# seven_seg.net
KiCad netlist of a schematic drawn in EAGLE
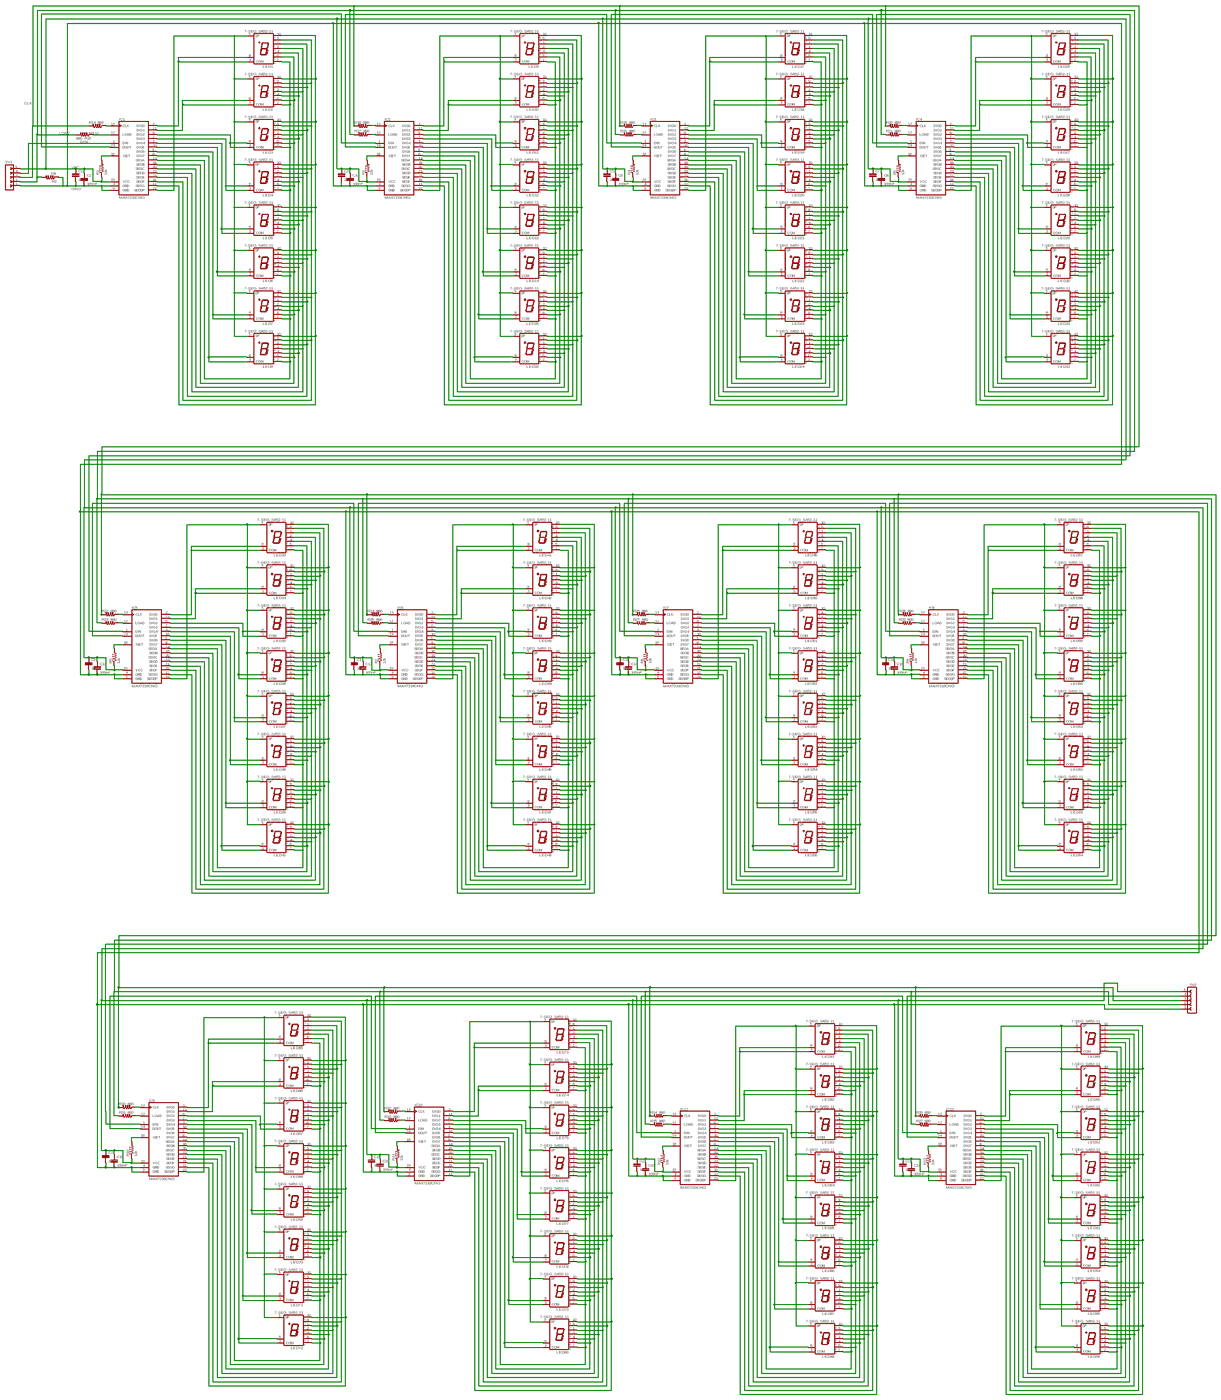
[diagram p0: schematic, sheet 1, overview]
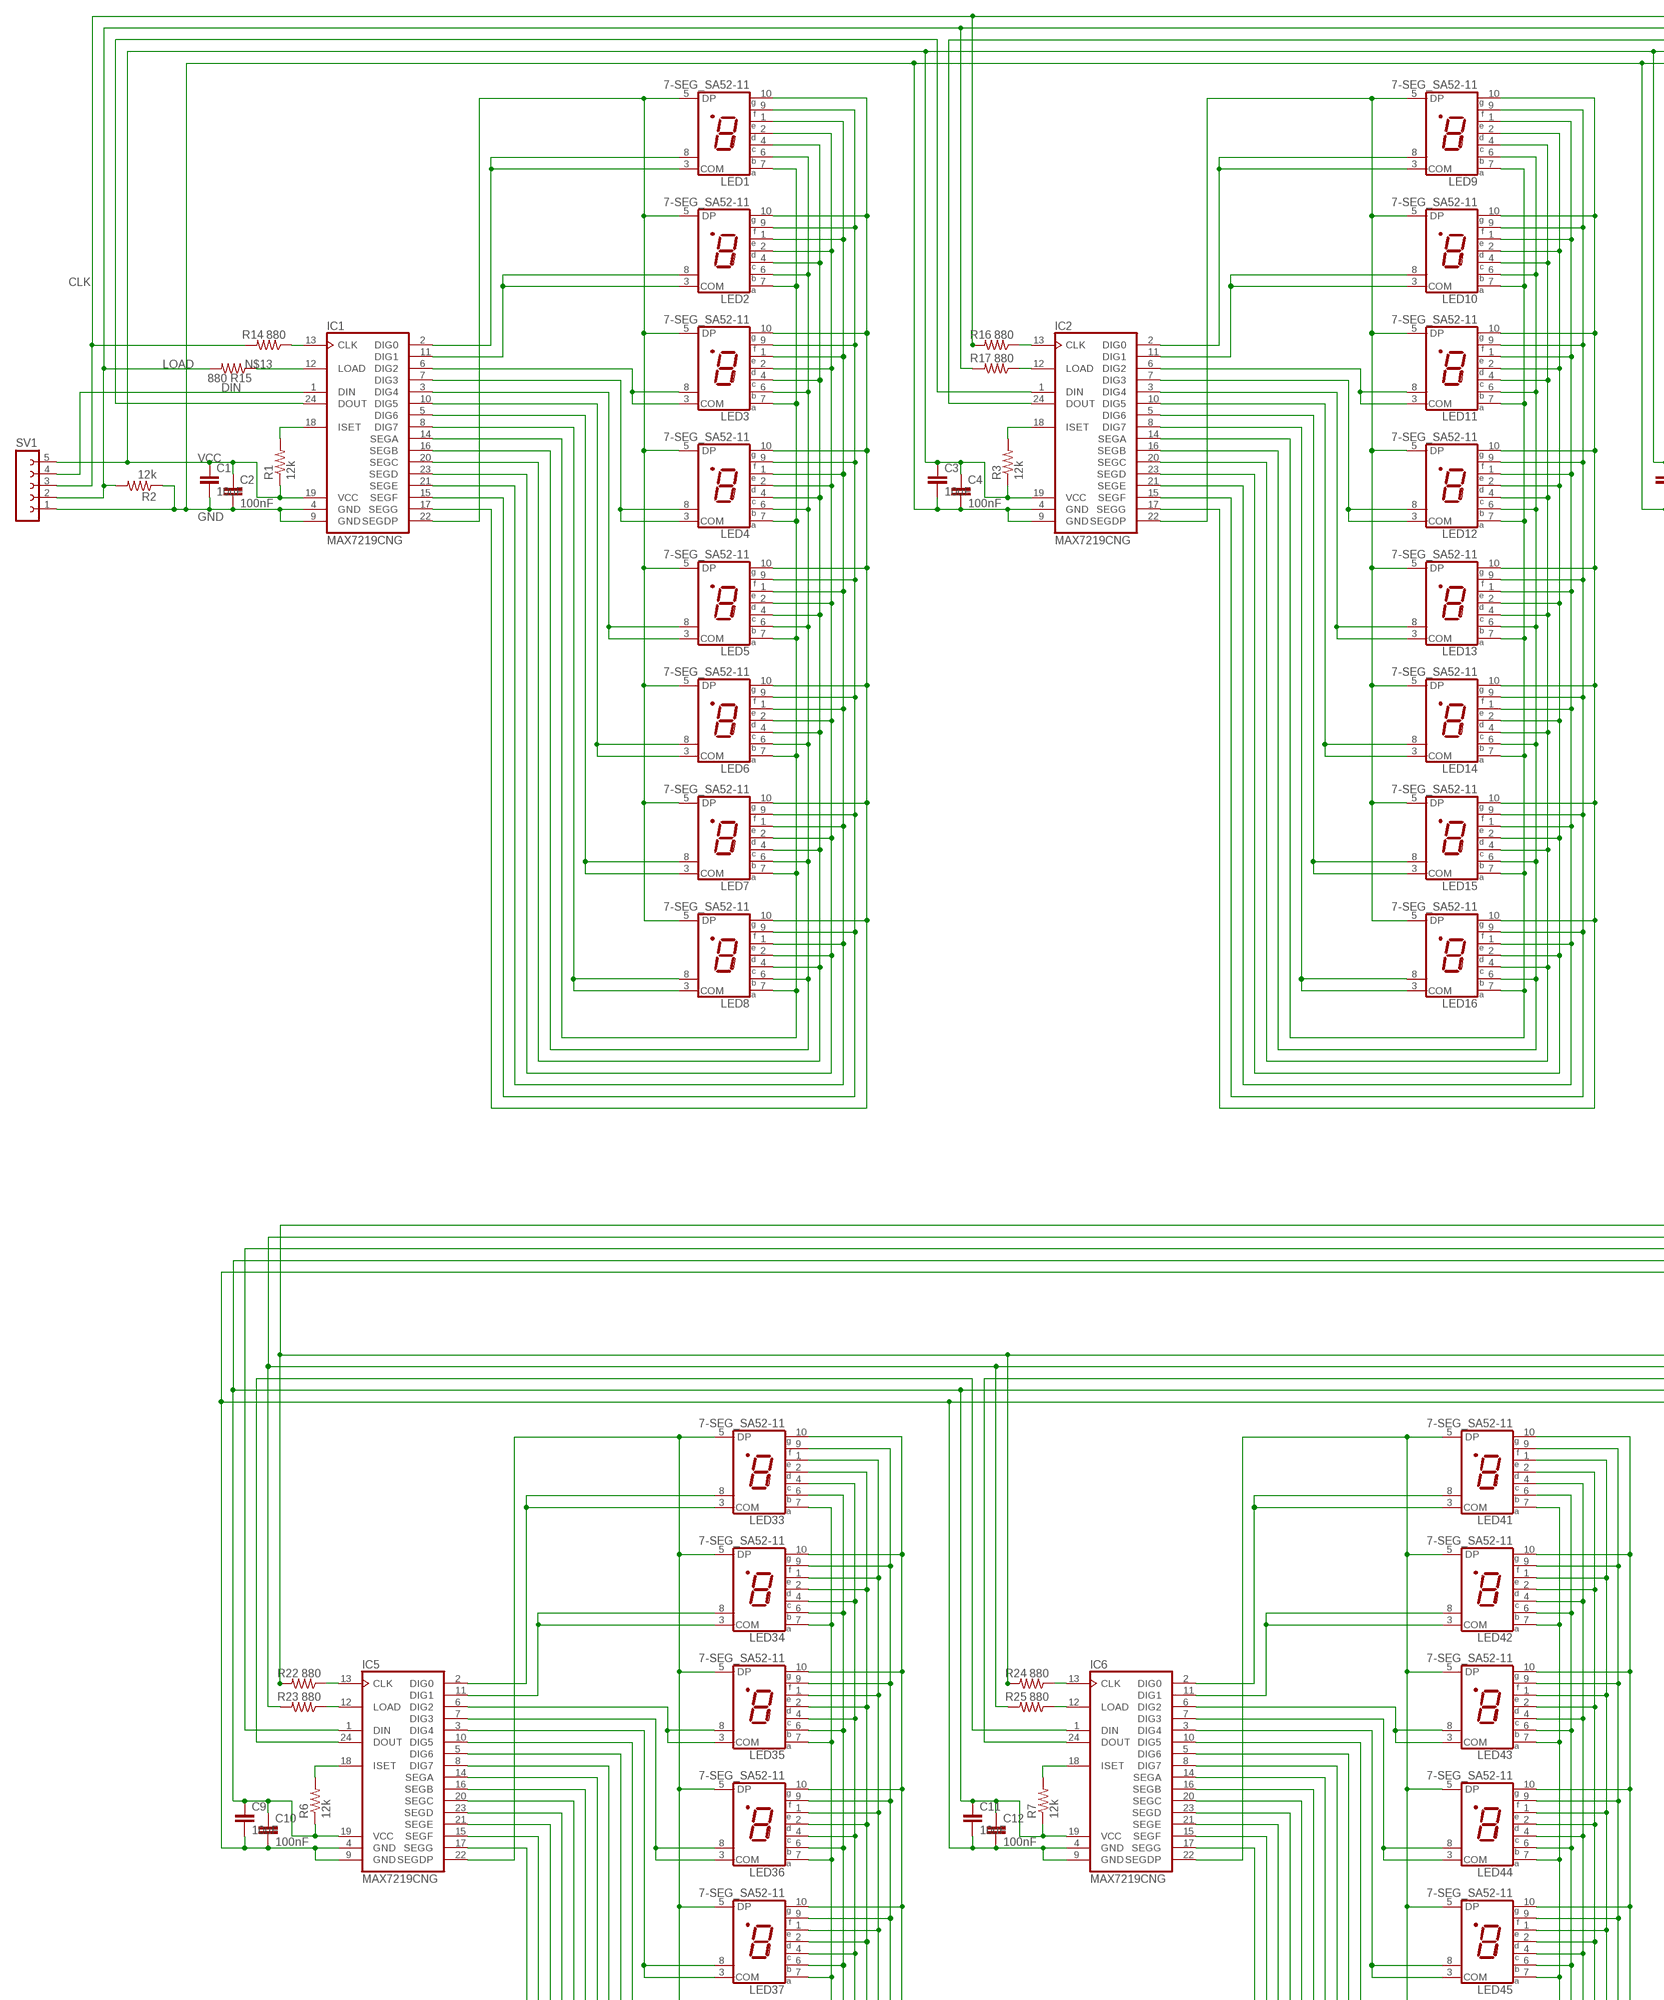
[diagram p1: schematic, sheet 1, part 1 of 4]
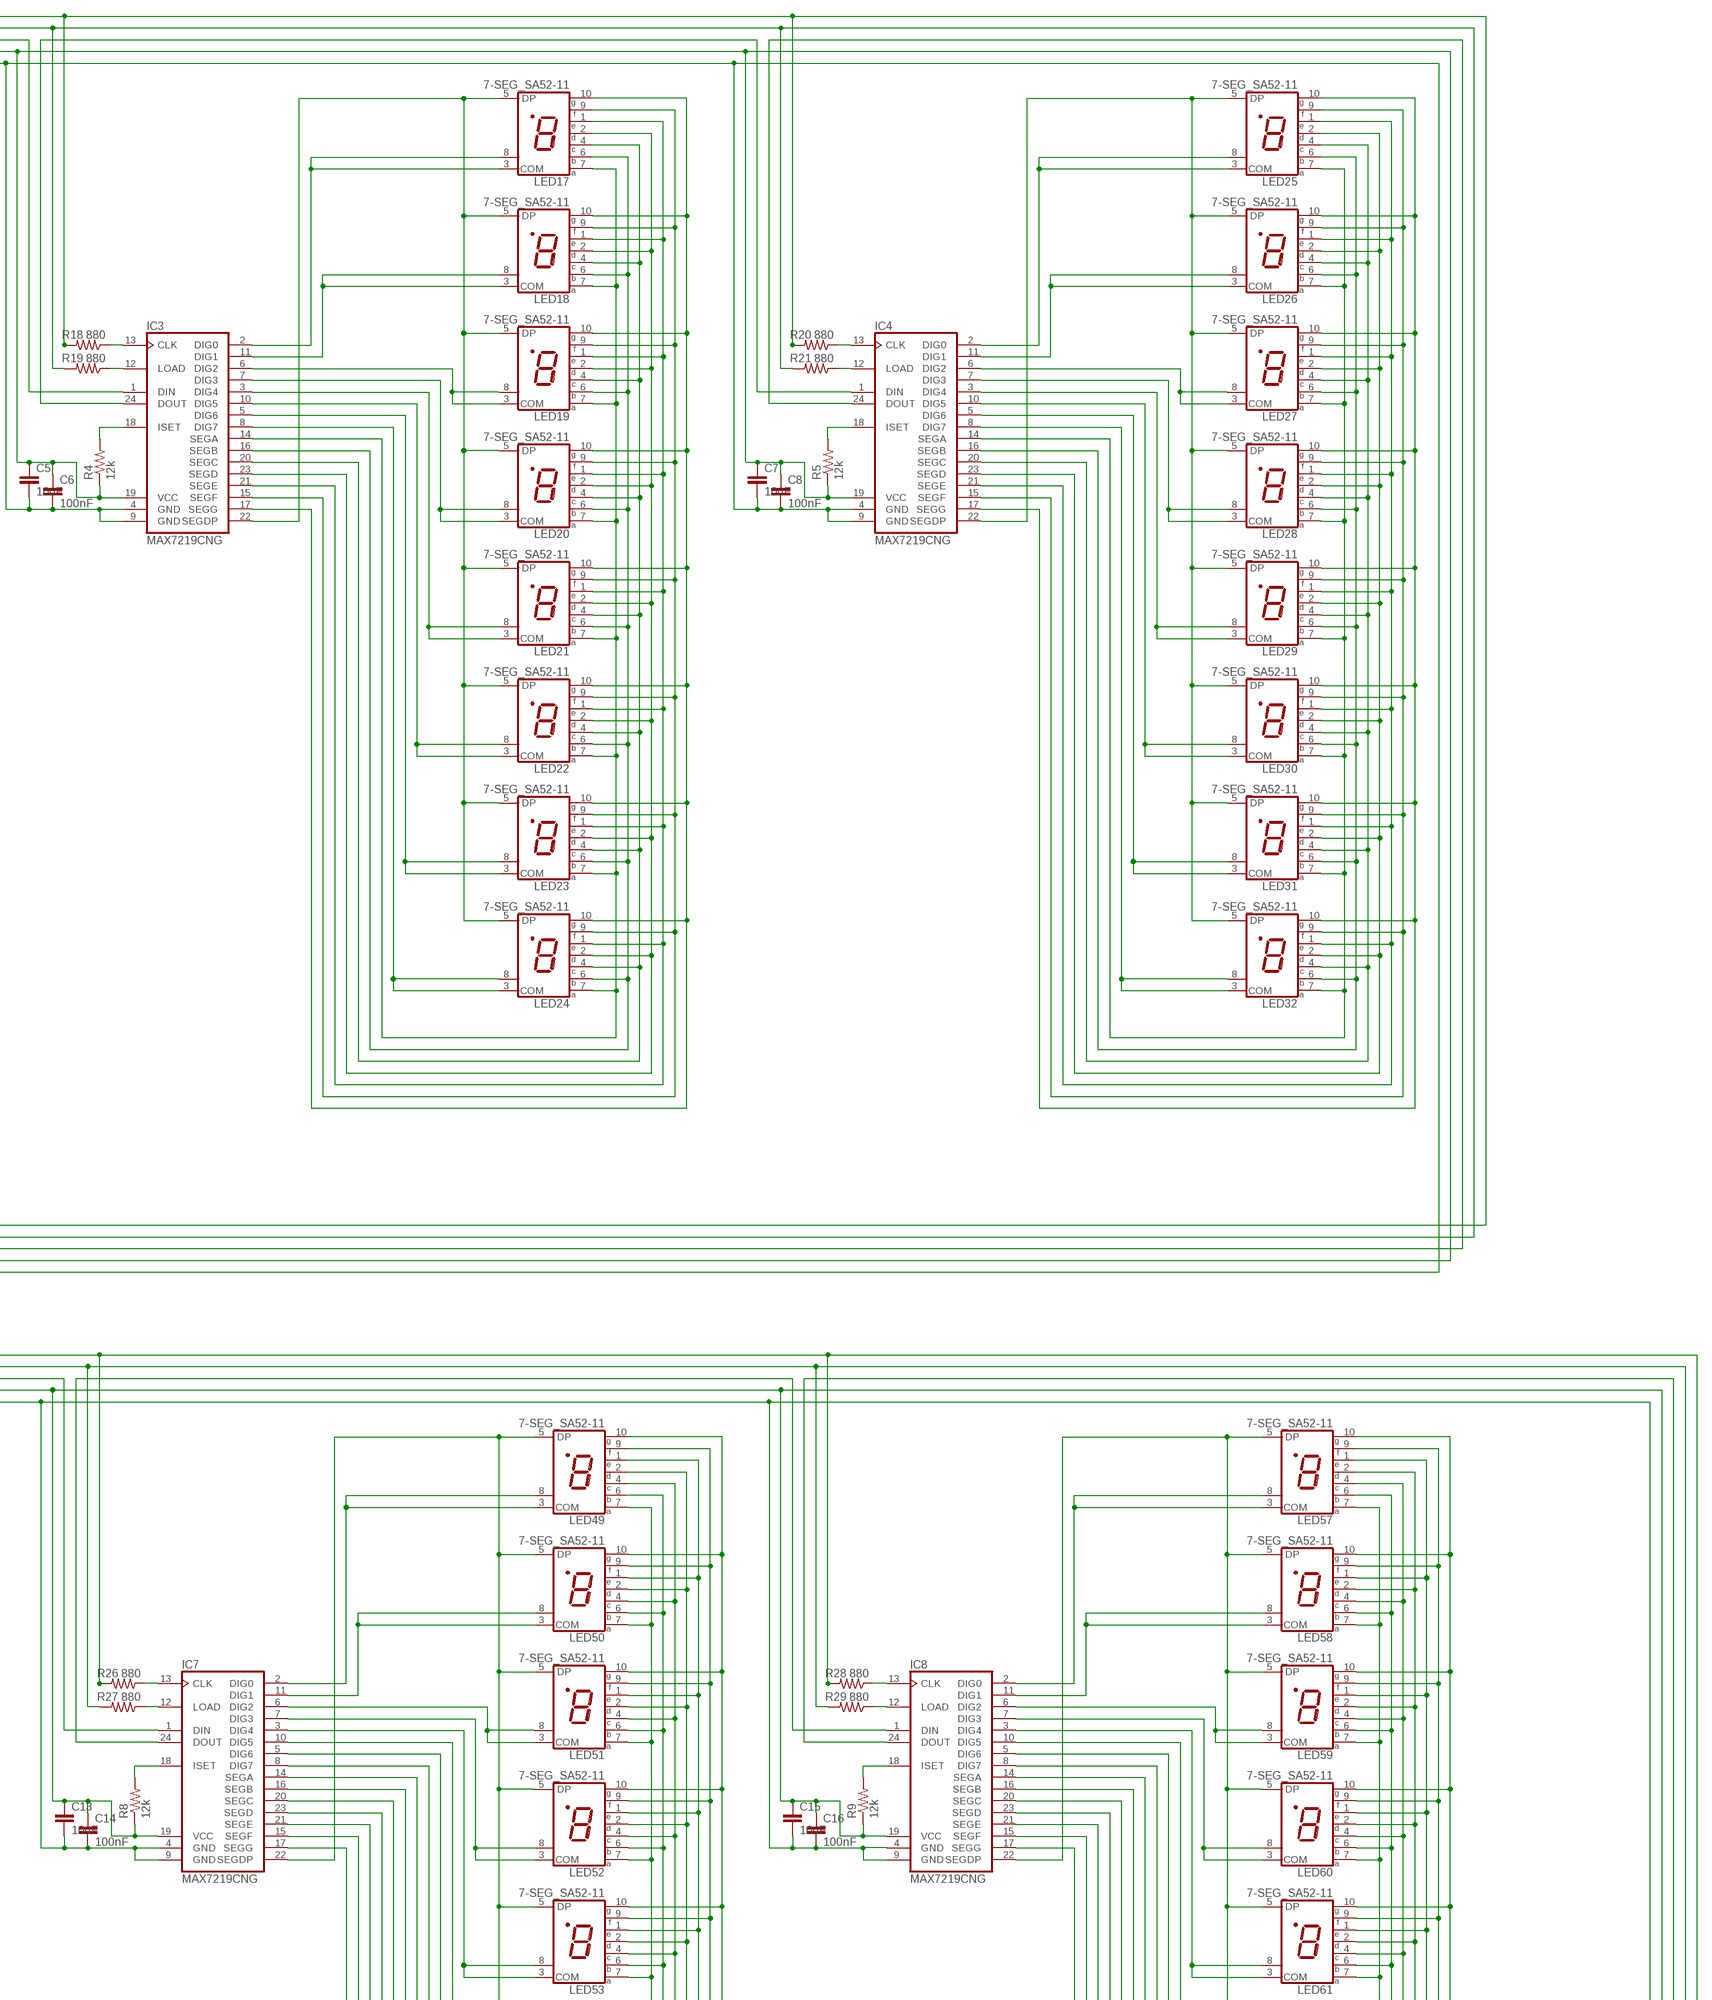
[diagram p2: schematic, sheet 1, part 2 of 4]
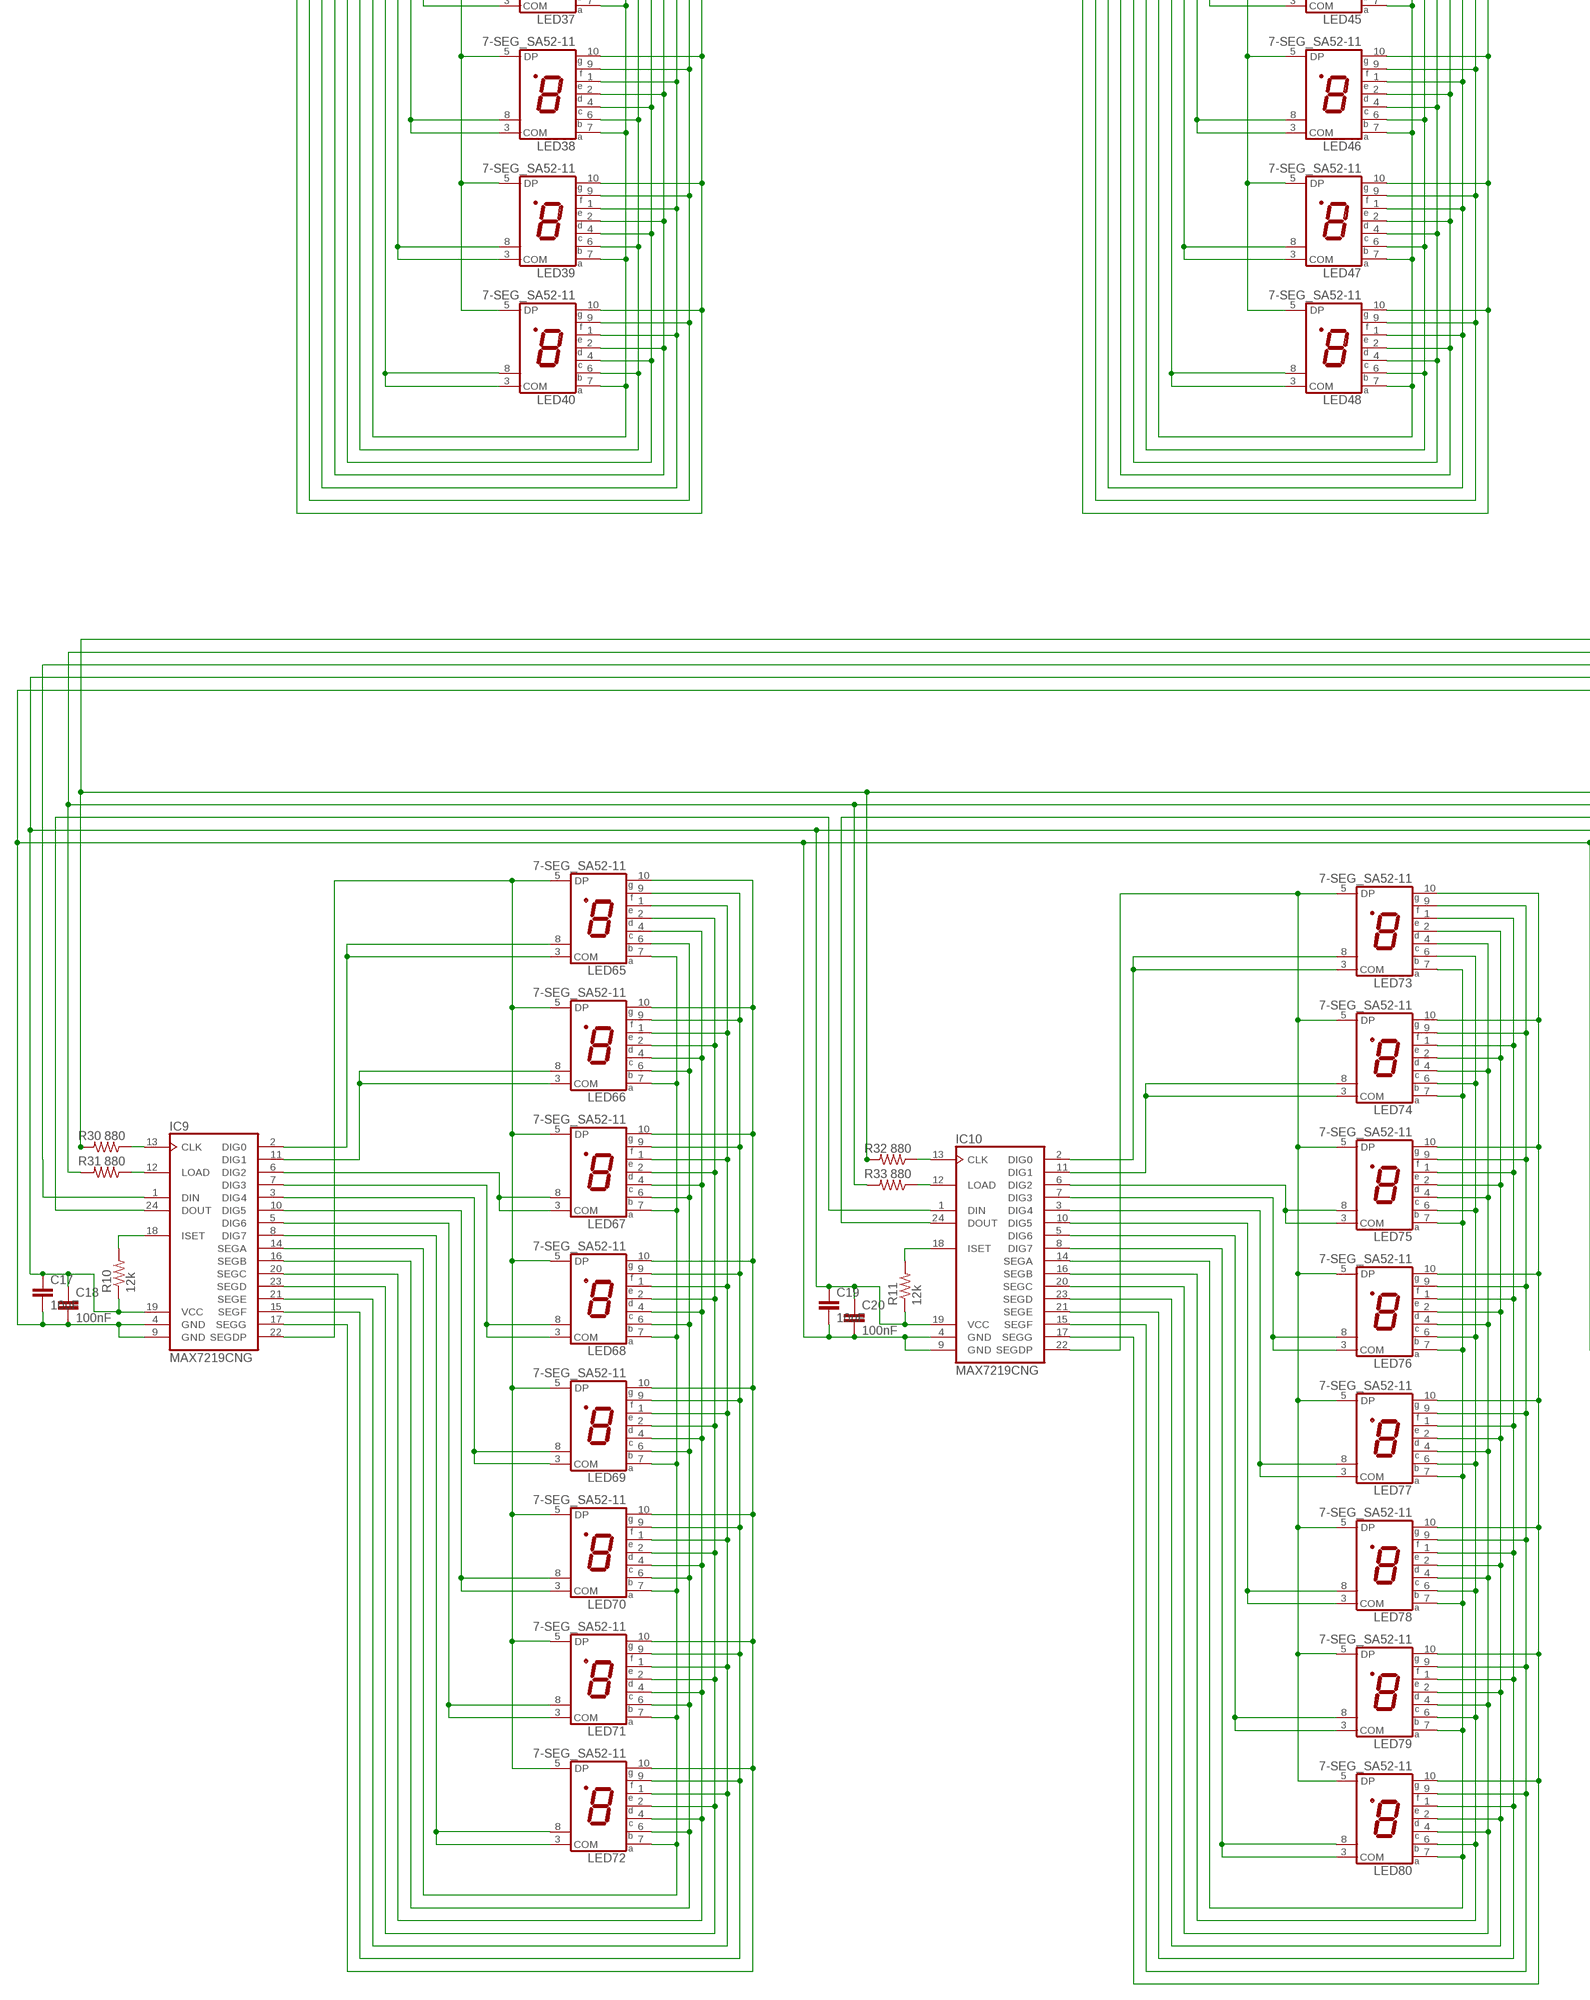
[diagram p3: schematic, sheet 1, part 3 of 4]
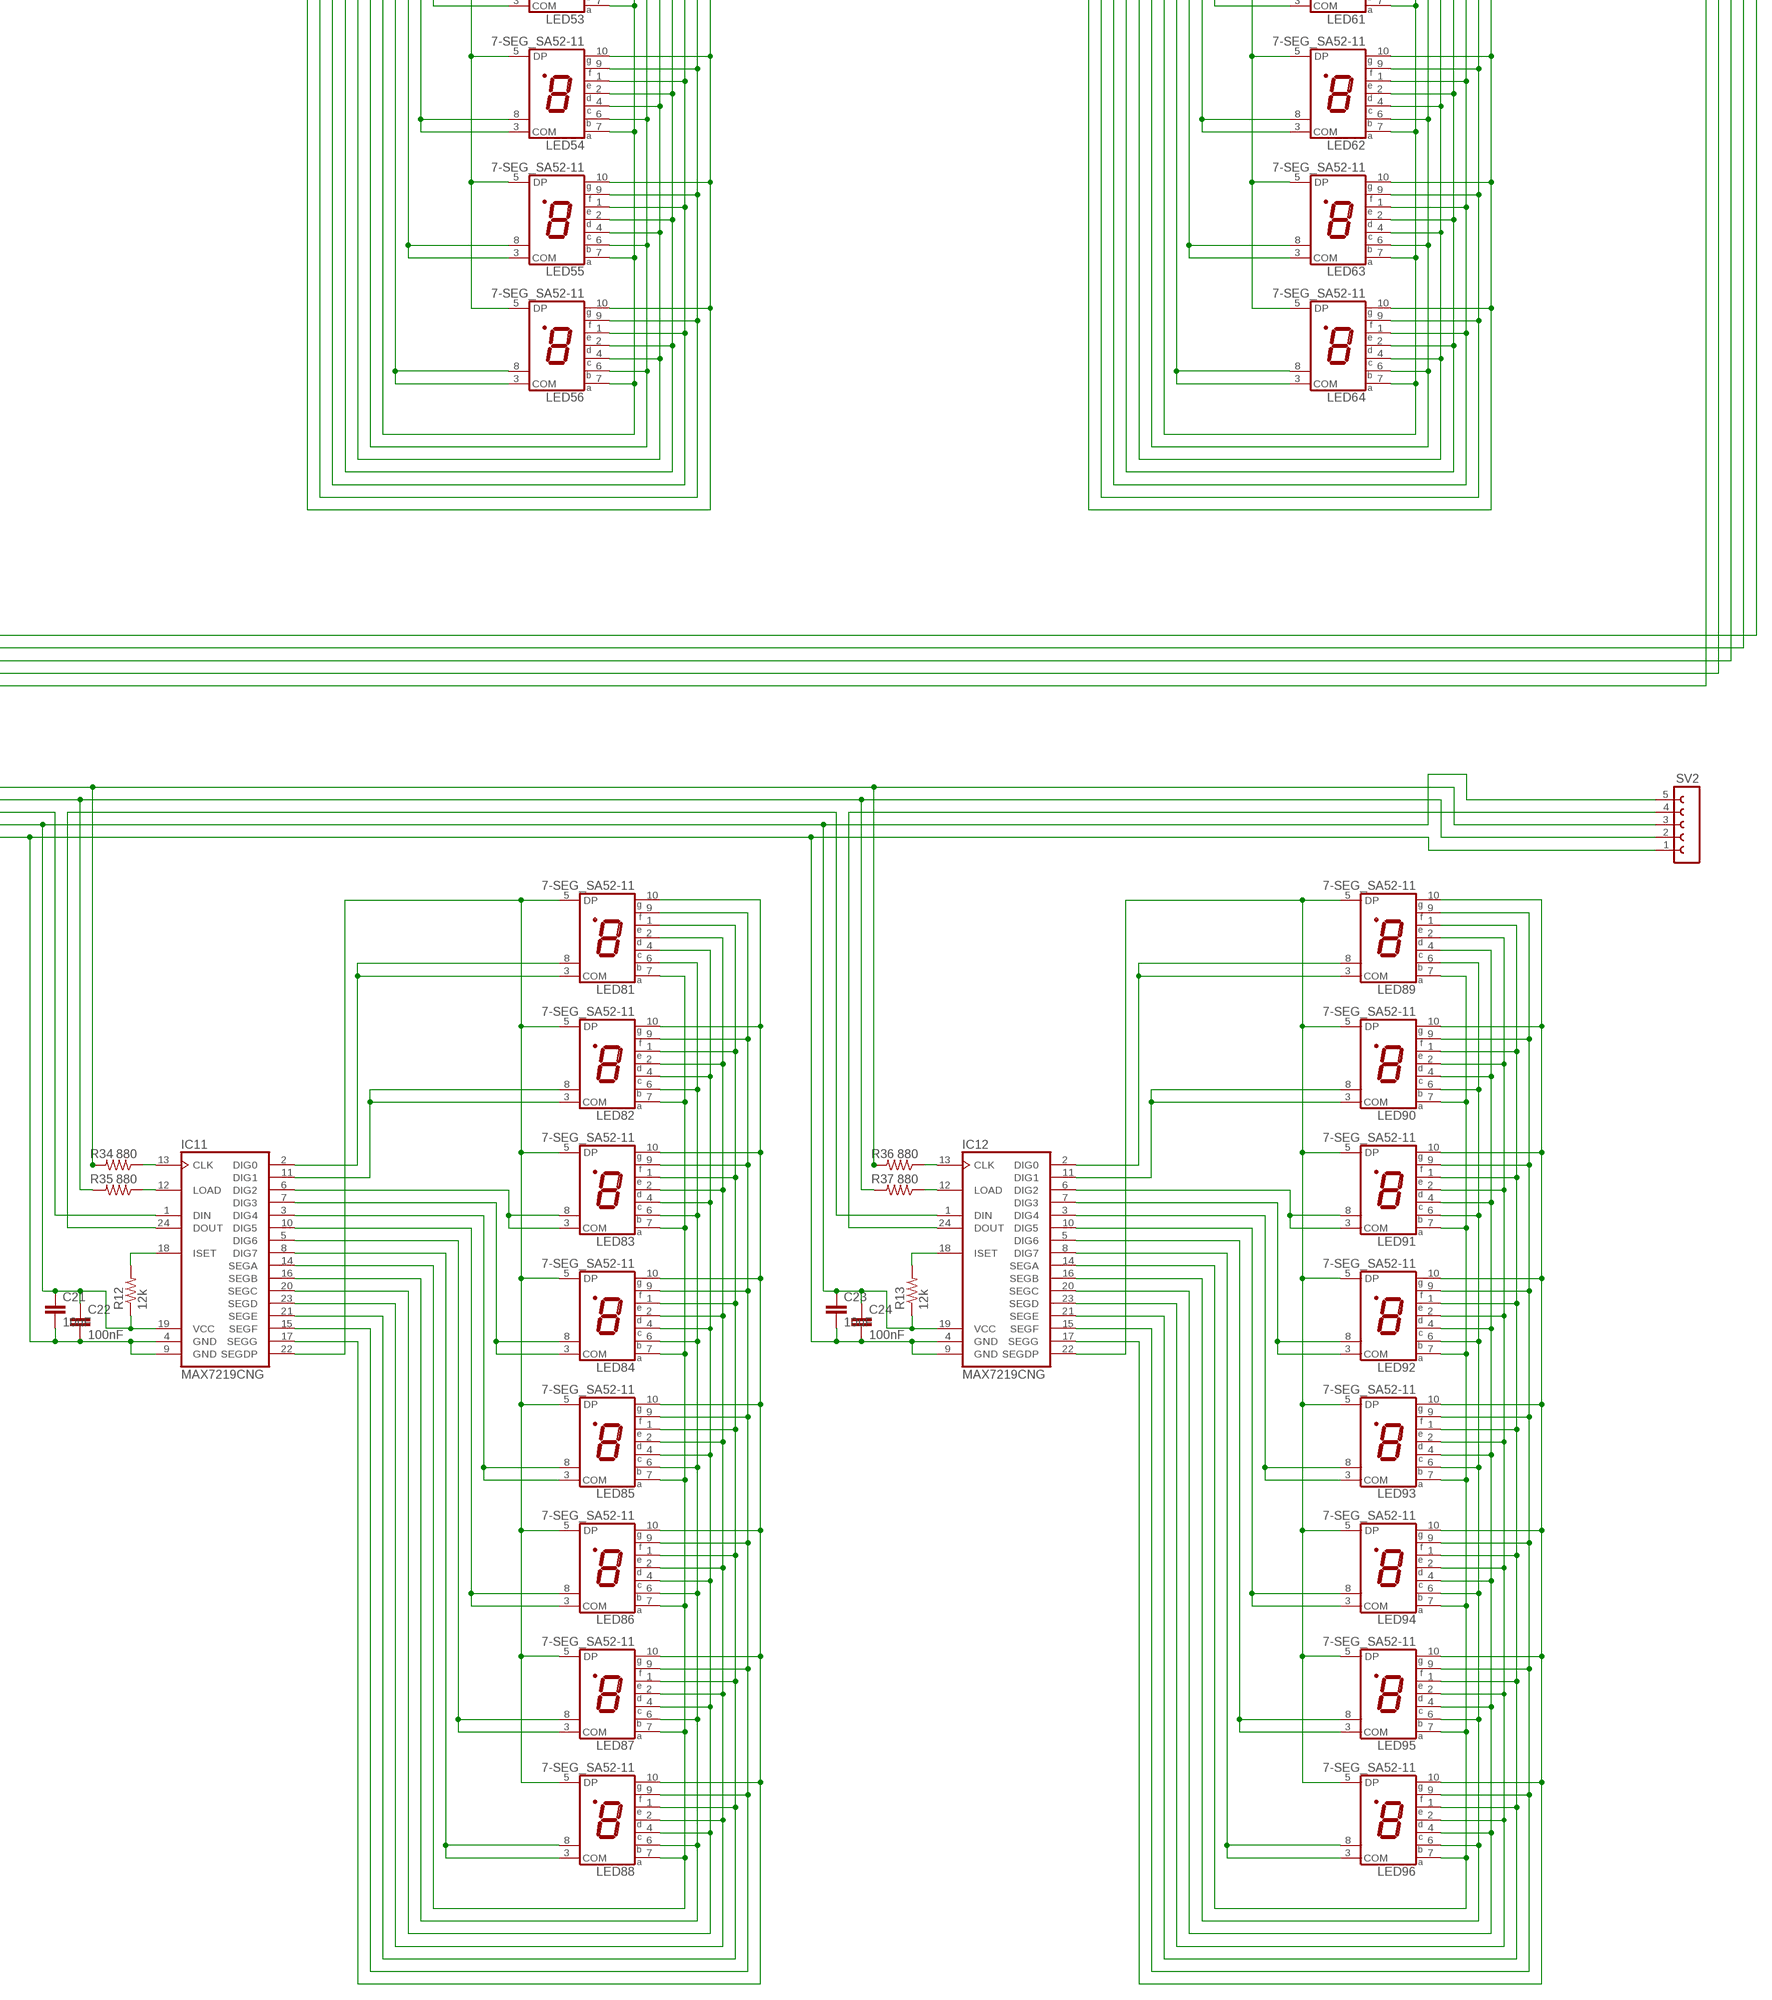
[diagram p4: schematic, sheet 1, part 4 of 4]

(export (version "E")
  (design (tool "Eeschema 10.0.6"))
  (components
    (comp (ref "C1")
      (value "10uF")
      (footprint "eagle-import:C2.5-2")
      (libsource (lib "eagle-import") (part "C2.5/2"))
    )
    (comp (ref "C2")
      (value "100nF")
      (footprint "eagle-import:C2.5-2")
      (libsource (lib "eagle-import") (part "C2.5/2"))
    )
    (comp (ref "C3")
      (value "10uF")
      (footprint "eagle-import:C2.5-2")
      (libsource (lib "eagle-import") (part "C2.5/2"))
    )
    (comp (ref "C4")
      (value "100nF")
      (footprint "eagle-import:C2.5-2")
      (libsource (lib "eagle-import") (part "C2.5/2"))
    )
    (comp (ref "C5")
      (value "10uF")
      (footprint "eagle-import:C2.5-2")
      (libsource (lib "eagle-import") (part "C2.5/2"))
    )
    (comp (ref "C6")
      (value "100nF")
      (footprint "eagle-import:C2.5-2")
      (libsource (lib "eagle-import") (part "C2.5/2"))
    )
    (comp (ref "C7")
      (value "10uF")
      (footprint "eagle-import:C2.5-2")
      (libsource (lib "eagle-import") (part "C2.5/2"))
    )
    (comp (ref "C8")
      (value "100nF")
      (footprint "eagle-import:C2.5-2")
      (libsource (lib "eagle-import") (part "C2.5/2"))
    )
    (comp (ref "C9")
      (value "10uF")
      (footprint "eagle-import:C2.5-2")
      (libsource (lib "eagle-import") (part "C2.5/2"))
    )
    (comp (ref "C10")
      (value "100nF")
      (footprint "eagle-import:C2.5-2")
      (libsource (lib "eagle-import") (part "C2.5/2"))
    )
    (comp (ref "C11")
      (value "10uF")
      (footprint "eagle-import:C2.5-2")
      (libsource (lib "eagle-import") (part "C2.5/2"))
    )
    (comp (ref "C12")
      (value "100nF")
      (footprint "eagle-import:C2.5-2")
      (libsource (lib "eagle-import") (part "C2.5/2"))
    )
    (comp (ref "C13")
      (value "10uF")
      (footprint "eagle-import:C2.5-2")
      (libsource (lib "eagle-import") (part "C2.5/2"))
    )
    (comp (ref "C14")
      (value "100nF")
      (footprint "eagle-import:C2.5-2")
      (libsource (lib "eagle-import") (part "C2.5/2"))
    )
    (comp (ref "C15")
      (value "10uF")
      (footprint "eagle-import:C2.5-2")
      (libsource (lib "eagle-import") (part "C2.5/2"))
    )
    (comp (ref "C16")
      (value "100nF")
      (footprint "eagle-import:C2.5-2")
      (libsource (lib "eagle-import") (part "C2.5/2"))
    )
    (comp (ref "C17")
      (value "10uF")
      (footprint "eagle-import:C2.5-2")
      (libsource (lib "eagle-import") (part "C2.5/2"))
    )
    (comp (ref "C18")
      (value "100nF")
      (footprint "eagle-import:C2.5-2")
      (libsource (lib "eagle-import") (part "C2.5/2"))
    )
    (comp (ref "C19")
      (value "10uF")
      (footprint "eagle-import:C2.5-2")
      (libsource (lib "eagle-import") (part "C2.5/2"))
    )
    (comp (ref "C20")
      (value "100nF")
      (footprint "eagle-import:C2.5-2")
      (libsource (lib "eagle-import") (part "C2.5/2"))
    )
    (comp (ref "C21")
      (value "10uF")
      (footprint "eagle-import:C2.5-2")
      (libsource (lib "eagle-import") (part "C2.5/2"))
    )
    (comp (ref "C22")
      (value "100nF")
      (footprint "eagle-import:C2.5-2")
      (libsource (lib "eagle-import") (part "C2.5/2"))
    )
    (comp (ref "C23")
      (value "10uF")
      (footprint "eagle-import:C2.5-2")
      (libsource (lib "eagle-import") (part "C2.5/2"))
    )
    (comp (ref "C24")
      (value "100nF")
      (footprint "eagle-import:C2.5-2")
      (libsource (lib "eagle-import") (part "C2.5/2"))
    )
    (comp (ref "IC1")
      (value "MAX7219CNG")
      (footprint "eagle-import:DIL24-3")
      (fields (field (name "MF") "MAXIM"))
      (libsource (lib "eagle-import") (part "MAX7219CNG"))
    )
    (comp (ref "IC2")
      (value "MAX7219CNG")
      (footprint "eagle-import:DIL24-3")
      (fields (field (name "MF") "MAXIM"))
      (libsource (lib "eagle-import") (part "MAX7219CNG"))
    )
    (comp (ref "IC3")
      (value "MAX7219CNG")
      (footprint "eagle-import:DIL24-3")
      (fields (field (name "MF") "MAXIM"))
      (libsource (lib "eagle-import") (part "MAX7219CNG"))
    )
    (comp (ref "IC4")
      (value "MAX7219CNG")
      (footprint "eagle-import:DIL24-3")
      (fields (field (name "MF") "MAXIM"))
      (libsource (lib "eagle-import") (part "MAX7219CNG"))
    )
    (comp (ref "IC5")
      (value "MAX7219CNG")
      (footprint "eagle-import:DIL24-3")
      (fields (field (name "MF") "MAXIM"))
      (libsource (lib "eagle-import") (part "MAX7219CNG"))
    )
    (comp (ref "IC6")
      (value "MAX7219CNG")
      (footprint "eagle-import:DIL24-3")
      (fields (field (name "MF") "MAXIM"))
      (libsource (lib "eagle-import") (part "MAX7219CNG"))
    )
    (comp (ref "IC7")
      (value "MAX7219CNG")
      (footprint "eagle-import:DIL24-3")
      (fields (field (name "MF") "MAXIM"))
      (libsource (lib "eagle-import") (part "MAX7219CNG"))
    )
    (comp (ref "IC8")
      (value "MAX7219CNG")
      (footprint "eagle-import:DIL24-3")
      (fields (field (name "MF") "MAXIM"))
      (libsource (lib "eagle-import") (part "MAX7219CNG"))
    )
    (comp (ref "IC9")
      (value "MAX7219CNG")
      (footprint "eagle-import:DIL24-3")
      (fields (field (name "MF") "MAXIM"))
      (libsource (lib "eagle-import") (part "MAX7219CNG"))
    )
    (comp (ref "IC10")
      (value "MAX7219CNG")
      (footprint "eagle-import:DIL24-3")
      (fields (field (name "MF") "MAXIM"))
      (libsource (lib "eagle-import") (part "MAX7219CNG"))
    )
    (comp (ref "IC11")
      (value "MAX7219CNG")
      (footprint "eagle-import:DIL24-3")
      (fields (field (name "MF") "MAXIM"))
      (libsource (lib "eagle-import") (part "MAX7219CNG"))
    )
    (comp (ref "IC12")
      (value "MAX7219CNG")
      (footprint "eagle-import:DIL24-3")
      (fields (field (name "MF") "MAXIM"))
      (libsource (lib "eagle-import") (part "MAX7219CNG"))
    )
    (comp (ref "LED1")
      (value "7-SEG_SA52-11")
      (footprint "eagle-import:SA52-11")
      (libsource (lib "eagle-import") (part "7-SEG_SA52-11"))
    )
    (comp (ref "LED2")
      (value "7-SEG_SA52-11")
      (footprint "eagle-import:SA52-11")
      (libsource (lib "eagle-import") (part "7-SEG_SA52-11"))
    )
    (comp (ref "LED3")
      (value "7-SEG_SA52-11")
      (footprint "eagle-import:SA52-11")
      (libsource (lib "eagle-import") (part "7-SEG_SA52-11"))
    )
    (comp (ref "LED4")
      (value "7-SEG_SA52-11")
      (footprint "eagle-import:SA52-11")
      (libsource (lib "eagle-import") (part "7-SEG_SA52-11"))
    )
    (comp (ref "LED5")
      (value "7-SEG_SA52-11")
      (footprint "eagle-import:SA52-11")
      (libsource (lib "eagle-import") (part "7-SEG_SA52-11"))
    )
    (comp (ref "LED6")
      (value "7-SEG_SA52-11")
      (footprint "eagle-import:SA52-11")
      (libsource (lib "eagle-import") (part "7-SEG_SA52-11"))
    )
    (comp (ref "LED7")
      (value "7-SEG_SA52-11")
      (footprint "eagle-import:SA52-11")
      (libsource (lib "eagle-import") (part "7-SEG_SA52-11"))
    )
    (comp (ref "LED8")
      (value "7-SEG_SA52-11")
      (footprint "eagle-import:SA52-11")
      (libsource (lib "eagle-import") (part "7-SEG_SA52-11"))
    )
    (comp (ref "LED9")
      (value "7-SEG_SA52-11")
      (footprint "eagle-import:SA52-11")
      (libsource (lib "eagle-import") (part "7-SEG_SA52-11"))
    )
    (comp (ref "LED10")
      (value "7-SEG_SA52-11")
      (footprint "eagle-import:SA52-11")
      (libsource (lib "eagle-import") (part "7-SEG_SA52-11"))
    )
    (comp (ref "LED11")
      (value "7-SEG_SA52-11")
      (footprint "eagle-import:SA52-11")
      (libsource (lib "eagle-import") (part "7-SEG_SA52-11"))
    )
    (comp (ref "LED12")
      (value "7-SEG_SA52-11")
      (footprint "eagle-import:SA52-11")
      (libsource (lib "eagle-import") (part "7-SEG_SA52-11"))
    )
    (comp (ref "LED13")
      (value "7-SEG_SA52-11")
      (footprint "eagle-import:SA52-11")
      (libsource (lib "eagle-import") (part "7-SEG_SA52-11"))
    )
    (comp (ref "LED14")
      (value "7-SEG_SA52-11")
      (footprint "eagle-import:SA52-11")
      (libsource (lib "eagle-import") (part "7-SEG_SA52-11"))
    )
    (comp (ref "LED15")
      (value "7-SEG_SA52-11")
      (footprint "eagle-import:SA52-11")
      (libsource (lib "eagle-import") (part "7-SEG_SA52-11"))
    )
    (comp (ref "LED16")
      (value "7-SEG_SA52-11")
      (footprint "eagle-import:SA52-11")
      (libsource (lib "eagle-import") (part "7-SEG_SA52-11"))
    )
    (comp (ref "LED17")
      (value "7-SEG_SA52-11")
      (footprint "eagle-import:SA52-11")
      (libsource (lib "eagle-import") (part "7-SEG_SA52-11"))
    )
    (comp (ref "LED18")
      (value "7-SEG_SA52-11")
      (footprint "eagle-import:SA52-11")
      (libsource (lib "eagle-import") (part "7-SEG_SA52-11"))
    )
    (comp (ref "LED19")
      (value "7-SEG_SA52-11")
      (footprint "eagle-import:SA52-11")
      (libsource (lib "eagle-import") (part "7-SEG_SA52-11"))
    )
    (comp (ref "LED20")
      (value "7-SEG_SA52-11")
      (footprint "eagle-import:SA52-11")
      (libsource (lib "eagle-import") (part "7-SEG_SA52-11"))
    )
    (comp (ref "LED21")
      (value "7-SEG_SA52-11")
      (footprint "eagle-import:SA52-11")
      (libsource (lib "eagle-import") (part "7-SEG_SA52-11"))
    )
    (comp (ref "LED22")
      (value "7-SEG_SA52-11")
      (footprint "eagle-import:SA52-11")
      (libsource (lib "eagle-import") (part "7-SEG_SA52-11"))
    )
    (comp (ref "LED23")
      (value "7-SEG_SA52-11")
      (footprint "eagle-import:SA52-11")
      (libsource (lib "eagle-import") (part "7-SEG_SA52-11"))
    )
    (comp (ref "LED24")
      (value "7-SEG_SA52-11")
      (footprint "eagle-import:SA52-11")
      (libsource (lib "eagle-import") (part "7-SEG_SA52-11"))
    )
    (comp (ref "LED25")
      (value "7-SEG_SA52-11")
      (footprint "eagle-import:SA52-11")
      (libsource (lib "eagle-import") (part "7-SEG_SA52-11"))
    )
    (comp (ref "LED26")
      (value "7-SEG_SA52-11")
      (footprint "eagle-import:SA52-11")
      (libsource (lib "eagle-import") (part "7-SEG_SA52-11"))
    )
    (comp (ref "LED27")
      (value "7-SEG_SA52-11")
      (footprint "eagle-import:SA52-11")
      (libsource (lib "eagle-import") (part "7-SEG_SA52-11"))
    )
    (comp (ref "LED28")
      (value "7-SEG_SA52-11")
      (footprint "eagle-import:SA52-11")
      (libsource (lib "eagle-import") (part "7-SEG_SA52-11"))
    )
    (comp (ref "LED29")
      (value "7-SEG_SA52-11")
      (footprint "eagle-import:SA52-11")
      (libsource (lib "eagle-import") (part "7-SEG_SA52-11"))
    )
    (comp (ref "LED30")
      (value "7-SEG_SA52-11")
      (footprint "eagle-import:SA52-11")
      (libsource (lib "eagle-import") (part "7-SEG_SA52-11"))
    )
    (comp (ref "LED31")
      (value "7-SEG_SA52-11")
      (footprint "eagle-import:SA52-11")
      (libsource (lib "eagle-import") (part "7-SEG_SA52-11"))
    )
    (comp (ref "LED32")
      (value "7-SEG_SA52-11")
      (footprint "eagle-import:SA52-11")
      (libsource (lib "eagle-import") (part "7-SEG_SA52-11"))
    )
    (comp (ref "LED33")
      (value "7-SEG_SA52-11")
      (footprint "eagle-import:SA52-11")
      (libsource (lib "eagle-import") (part "7-SEG_SA52-11"))
    )
    (comp (ref "LED34")
      (value "7-SEG_SA52-11")
      (footprint "eagle-import:SA52-11")
      (libsource (lib "eagle-import") (part "7-SEG_SA52-11"))
    )
    (comp (ref "LED35")
      (value "7-SEG_SA52-11")
      (footprint "eagle-import:SA52-11")
      (libsource (lib "eagle-import") (part "7-SEG_SA52-11"))
    )
    (comp (ref "LED36")
      (value "7-SEG_SA52-11")
      (footprint "eagle-import:SA52-11")
      (libsource (lib "eagle-import") (part "7-SEG_SA52-11"))
    )
    (comp (ref "LED37")
      (value "7-SEG_SA52-11")
      (footprint "eagle-import:SA52-11")
      (libsource (lib "eagle-import") (part "7-SEG_SA52-11"))
    )
    (comp (ref "LED38")
      (value "7-SEG_SA52-11")
      (footprint "eagle-import:SA52-11")
      (libsource (lib "eagle-import") (part "7-SEG_SA52-11"))
    )
    (comp (ref "LED39")
      (value "7-SEG_SA52-11")
      (footprint "eagle-import:SA52-11")
      (libsource (lib "eagle-import") (part "7-SEG_SA52-11"))
    )
    (comp (ref "LED40")
      (value "7-SEG_SA52-11")
      (footprint "eagle-import:SA52-11")
      (libsource (lib "eagle-import") (part "7-SEG_SA52-11"))
    )
    (comp (ref "LED41")
      (value "7-SEG_SA52-11")
      (footprint "eagle-import:SA52-11")
      (libsource (lib "eagle-import") (part "7-SEG_SA52-11"))
    )
    (comp (ref "LED42")
      (value "7-SEG_SA52-11")
      (footprint "eagle-import:SA52-11")
      (libsource (lib "eagle-import") (part "7-SEG_SA52-11"))
    )
    (comp (ref "LED43")
      (value "7-SEG_SA52-11")
      (footprint "eagle-import:SA52-11")
      (libsource (lib "eagle-import") (part "7-SEG_SA52-11"))
    )
    (comp (ref "LED44")
      (value "7-SEG_SA52-11")
      (footprint "eagle-import:SA52-11")
      (libsource (lib "eagle-import") (part "7-SEG_SA52-11"))
    )
    (comp (ref "LED45")
      (value "7-SEG_SA52-11")
      (footprint "eagle-import:SA52-11")
      (libsource (lib "eagle-import") (part "7-SEG_SA52-11"))
    )
    (comp (ref "LED46")
      (value "7-SEG_SA52-11")
      (footprint "eagle-import:SA52-11")
      (libsource (lib "eagle-import") (part "7-SEG_SA52-11"))
    )
    (comp (ref "LED47")
      (value "7-SEG_SA52-11")
      (footprint "eagle-import:SA52-11")
      (libsource (lib "eagle-import") (part "7-SEG_SA52-11"))
    )
    (comp (ref "LED48")
      (value "7-SEG_SA52-11")
      (footprint "eagle-import:SA52-11")
      (libsource (lib "eagle-import") (part "7-SEG_SA52-11"))
    )
    (comp (ref "LED49")
      (value "7-SEG_SA52-11")
      (footprint "eagle-import:SA52-11")
      (libsource (lib "eagle-import") (part "7-SEG_SA52-11"))
    )
    (comp (ref "LED50")
      (value "7-SEG_SA52-11")
      (footprint "eagle-import:SA52-11")
      (libsource (lib "eagle-import") (part "7-SEG_SA52-11"))
    )
    (comp (ref "LED51")
      (value "7-SEG_SA52-11")
      (footprint "eagle-import:SA52-11")
      (libsource (lib "eagle-import") (part "7-SEG_SA52-11"))
    )
    (comp (ref "LED52")
      (value "7-SEG_SA52-11")
      (footprint "eagle-import:SA52-11")
      (libsource (lib "eagle-import") (part "7-SEG_SA52-11"))
    )
    (comp (ref "LED53")
      (value "7-SEG_SA52-11")
      (footprint "eagle-import:SA52-11")
      (libsource (lib "eagle-import") (part "7-SEG_SA52-11"))
    )
    (comp (ref "LED54")
      (value "7-SEG_SA52-11")
      (footprint "eagle-import:SA52-11")
      (libsource (lib "eagle-import") (part "7-SEG_SA52-11"))
    )
    (comp (ref "LED55")
      (value "7-SEG_SA52-11")
      (footprint "eagle-import:SA52-11")
      (libsource (lib "eagle-import") (part "7-SEG_SA52-11"))
    )
    (comp (ref "LED56")
      (value "7-SEG_SA52-11")
      (footprint "eagle-import:SA52-11")
      (libsource (lib "eagle-import") (part "7-SEG_SA52-11"))
    )
    (comp (ref "LED57")
      (value "7-SEG_SA52-11")
      (footprint "eagle-import:SA52-11")
      (libsource (lib "eagle-import") (part "7-SEG_SA52-11"))
    )
    (comp (ref "LED58")
      (value "7-SEG_SA52-11")
      (footprint "eagle-import:SA52-11")
      (libsource (lib "eagle-import") (part "7-SEG_SA52-11"))
    )
    (comp (ref "LED59")
      (value "7-SEG_SA52-11")
      (footprint "eagle-import:SA52-11")
      (libsource (lib "eagle-import") (part "7-SEG_SA52-11"))
    )
    (comp (ref "LED60")
      (value "7-SEG_SA52-11")
      (footprint "eagle-import:SA52-11")
      (libsource (lib "eagle-import") (part "7-SEG_SA52-11"))
    )
    (comp (ref "LED61")
      (value "7-SEG_SA52-11")
      (footprint "eagle-import:SA52-11")
      (libsource (lib "eagle-import") (part "7-SEG_SA52-11"))
    )
    (comp (ref "LED62")
      (value "7-SEG_SA52-11")
      (footprint "eagle-import:SA52-11")
      (libsource (lib "eagle-import") (part "7-SEG_SA52-11"))
    )
    (comp (ref "LED63")
      (value "7-SEG_SA52-11")
      (footprint "eagle-import:SA52-11")
      (libsource (lib "eagle-import") (part "7-SEG_SA52-11"))
    )
    (comp (ref "LED64")
      (value "7-SEG_SA52-11")
      (footprint "eagle-import:SA52-11")
      (libsource (lib "eagle-import") (part "7-SEG_SA52-11"))
    )
    (comp (ref "LED65")
      (value "7-SEG_SA52-11")
      (footprint "eagle-import:SA52-11")
      (libsource (lib "eagle-import") (part "7-SEG_SA52-11"))
    )
    (comp (ref "LED66")
      (value "7-SEG_SA52-11")
      (footprint "eagle-import:SA52-11")
      (libsource (lib "eagle-import") (part "7-SEG_SA52-11"))
    )
    (comp (ref "LED67")
      (value "7-SEG_SA52-11")
      (footprint "eagle-import:SA52-11")
      (libsource (lib "eagle-import") (part "7-SEG_SA52-11"))
    )
    (comp (ref "LED68")
      (value "7-SEG_SA52-11")
      (footprint "eagle-import:SA52-11")
      (libsource (lib "eagle-import") (part "7-SEG_SA52-11"))
    )
    (comp (ref "LED69")
      (value "7-SEG_SA52-11")
      (footprint "eagle-import:SA52-11")
      (libsource (lib "eagle-import") (part "7-SEG_SA52-11"))
    )
    (comp (ref "LED70")
      (value "7-SEG_SA52-11")
      (footprint "eagle-import:SA52-11")
      (libsource (lib "eagle-import") (part "7-SEG_SA52-11"))
    )
    (comp (ref "LED71")
      (value "7-SEG_SA52-11")
      (footprint "eagle-import:SA52-11")
      (libsource (lib "eagle-import") (part "7-SEG_SA52-11"))
    )
    (comp (ref "LED72")
      (value "7-SEG_SA52-11")
      (footprint "eagle-import:SA52-11")
      (libsource (lib "eagle-import") (part "7-SEG_SA52-11"))
    )
    (comp (ref "LED73")
      (value "7-SEG_SA52-11")
      (footprint "eagle-import:SA52-11")
      (libsource (lib "eagle-import") (part "7-SEG_SA52-11"))
    )
    (comp (ref "LED74")
      (value "7-SEG_SA52-11")
      (footprint "eagle-import:SA52-11")
      (libsource (lib "eagle-import") (part "7-SEG_SA52-11"))
    )
    (comp (ref "LED75")
      (value "7-SEG_SA52-11")
      (footprint "eagle-import:SA52-11")
      (libsource (lib "eagle-import") (part "7-SEG_SA52-11"))
    )
    (comp (ref "LED76")
      (value "7-SEG_SA52-11")
      (footprint "eagle-import:SA52-11")
      (libsource (lib "eagle-import") (part "7-SEG_SA52-11"))
    )
    (comp (ref "LED77")
      (value "7-SEG_SA52-11")
      (footprint "eagle-import:SA52-11")
      (libsource (lib "eagle-import") (part "7-SEG_SA52-11"))
    )
    (comp (ref "LED78")
      (value "7-SEG_SA52-11")
      (footprint "eagle-import:SA52-11")
      (libsource (lib "eagle-import") (part "7-SEG_SA52-11"))
    )
    (comp (ref "LED79")
      (value "7-SEG_SA52-11")
      (footprint "eagle-import:SA52-11")
      (libsource (lib "eagle-import") (part "7-SEG_SA52-11"))
    )
    (comp (ref "LED80")
      (value "7-SEG_SA52-11")
      (footprint "eagle-import:SA52-11")
      (libsource (lib "eagle-import") (part "7-SEG_SA52-11"))
    )
    (comp (ref "LED81")
      (value "7-SEG_SA52-11")
      (footprint "eagle-import:SA52-11")
      (libsource (lib "eagle-import") (part "7-SEG_SA52-11"))
    )
    (comp (ref "LED82")
      (value "7-SEG_SA52-11")
      (footprint "eagle-import:SA52-11")
      (libsource (lib "eagle-import") (part "7-SEG_SA52-11"))
    )
    (comp (ref "LED83")
      (value "7-SEG_SA52-11")
      (footprint "eagle-import:SA52-11")
      (libsource (lib "eagle-import") (part "7-SEG_SA52-11"))
    )
    (comp (ref "LED84")
      (value "7-SEG_SA52-11")
      (footprint "eagle-import:SA52-11")
      (libsource (lib "eagle-import") (part "7-SEG_SA52-11"))
    )
    (comp (ref "LED85")
      (value "7-SEG_SA52-11")
      (footprint "eagle-import:SA52-11")
      (libsource (lib "eagle-import") (part "7-SEG_SA52-11"))
    )
    (comp (ref "LED86")
      (value "7-SEG_SA52-11")
      (footprint "eagle-import:SA52-11")
      (libsource (lib "eagle-import") (part "7-SEG_SA52-11"))
    )
    (comp (ref "LED87")
      (value "7-SEG_SA52-11")
      (footprint "eagle-import:SA52-11")
      (libsource (lib "eagle-import") (part "7-SEG_SA52-11"))
    )
    (comp (ref "LED88")
      (value "7-SEG_SA52-11")
      (footprint "eagle-import:SA52-11")
      (libsource (lib "eagle-import") (part "7-SEG_SA52-11"))
    )
    (comp (ref "LED89")
      (value "7-SEG_SA52-11")
      (footprint "eagle-import:SA52-11")
      (libsource (lib "eagle-import") (part "7-SEG_SA52-11"))
    )
    (comp (ref "LED90")
      (value "7-SEG_SA52-11")
      (footprint "eagle-import:SA52-11")
      (libsource (lib "eagle-import") (part "7-SEG_SA52-11"))
    )
    (comp (ref "LED91")
      (value "7-SEG_SA52-11")
      (footprint "eagle-import:SA52-11")
      (libsource (lib "eagle-import") (part "7-SEG_SA52-11"))
    )
    (comp (ref "LED92")
      (value "7-SEG_SA52-11")
      (footprint "eagle-import:SA52-11")
      (libsource (lib "eagle-import") (part "7-SEG_SA52-11"))
    )
    (comp (ref "LED93")
      (value "7-SEG_SA52-11")
      (footprint "eagle-import:SA52-11")
      (libsource (lib "eagle-import") (part "7-SEG_SA52-11"))
    )
    (comp (ref "LED94")
      (value "7-SEG_SA52-11")
      (footprint "eagle-import:SA52-11")
      (libsource (lib "eagle-import") (part "7-SEG_SA52-11"))
    )
    (comp (ref "LED95")
      (value "7-SEG_SA52-11")
      (footprint "eagle-import:SA52-11")
      (libsource (lib "eagle-import") (part "7-SEG_SA52-11"))
    )
    (comp (ref "LED96")
      (value "7-SEG_SA52-11")
      (footprint "eagle-import:SA52-11")
      (libsource (lib "eagle-import") (part "7-SEG_SA52-11"))
    )
    (comp (ref "R1")
      (value "12k")
      (footprint "eagle-import:0204_7")
      (libsource (lib "eagle-import") (part "R-US_0204/7"))
    )
    (comp (ref "R2")
      (value "12k")
      (footprint "eagle-import:0204_7")
      (libsource (lib "eagle-import") (part "R-US_0204/7"))
    )
    (comp (ref "R3")
      (value "12k")
      (footprint "eagle-import:0204_7")
      (libsource (lib "eagle-import") (part "R-US_0204/7"))
    )
    (comp (ref "R4")
      (value "12k")
      (footprint "eagle-import:0204_7")
      (libsource (lib "eagle-import") (part "R-US_0204/7"))
    )
    (comp (ref "R5")
      (value "12k")
      (footprint "eagle-import:0204_7")
      (libsource (lib "eagle-import") (part "R-US_0204/7"))
    )
    (comp (ref "R6")
      (value "12k")
      (footprint "eagle-import:0204_7")
      (libsource (lib "eagle-import") (part "R-US_0204/7"))
    )
    (comp (ref "R7")
      (value "12k")
      (footprint "eagle-import:0204_7")
      (libsource (lib "eagle-import") (part "R-US_0204/7"))
    )
    (comp (ref "R8")
      (value "12k")
      (footprint "eagle-import:0204_7")
      (libsource (lib "eagle-import") (part "R-US_0204/7"))
    )
    (comp (ref "R9")
      (value "12k")
      (footprint "eagle-import:0204_7")
      (libsource (lib "eagle-import") (part "R-US_0204/7"))
    )
    (comp (ref "R10")
      (value "12k")
      (footprint "eagle-import:0204_7")
      (libsource (lib "eagle-import") (part "R-US_0204/7"))
    )
    (comp (ref "R11")
      (value "12k")
      (footprint "eagle-import:0204_7")
      (libsource (lib "eagle-import") (part "R-US_0204/7"))
    )
    (comp (ref "R12")
      (value "12k")
      (footprint "eagle-import:0204_7")
      (libsource (lib "eagle-import") (part "R-US_0204/7"))
    )
    (comp (ref "R13")
      (value "12k")
      (footprint "eagle-import:0204_7")
      (libsource (lib "eagle-import") (part "R-US_0204/7"))
    )
    (comp (ref "R14")
      (value "880")
      (footprint "eagle-import:0204_7")
      (libsource (lib "eagle-import") (part "R-US_0204/7"))
    )
    (comp (ref "R15")
      (value "880")
      (footprint "eagle-import:0204_7")
      (libsource (lib "eagle-import") (part "R-US_0204/7"))
    )
    (comp (ref "R16")
      (value "880")
      (footprint "eagle-import:0204_7")
      (libsource (lib "eagle-import") (part "R-US_0204/7"))
    )
    (comp (ref "R17")
      (value "880")
      (footprint "eagle-import:0204_7")
      (libsource (lib "eagle-import") (part "R-US_0204/7"))
    )
    (comp (ref "R18")
      (value "880")
      (footprint "eagle-import:0204_7")
      (libsource (lib "eagle-import") (part "R-US_0204/7"))
    )
    (comp (ref "R19")
      (value "880")
      (footprint "eagle-import:0204_7")
      (libsource (lib "eagle-import") (part "R-US_0204/7"))
    )
    (comp (ref "R20")
      (value "880")
      (footprint "eagle-import:0204_7")
      (libsource (lib "eagle-import") (part "R-US_0204/7"))
    )
    (comp (ref "R21")
      (value "880")
      (footprint "eagle-import:0204_7")
      (libsource (lib "eagle-import") (part "R-US_0204/7"))
    )
    (comp (ref "R22")
      (value "880")
      (footprint "eagle-import:0204_7")
      (libsource (lib "eagle-import") (part "R-US_0204/7"))
    )
    (comp (ref "R23")
      (value "880")
      (footprint "eagle-import:0204_7")
      (libsource (lib "eagle-import") (part "R-US_0204/7"))
    )
    (comp (ref "R24")
      (value "880")
      (footprint "eagle-import:0204_7")
      (libsource (lib "eagle-import") (part "R-US_0204/7"))
    )
    (comp (ref "R25")
      (value "880")
      (footprint "eagle-import:0204_7")
      (libsource (lib "eagle-import") (part "R-US_0204/7"))
    )
    (comp (ref "R26")
      (value "880")
      (footprint "eagle-import:0204_7")
      (libsource (lib "eagle-import") (part "R-US_0204/7"))
    )
    (comp (ref "R27")
      (value "880")
      (footprint "eagle-import:0204_7")
      (libsource (lib "eagle-import") (part "R-US_0204/7"))
    )
    (comp (ref "R28")
      (value "880")
      (footprint "eagle-import:0204_7")
      (libsource (lib "eagle-import") (part "R-US_0204/7"))
    )
    (comp (ref "R29")
      (value "880")
      (footprint "eagle-import:0204_7")
      (libsource (lib "eagle-import") (part "R-US_0204/7"))
    )
    (comp (ref "R30")
      (value "880")
      (footprint "eagle-import:0204_7")
      (libsource (lib "eagle-import") (part "R-US_0204/7"))
    )
    (comp (ref "R31")
      (value "880")
      (footprint "eagle-import:0204_7")
      (libsource (lib "eagle-import") (part "R-US_0204/7"))
    )
    (comp (ref "R32")
      (value "880")
      (footprint "eagle-import:0204_7")
      (libsource (lib "eagle-import") (part "R-US_0204/7"))
    )
    (comp (ref "R33")
      (value "880")
      (footprint "eagle-import:0204_7")
      (libsource (lib "eagle-import") (part "R-US_0204/7"))
    )
    (comp (ref "R34")
      (value "880")
      (footprint "eagle-import:0204_7")
      (libsource (lib "eagle-import") (part "R-US_0204/7"))
    )
    (comp (ref "R35")
      (value "880")
      (footprint "eagle-import:0204_7")
      (libsource (lib "eagle-import") (part "R-US_0204/7"))
    )
    (comp (ref "R36")
      (value "880")
      (footprint "eagle-import:0204_7")
      (libsource (lib "eagle-import") (part "R-US_0204/7"))
    )
    (comp (ref "R37")
      (value "880")
      (footprint "eagle-import:0204_7")
      (libsource (lib "eagle-import") (part "R-US_0204/7"))
    )
    (comp (ref "SV1")
      (value "FE05-1")
      (footprint "eagle-import:FE05-1")
      (libsource (lib "eagle-import") (part "FE05-1"))
    )
    (comp (ref "SV2")
      (value "FE05-1")
      (footprint "eagle-import:FE05-1")
      (libsource (lib "eagle-import") (part "FE05-1"))
    )
  )
  (nets
    (net (code "1") (name "/CLK") (class "Default")
      (node (ref "R14") (pin "2") (pinfunction "2_2") (pintype "passive"))
      (node (ref "R16") (pin "2") (pinfunction "2_2") (pintype "passive"))
      (node (ref "R18") (pin "2") (pinfunction "2_2") (pintype "passive"))
      (node (ref "R20") (pin "2") (pinfunction "2_2") (pintype "passive"))
      (node (ref "R22") (pin "2") (pinfunction "2_2") (pintype "passive"))
      (node (ref "R24") (pin "2") (pinfunction "2_2") (pintype "passive"))
      (node (ref "R26") (pin "2") (pinfunction "2_2") (pintype "passive"))
      (node (ref "R28") (pin "2") (pinfunction "2_2") (pintype "passive"))
      (node (ref "R30") (pin "2") (pinfunction "2_2") (pintype "passive"))
      (node (ref "R32") (pin "2") (pinfunction "2_2") (pintype "passive"))
      (node (ref "R34") (pin "2") (pinfunction "2_2") (pintype "passive"))
      (node (ref "R36") (pin "2") (pinfunction "2_2") (pintype "passive"))
      (node (ref "SV1") (pin "3") (pinfunction "3_3") (pintype "passive"))
      (node (ref "SV2") (pin "3") (pinfunction "3_3") (pintype "passive"))
    )
    (net (code "2") (name "/DIN") (class "Default")
      (node (ref "IC1") (pin "1") (pinfunction "DIN_1") (pintype "input"))
      (node (ref "SV1") (pin "4") (pinfunction "4_4") (pintype "passive"))
    )
    (net (code "3") (name "/GND") (class "Default")
      (node (ref "C1") (pin "2") (pinfunction "2_2") (pintype "passive"))
      (node (ref "C10") (pin "2") (pinfunction "2_2") (pintype "passive"))
      (node (ref "C11") (pin "2") (pinfunction "2_2") (pintype "passive"))
      (node (ref "C12") (pin "2") (pinfunction "2_2") (pintype "passive"))
      (node (ref "C13") (pin "2") (pinfunction "2_2") (pintype "passive"))
      (node (ref "C14") (pin "2") (pinfunction "2_2") (pintype "passive"))
      (node (ref "C15") (pin "2") (pinfunction "2_2") (pintype "passive"))
      (node (ref "C16") (pin "2") (pinfunction "2_2") (pintype "passive"))
      (node (ref "C17") (pin "2") (pinfunction "2_2") (pintype "passive"))
      (node (ref "C18") (pin "2") (pinfunction "2_2") (pintype "passive"))
      (node (ref "C19") (pin "2") (pinfunction "2_2") (pintype "passive"))
      (node (ref "C2") (pin "2") (pinfunction "2_2") (pintype "passive"))
      (node (ref "C20") (pin "2") (pinfunction "2_2") (pintype "passive"))
      (node (ref "C21") (pin "2") (pinfunction "2_2") (pintype "passive"))
      (node (ref "C22") (pin "2") (pinfunction "2_2") (pintype "passive"))
      (node (ref "C23") (pin "2") (pinfunction "2_2") (pintype "passive"))
      (node (ref "C24") (pin "2") (pinfunction "2_2") (pintype "passive"))
      (node (ref "C3") (pin "2") (pinfunction "2_2") (pintype "passive"))
      (node (ref "C4") (pin "2") (pinfunction "2_2") (pintype "passive"))
      (node (ref "C5") (pin "2") (pinfunction "2_2") (pintype "passive"))
      (node (ref "C6") (pin "2") (pinfunction "2_2") (pintype "passive"))
      (node (ref "C7") (pin "2") (pinfunction "2_2") (pintype "passive"))
      (node (ref "C8") (pin "2") (pinfunction "2_2") (pintype "passive"))
      (node (ref "C9") (pin "2") (pinfunction "2_2") (pintype "passive"))
      (node (ref "IC1") (pin "4") (pinfunction "GND_4") (pintype "power_in"))
      (node (ref "IC1") (pin "9") (pinfunction "GND_9") (pintype "power_in"))
      (node (ref "IC10") (pin "4") (pinfunction "GND_4") (pintype "power_in"))
      (node (ref "IC10") (pin "9") (pinfunction "GND_9") (pintype "power_in"))
      (node (ref "IC11") (pin "4") (pinfunction "GND_4") (pintype "power_in"))
      (node (ref "IC11") (pin "9") (pinfunction "GND_9") (pintype "power_in"))
      (node (ref "IC12") (pin "4") (pinfunction "GND_4") (pintype "power_in"))
      (node (ref "IC12") (pin "9") (pinfunction "GND_9") (pintype "power_in"))
      (node (ref "IC2") (pin "4") (pinfunction "GND_4") (pintype "power_in"))
      (node (ref "IC2") (pin "9") (pinfunction "GND_9") (pintype "power_in"))
      (node (ref "IC3") (pin "4") (pinfunction "GND_4") (pintype "power_in"))
      (node (ref "IC3") (pin "9") (pinfunction "GND_9") (pintype "power_in"))
      (node (ref "IC4") (pin "4") (pinfunction "GND_4") (pintype "power_in"))
      (node (ref "IC4") (pin "9") (pinfunction "GND_9") (pintype "power_in"))
      (node (ref "IC5") (pin "4") (pinfunction "GND_4") (pintype "power_in"))
      (node (ref "IC5") (pin "9") (pinfunction "GND_9") (pintype "power_in"))
      (node (ref "IC6") (pin "4") (pinfunction "GND_4") (pintype "power_in"))
      (node (ref "IC6") (pin "9") (pinfunction "GND_9") (pintype "power_in"))
      (node (ref "IC7") (pin "4") (pinfunction "GND_4") (pintype "power_in"))
      (node (ref "IC7") (pin "9") (pinfunction "GND_9") (pintype "power_in"))
      (node (ref "IC8") (pin "4") (pinfunction "GND_4") (pintype "power_in"))
      (node (ref "IC8") (pin "9") (pinfunction "GND_9") (pintype "power_in"))
      (node (ref "IC9") (pin "4") (pinfunction "GND_4") (pintype "power_in"))
      (node (ref "IC9") (pin "9") (pinfunction "GND_9") (pintype "power_in"))
      (node (ref "R2") (pin "1") (pinfunction "1_1") (pintype "passive"))
      (node (ref "SV1") (pin "1") (pinfunction "1_1") (pintype "passive"))
      (node (ref "SV2") (pin "1") (pinfunction "1_1") (pintype "passive"))
    )
    (net (code "4") (name "/LOAD") (class "Default")
      (node (ref "R15") (pin "2") (pinfunction "2_2") (pintype "passive"))
      (node (ref "R17") (pin "2") (pinfunction "2_2") (pintype "passive"))
      (node (ref "R19") (pin "2") (pinfunction "2_2") (pintype "passive"))
      (node (ref "R2") (pin "2") (pinfunction "2_2") (pintype "passive"))
      (node (ref "R21") (pin "2") (pinfunction "2_2") (pintype "passive"))
      (node (ref "R23") (pin "2") (pinfunction "2_2") (pintype "passive"))
      (node (ref "R25") (pin "2") (pinfunction "2_2") (pintype "passive"))
      (node (ref "R27") (pin "2") (pinfunction "2_2") (pintype "passive"))
      (node (ref "R29") (pin "2") (pinfunction "2_2") (pintype "passive"))
      (node (ref "R31") (pin "2") (pinfunction "2_2") (pintype "passive"))
      (node (ref "R33") (pin "2") (pinfunction "2_2") (pintype "passive"))
      (node (ref "R35") (pin "2") (pinfunction "2_2") (pintype "passive"))
      (node (ref "R37") (pin "2") (pinfunction "2_2") (pintype "passive"))
      (node (ref "SV1") (pin "2") (pinfunction "2_2") (pintype "passive"))
      (node (ref "SV2") (pin "2") (pinfunction "2_2") (pintype "passive"))
    )
    (net (code "5") (name "/N$13") (class "Default")
      (node (ref "IC1") (pin "12") (pinfunction "LOAD_12") (pintype "input"))
      (node (ref "R15") (pin "1") (pinfunction "1_1") (pintype "passive"))
    )
    (net (code "6") (name "/VCC") (class "Default")
      (node (ref "C1") (pin "1") (pinfunction "1_1") (pintype "passive"))
      (node (ref "C10") (pin "1") (pinfunction "1_1") (pintype "passive"))
      (node (ref "C11") (pin "1") (pinfunction "1_1") (pintype "passive"))
      (node (ref "C12") (pin "1") (pinfunction "1_1") (pintype "passive"))
      (node (ref "C13") (pin "1") (pinfunction "1_1") (pintype "passive"))
      (node (ref "C14") (pin "1") (pinfunction "1_1") (pintype "passive"))
      (node (ref "C15") (pin "1") (pinfunction "1_1") (pintype "passive"))
      (node (ref "C16") (pin "1") (pinfunction "1_1") (pintype "passive"))
      (node (ref "C17") (pin "1") (pinfunction "1_1") (pintype "passive"))
      (node (ref "C18") (pin "1") (pinfunction "1_1") (pintype "passive"))
      (node (ref "C19") (pin "1") (pinfunction "1_1") (pintype "passive"))
      (node (ref "C2") (pin "1") (pinfunction "1_1") (pintype "passive"))
      (node (ref "C20") (pin "1") (pinfunction "1_1") (pintype "passive"))
      (node (ref "C21") (pin "1") (pinfunction "1_1") (pintype "passive"))
      (node (ref "C22") (pin "1") (pinfunction "1_1") (pintype "passive"))
      (node (ref "C23") (pin "1") (pinfunction "1_1") (pintype "passive"))
      (node (ref "C24") (pin "1") (pinfunction "1_1") (pintype "passive"))
      (node (ref "C3") (pin "1") (pinfunction "1_1") (pintype "passive"))
      (node (ref "C4") (pin "1") (pinfunction "1_1") (pintype "passive"))
      (node (ref "C5") (pin "1") (pinfunction "1_1") (pintype "passive"))
      (node (ref "C6") (pin "1") (pinfunction "1_1") (pintype "passive"))
      (node (ref "C7") (pin "1") (pinfunction "1_1") (pintype "passive"))
      (node (ref "C8") (pin "1") (pinfunction "1_1") (pintype "passive"))
      (node (ref "C9") (pin "1") (pinfunction "1_1") (pintype "passive"))
      (node (ref "IC1") (pin "19") (pinfunction "VCC_19") (pintype "power_in"))
      (node (ref "IC10") (pin "19") (pinfunction "VCC_19") (pintype "power_in"))
      (node (ref "IC11") (pin "19") (pinfunction "VCC_19") (pintype "power_in"))
      (node (ref "IC12") (pin "19") (pinfunction "VCC_19") (pintype "power_in"))
      (node (ref "IC2") (pin "19") (pinfunction "VCC_19") (pintype "power_in"))
      (node (ref "IC3") (pin "19") (pinfunction "VCC_19") (pintype "power_in"))
      (node (ref "IC4") (pin "19") (pinfunction "VCC_19") (pintype "power_in"))
      (node (ref "IC5") (pin "19") (pinfunction "VCC_19") (pintype "power_in"))
      (node (ref "IC6") (pin "19") (pinfunction "VCC_19") (pintype "power_in"))
      (node (ref "IC7") (pin "19") (pinfunction "VCC_19") (pintype "power_in"))
      (node (ref "IC8") (pin "19") (pinfunction "VCC_19") (pintype "power_in"))
      (node (ref "IC9") (pin "19") (pinfunction "VCC_19") (pintype "power_in"))
      (node (ref "R1") (pin "1") (pinfunction "1_1") (pintype "passive"))
      (node (ref "R10") (pin "1") (pinfunction "1_1") (pintype "passive"))
      (node (ref "R11") (pin "1") (pinfunction "1_1") (pintype "passive"))
      (node (ref "R12") (pin "1") (pinfunction "1_1") (pintype "passive"))
      (node (ref "R13") (pin "1") (pinfunction "1_1") (pintype "passive"))
      (node (ref "R3") (pin "1") (pinfunction "1_1") (pintype "passive"))
      (node (ref "R4") (pin "1") (pinfunction "1_1") (pintype "passive"))
      (node (ref "R5") (pin "1") (pinfunction "1_1") (pintype "passive"))
      (node (ref "R6") (pin "1") (pinfunction "1_1") (pintype "passive"))
      (node (ref "R7") (pin "1") (pinfunction "1_1") (pintype "passive"))
      (node (ref "R8") (pin "1") (pinfunction "1_1") (pintype "passive"))
      (node (ref "R9") (pin "1") (pinfunction "1_1") (pintype "passive"))
      (node (ref "SV1") (pin "5") (pinfunction "5_5") (pintype "passive"))
      (node (ref "SV2") (pin "5") (pinfunction "5_5") (pintype "passive"))
    )
    (net (code "7") (name "Net-(IC1-CLK)") (class "Default")
      (node (ref "IC1") (pin "13") (pinfunction "CLK_13") (pintype "input"))
      (node (ref "R14") (pin "1") (pinfunction "1_1") (pintype "passive"))
    )
    (net (code "8") (name "Net-(IC1-DIG0)") (class "Default")
      (node (ref "IC1") (pin "2") (pinfunction "DIG0_2") (pintype "output"))
      (node (ref "LED1") (pin "3") (pinfunction "COM_3") (pintype "passive"))
      (node (ref "LED1") (pin "8") (pinfunction "COM_8") (pintype "passive"))
    )
    (net (code "9") (name "Net-(IC1-DIG1)") (class "Default")
      (node (ref "IC1") (pin "11") (pinfunction "DIG1_11") (pintype "output"))
      (node (ref "LED2") (pin "3") (pinfunction "COM_3") (pintype "passive"))
      (node (ref "LED2") (pin "8") (pinfunction "COM_8") (pintype "passive"))
    )
    (net (code "10") (name "Net-(IC1-DIG2)") (class "Default")
      (node (ref "IC1") (pin "6") (pinfunction "DIG2_6") (pintype "output"))
      (node (ref "LED3") (pin "3") (pinfunction "COM_3") (pintype "passive"))
      (node (ref "LED3") (pin "8") (pinfunction "COM_8") (pintype "passive"))
    )
    (net (code "11") (name "Net-(IC1-DIG3)") (class "Default")
      (node (ref "IC1") (pin "7") (pinfunction "DIG3_7") (pintype "output"))
      (node (ref "LED4") (pin "3") (pinfunction "COM_3") (pintype "passive"))
      (node (ref "LED4") (pin "8") (pinfunction "COM_8") (pintype "passive"))
    )
    (net (code "12") (name "Net-(IC1-DIG4)") (class "Default")
      (node (ref "IC1") (pin "3") (pinfunction "DIG4_3") (pintype "output"))
      (node (ref "LED5") (pin "3") (pinfunction "COM_3") (pintype "passive"))
      (node (ref "LED5") (pin "8") (pinfunction "COM_8") (pintype "passive"))
    )
    (net (code "13") (name "Net-(IC1-DIG5)") (class "Default")
      (node (ref "IC1") (pin "10") (pinfunction "DIG5_10") (pintype "output"))
      (node (ref "LED6") (pin "3") (pinfunction "COM_3") (pintype "passive"))
      (node (ref "LED6") (pin "8") (pinfunction "COM_8") (pintype "passive"))
    )
    (net (code "14") (name "Net-(IC1-DIG6)") (class "Default")
      (node (ref "IC1") (pin "5") (pinfunction "DIG6_5") (pintype "output"))
      (node (ref "LED7") (pin "3") (pinfunction "COM_3") (pintype "passive"))
      (node (ref "LED7") (pin "8") (pinfunction "COM_8") (pintype "passive"))
    )
    (net (code "15") (name "Net-(IC1-DIG7)") (class "Default")
      (node (ref "IC1") (pin "8") (pinfunction "DIG7_8") (pintype "output"))
      (node (ref "LED8") (pin "3") (pinfunction "COM_3") (pintype "passive"))
      (node (ref "LED8") (pin "8") (pinfunction "COM_8") (pintype "passive"))
    )
    (net (code "16") (name "Net-(IC1-DOUT)") (class "Default")
      (node (ref "IC1") (pin "24") (pinfunction "DOUT_24") (pintype "output"))
      (node (ref "IC2") (pin "1") (pinfunction "DIN_1") (pintype "input"))
    )
    (net (code "17") (name "Net-(IC1-ISET)") (class "Default")
      (node (ref "IC1") (pin "18") (pinfunction "ISET_18") (pintype "input"))
      (node (ref "R1") (pin "2") (pinfunction "2_2") (pintype "passive"))
    )
    (net (code "18") (name "Net-(IC1-SEGA)") (class "Default")
      (node (ref "IC1") (pin "14") (pinfunction "SEGA_14") (pintype "output"))
      (node (ref "LED1") (pin "7") (pinfunction "A_7") (pintype "passive"))
      (node (ref "LED2") (pin "7") (pinfunction "A_7") (pintype "passive"))
      (node (ref "LED3") (pin "7") (pinfunction "A_7") (pintype "passive"))
      (node (ref "LED4") (pin "7") (pinfunction "A_7") (pintype "passive"))
      (node (ref "LED5") (pin "7") (pinfunction "A_7") (pintype "passive"))
      (node (ref "LED6") (pin "7") (pinfunction "A_7") (pintype "passive"))
      (node (ref "LED7") (pin "7") (pinfunction "A_7") (pintype "passive"))
      (node (ref "LED8") (pin "7") (pinfunction "A_7") (pintype "passive"))
    )
    (net (code "19") (name "Net-(IC1-SEGB)") (class "Default")
      (node (ref "IC1") (pin "16") (pinfunction "SEGB_16") (pintype "output"))
      (node (ref "LED1") (pin "6") (pinfunction "B_6") (pintype "passive"))
      (node (ref "LED2") (pin "6") (pinfunction "B_6") (pintype "passive"))
      (node (ref "LED3") (pin "6") (pinfunction "B_6") (pintype "passive"))
      (node (ref "LED4") (pin "6") (pinfunction "B_6") (pintype "passive"))
      (node (ref "LED5") (pin "6") (pinfunction "B_6") (pintype "passive"))
      (node (ref "LED6") (pin "6") (pinfunction "B_6") (pintype "passive"))
      (node (ref "LED7") (pin "6") (pinfunction "B_6") (pintype "passive"))
      (node (ref "LED8") (pin "6") (pinfunction "B_6") (pintype "passive"))
    )
    (net (code "20") (name "Net-(IC1-SEGC)") (class "Default")
      (node (ref "IC1") (pin "20") (pinfunction "SEGC_20") (pintype "output"))
      (node (ref "LED1") (pin "4") (pinfunction "C_4") (pintype "passive"))
      (node (ref "LED2") (pin "4") (pinfunction "C_4") (pintype "passive"))
      (node (ref "LED3") (pin "4") (pinfunction "C_4") (pintype "passive"))
      (node (ref "LED4") (pin "4") (pinfunction "C_4") (pintype "passive"))
      (node (ref "LED5") (pin "4") (pinfunction "C_4") (pintype "passive"))
      (node (ref "LED6") (pin "4") (pinfunction "C_4") (pintype "passive"))
      (node (ref "LED7") (pin "4") (pinfunction "C_4") (pintype "passive"))
      (node (ref "LED8") (pin "4") (pinfunction "C_4") (pintype "passive"))
    )
    (net (code "21") (name "Net-(IC1-SEGD)") (class "Default")
      (node (ref "IC1") (pin "23") (pinfunction "SEGD_23") (pintype "output"))
      (node (ref "LED1") (pin "2") (pinfunction "D_2") (pintype "passive"))
      (node (ref "LED2") (pin "2") (pinfunction "D_2") (pintype "passive"))
      (node (ref "LED3") (pin "2") (pinfunction "D_2") (pintype "passive"))
      (node (ref "LED4") (pin "2") (pinfunction "D_2") (pintype "passive"))
      (node (ref "LED5") (pin "2") (pinfunction "D_2") (pintype "passive"))
      (node (ref "LED6") (pin "2") (pinfunction "D_2") (pintype "passive"))
      (node (ref "LED7") (pin "2") (pinfunction "D_2") (pintype "passive"))
      (node (ref "LED8") (pin "2") (pinfunction "D_2") (pintype "passive"))
    )
    (net (code "22") (name "Net-(IC1-SEGDP)") (class "Default")
      (node (ref "IC1") (pin "22") (pinfunction "SEGDP_22") (pintype "output"))
      (node (ref "LED1") (pin "5") (pinfunction "DP_5") (pintype "passive"))
      (node (ref "LED2") (pin "5") (pinfunction "DP_5") (pintype "passive"))
      (node (ref "LED3") (pin "5") (pinfunction "DP_5") (pintype "passive"))
      (node (ref "LED4") (pin "5") (pinfunction "DP_5") (pintype "passive"))
      (node (ref "LED5") (pin "5") (pinfunction "DP_5") (pintype "passive"))
      (node (ref "LED6") (pin "5") (pinfunction "DP_5") (pintype "passive"))
      (node (ref "LED7") (pin "5") (pinfunction "DP_5") (pintype "passive"))
      (node (ref "LED8") (pin "5") (pinfunction "DP_5") (pintype "passive"))
    )
    (net (code "23") (name "Net-(IC1-SEGE)") (class "Default")
      (node (ref "IC1") (pin "21") (pinfunction "SEGE_21") (pintype "output"))
      (node (ref "LED1") (pin "1") (pinfunction "E_1") (pintype "passive"))
      (node (ref "LED2") (pin "1") (pinfunction "E_1") (pintype "passive"))
      (node (ref "LED3") (pin "1") (pinfunction "E_1") (pintype "passive"))
      (node (ref "LED4") (pin "1") (pinfunction "E_1") (pintype "passive"))
      (node (ref "LED5") (pin "1") (pinfunction "E_1") (pintype "passive"))
      (node (ref "LED6") (pin "1") (pinfunction "E_1") (pintype "passive"))
      (node (ref "LED7") (pin "1") (pinfunction "E_1") (pintype "passive"))
      (node (ref "LED8") (pin "1") (pinfunction "E_1") (pintype "passive"))
    )
    (net (code "24") (name "Net-(IC1-SEGF)") (class "Default")
      (node (ref "IC1") (pin "15") (pinfunction "SEGF_15") (pintype "output"))
      (node (ref "LED1") (pin "9") (pinfunction "F_9") (pintype "passive"))
      (node (ref "LED2") (pin "9") (pinfunction "F_9") (pintype "passive"))
      (node (ref "LED3") (pin "9") (pinfunction "F_9") (pintype "passive"))
      (node (ref "LED4") (pin "9") (pinfunction "F_9") (pintype "passive"))
      (node (ref "LED5") (pin "9") (pinfunction "F_9") (pintype "passive"))
      (node (ref "LED6") (pin "9") (pinfunction "F_9") (pintype "passive"))
      (node (ref "LED7") (pin "9") (pinfunction "F_9") (pintype "passive"))
      (node (ref "LED8") (pin "9") (pinfunction "F_9") (pintype "passive"))
    )
    (net (code "25") (name "Net-(IC1-SEGG)") (class "Default")
      (node (ref "IC1") (pin "17") (pinfunction "SEGG_17") (pintype "output"))
      (node (ref "LED1") (pin "10") (pinfunction "G_10") (pintype "passive"))
      (node (ref "LED2") (pin "10") (pinfunction "G_10") (pintype "passive"))
      (node (ref "LED3") (pin "10") (pinfunction "G_10") (pintype "passive"))
      (node (ref "LED4") (pin "10") (pinfunction "G_10") (pintype "passive"))
      (node (ref "LED5") (pin "10") (pinfunction "G_10") (pintype "passive"))
      (node (ref "LED6") (pin "10") (pinfunction "G_10") (pintype "passive"))
      (node (ref "LED7") (pin "10") (pinfunction "G_10") (pintype "passive"))
      (node (ref "LED8") (pin "10") (pinfunction "G_10") (pintype "passive"))
    )
    (net (code "26") (name "Net-(IC2-CLK)") (class "Default")
      (node (ref "IC2") (pin "13") (pinfunction "CLK_13") (pintype "input"))
      (node (ref "R16") (pin "1") (pinfunction "1_1") (pintype "passive"))
    )
    (net (code "27") (name "Net-(IC2-DIG0)") (class "Default")
      (node (ref "IC2") (pin "2") (pinfunction "DIG0_2") (pintype "output"))
      (node (ref "LED9") (pin "3") (pinfunction "COM_3") (pintype "passive"))
      (node (ref "LED9") (pin "8") (pinfunction "COM_8") (pintype "passive"))
    )
    (net (code "28") (name "Net-(IC2-DIG1)") (class "Default")
      (node (ref "IC2") (pin "11") (pinfunction "DIG1_11") (pintype "output"))
      (node (ref "LED10") (pin "3") (pinfunction "COM_3") (pintype "passive"))
      (node (ref "LED10") (pin "8") (pinfunction "COM_8") (pintype "passive"))
    )
    (net (code "29") (name "Net-(IC2-DIG2)") (class "Default")
      (node (ref "IC2") (pin "6") (pinfunction "DIG2_6") (pintype "output"))
      (node (ref "LED11") (pin "3") (pinfunction "COM_3") (pintype "passive"))
      (node (ref "LED11") (pin "8") (pinfunction "COM_8") (pintype "passive"))
    )
    (net (code "30") (name "Net-(IC2-DIG3)") (class "Default")
      (node (ref "IC2") (pin "7") (pinfunction "DIG3_7") (pintype "output"))
      (node (ref "LED12") (pin "3") (pinfunction "COM_3") (pintype "passive"))
      (node (ref "LED12") (pin "8") (pinfunction "COM_8") (pintype "passive"))
    )
    (net (code "31") (name "Net-(IC2-DIG4)") (class "Default")
      (node (ref "IC2") (pin "3") (pinfunction "DIG4_3") (pintype "output"))
      (node (ref "LED13") (pin "3") (pinfunction "COM_3") (pintype "passive"))
      (node (ref "LED13") (pin "8") (pinfunction "COM_8") (pintype "passive"))
    )
    (net (code "32") (name "Net-(IC2-DIG5)") (class "Default")
      (node (ref "IC2") (pin "10") (pinfunction "DIG5_10") (pintype "output"))
      (node (ref "LED14") (pin "3") (pinfunction "COM_3") (pintype "passive"))
      (node (ref "LED14") (pin "8") (pinfunction "COM_8") (pintype "passive"))
    )
    (net (code "33") (name "Net-(IC2-DIG6)") (class "Default")
      (node (ref "IC2") (pin "5") (pinfunction "DIG6_5") (pintype "output"))
      (node (ref "LED15") (pin "3") (pinfunction "COM_3") (pintype "passive"))
      (node (ref "LED15") (pin "8") (pinfunction "COM_8") (pintype "passive"))
    )
    (net (code "34") (name "Net-(IC2-DIG7)") (class "Default")
      (node (ref "IC2") (pin "8") (pinfunction "DIG7_8") (pintype "output"))
      (node (ref "LED16") (pin "3") (pinfunction "COM_3") (pintype "passive"))
      (node (ref "LED16") (pin "8") (pinfunction "COM_8") (pintype "passive"))
    )
    (net (code "35") (name "Net-(IC2-DOUT)") (class "Default")
      (node (ref "IC2") (pin "24") (pinfunction "DOUT_24") (pintype "output"))
      (node (ref "IC3") (pin "1") (pinfunction "DIN_1") (pintype "input"))
    )
    (net (code "36") (name "Net-(IC2-ISET)") (class "Default")
      (node (ref "IC2") (pin "18") (pinfunction "ISET_18") (pintype "input"))
      (node (ref "R3") (pin "2") (pinfunction "2_2") (pintype "passive"))
    )
    (net (code "37") (name "Net-(IC2-LOAD)") (class "Default")
      (node (ref "IC2") (pin "12") (pinfunction "LOAD_12") (pintype "input"))
      (node (ref "R17") (pin "1") (pinfunction "1_1") (pintype "passive"))
    )
    (net (code "38") (name "Net-(IC2-SEGA)") (class "Default")
      (node (ref "IC2") (pin "14") (pinfunction "SEGA_14") (pintype "output"))
      (node (ref "LED10") (pin "7") (pinfunction "A_7") (pintype "passive"))
      (node (ref "LED11") (pin "7") (pinfunction "A_7") (pintype "passive"))
      (node (ref "LED12") (pin "7") (pinfunction "A_7") (pintype "passive"))
      (node (ref "LED13") (pin "7") (pinfunction "A_7") (pintype "passive"))
      (node (ref "LED14") (pin "7") (pinfunction "A_7") (pintype "passive"))
      (node (ref "LED15") (pin "7") (pinfunction "A_7") (pintype "passive"))
      (node (ref "LED16") (pin "7") (pinfunction "A_7") (pintype "passive"))
      (node (ref "LED9") (pin "7") (pinfunction "A_7") (pintype "passive"))
    )
    (net (code "39") (name "Net-(IC2-SEGB)") (class "Default")
      (node (ref "IC2") (pin "16") (pinfunction "SEGB_16") (pintype "output"))
      (node (ref "LED10") (pin "6") (pinfunction "B_6") (pintype "passive"))
      (node (ref "LED11") (pin "6") (pinfunction "B_6") (pintype "passive"))
      (node (ref "LED12") (pin "6") (pinfunction "B_6") (pintype "passive"))
      (node (ref "LED13") (pin "6") (pinfunction "B_6") (pintype "passive"))
      (node (ref "LED14") (pin "6") (pinfunction "B_6") (pintype "passive"))
      (node (ref "LED15") (pin "6") (pinfunction "B_6") (pintype "passive"))
      (node (ref "LED16") (pin "6") (pinfunction "B_6") (pintype "passive"))
      (node (ref "LED9") (pin "6") (pinfunction "B_6") (pintype "passive"))
    )
    (net (code "40") (name "Net-(IC2-SEGC)") (class "Default")
      (node (ref "IC2") (pin "20") (pinfunction "SEGC_20") (pintype "output"))
      (node (ref "LED10") (pin "4") (pinfunction "C_4") (pintype "passive"))
      (node (ref "LED11") (pin "4") (pinfunction "C_4") (pintype "passive"))
      (node (ref "LED12") (pin "4") (pinfunction "C_4") (pintype "passive"))
      (node (ref "LED13") (pin "4") (pinfunction "C_4") (pintype "passive"))
      (node (ref "LED14") (pin "4") (pinfunction "C_4") (pintype "passive"))
      (node (ref "LED15") (pin "4") (pinfunction "C_4") (pintype "passive"))
      (node (ref "LED16") (pin "4") (pinfunction "C_4") (pintype "passive"))
      (node (ref "LED9") (pin "4") (pinfunction "C_4") (pintype "passive"))
    )
    (net (code "41") (name "Net-(IC2-SEGD)") (class "Default")
      (node (ref "IC2") (pin "23") (pinfunction "SEGD_23") (pintype "output"))
      (node (ref "LED10") (pin "2") (pinfunction "D_2") (pintype "passive"))
      (node (ref "LED11") (pin "2") (pinfunction "D_2") (pintype "passive"))
      (node (ref "LED12") (pin "2") (pinfunction "D_2") (pintype "passive"))
      (node (ref "LED13") (pin "2") (pinfunction "D_2") (pintype "passive"))
      (node (ref "LED14") (pin "2") (pinfunction "D_2") (pintype "passive"))
      (node (ref "LED15") (pin "2") (pinfunction "D_2") (pintype "passive"))
      (node (ref "LED16") (pin "2") (pinfunction "D_2") (pintype "passive"))
      (node (ref "LED9") (pin "2") (pinfunction "D_2") (pintype "passive"))
    )
    (net (code "42") (name "Net-(IC2-SEGDP)") (class "Default")
      (node (ref "IC2") (pin "22") (pinfunction "SEGDP_22") (pintype "output"))
      (node (ref "LED10") (pin "5") (pinfunction "DP_5") (pintype "passive"))
      (node (ref "LED11") (pin "5") (pinfunction "DP_5") (pintype "passive"))
      (node (ref "LED12") (pin "5") (pinfunction "DP_5") (pintype "passive"))
      (node (ref "LED13") (pin "5") (pinfunction "DP_5") (pintype "passive"))
      (node (ref "LED14") (pin "5") (pinfunction "DP_5") (pintype "passive"))
      (node (ref "LED15") (pin "5") (pinfunction "DP_5") (pintype "passive"))
      (node (ref "LED16") (pin "5") (pinfunction "DP_5") (pintype "passive"))
      (node (ref "LED9") (pin "5") (pinfunction "DP_5") (pintype "passive"))
    )
    (net (code "43") (name "Net-(IC2-SEGE)") (class "Default")
      (node (ref "IC2") (pin "21") (pinfunction "SEGE_21") (pintype "output"))
      (node (ref "LED10") (pin "1") (pinfunction "E_1") (pintype "passive"))
      (node (ref "LED11") (pin "1") (pinfunction "E_1") (pintype "passive"))
      (node (ref "LED12") (pin "1") (pinfunction "E_1") (pintype "passive"))
      (node (ref "LED13") (pin "1") (pinfunction "E_1") (pintype "passive"))
      (node (ref "LED14") (pin "1") (pinfunction "E_1") (pintype "passive"))
      (node (ref "LED15") (pin "1") (pinfunction "E_1") (pintype "passive"))
      (node (ref "LED16") (pin "1") (pinfunction "E_1") (pintype "passive"))
      (node (ref "LED9") (pin "1") (pinfunction "E_1") (pintype "passive"))
    )
    (net (code "44") (name "Net-(IC2-SEGF)") (class "Default")
      (node (ref "IC2") (pin "15") (pinfunction "SEGF_15") (pintype "output"))
      (node (ref "LED10") (pin "9") (pinfunction "F_9") (pintype "passive"))
      (node (ref "LED11") (pin "9") (pinfunction "F_9") (pintype "passive"))
      (node (ref "LED12") (pin "9") (pinfunction "F_9") (pintype "passive"))
      (node (ref "LED13") (pin "9") (pinfunction "F_9") (pintype "passive"))
      (node (ref "LED14") (pin "9") (pinfunction "F_9") (pintype "passive"))
      (node (ref "LED15") (pin "9") (pinfunction "F_9") (pintype "passive"))
      (node (ref "LED16") (pin "9") (pinfunction "F_9") (pintype "passive"))
      (node (ref "LED9") (pin "9") (pinfunction "F_9") (pintype "passive"))
    )
    (net (code "45") (name "Net-(IC2-SEGG)") (class "Default")
      (node (ref "IC2") (pin "17") (pinfunction "SEGG_17") (pintype "output"))
      (node (ref "LED10") (pin "10") (pinfunction "G_10") (pintype "passive"))
      (node (ref "LED11") (pin "10") (pinfunction "G_10") (pintype "passive"))
      (node (ref "LED12") (pin "10") (pinfunction "G_10") (pintype "passive"))
      (node (ref "LED13") (pin "10") (pinfunction "G_10") (pintype "passive"))
      (node (ref "LED14") (pin "10") (pinfunction "G_10") (pintype "passive"))
      (node (ref "LED15") (pin "10") (pinfunction "G_10") (pintype "passive"))
      (node (ref "LED16") (pin "10") (pinfunction "G_10") (pintype "passive"))
      (node (ref "LED9") (pin "10") (pinfunction "G_10") (pintype "passive"))
    )
    (net (code "46") (name "Net-(IC3-CLK)") (class "Default")
      (node (ref "IC3") (pin "13") (pinfunction "CLK_13") (pintype "input"))
      (node (ref "R18") (pin "1") (pinfunction "1_1") (pintype "passive"))
    )
    (net (code "47") (name "Net-(IC3-DIG0)") (class "Default")
      (node (ref "IC3") (pin "2") (pinfunction "DIG0_2") (pintype "output"))
      (node (ref "LED17") (pin "3") (pinfunction "COM_3") (pintype "passive"))
      (node (ref "LED17") (pin "8") (pinfunction "COM_8") (pintype "passive"))
    )
    (net (code "48") (name "Net-(IC3-DIG1)") (class "Default")
      (node (ref "IC3") (pin "11") (pinfunction "DIG1_11") (pintype "output"))
      (node (ref "LED18") (pin "3") (pinfunction "COM_3") (pintype "passive"))
      (node (ref "LED18") (pin "8") (pinfunction "COM_8") (pintype "passive"))
    )
    (net (code "49") (name "Net-(IC3-DIG2)") (class "Default")
      (node (ref "IC3") (pin "6") (pinfunction "DIG2_6") (pintype "output"))
      (node (ref "LED19") (pin "3") (pinfunction "COM_3") (pintype "passive"))
      (node (ref "LED19") (pin "8") (pinfunction "COM_8") (pintype "passive"))
    )
    (net (code "50") (name "Net-(IC3-DIG3)") (class "Default")
      (node (ref "IC3") (pin "7") (pinfunction "DIG3_7") (pintype "output"))
      (node (ref "LED20") (pin "3") (pinfunction "COM_3") (pintype "passive"))
      (node (ref "LED20") (pin "8") (pinfunction "COM_8") (pintype "passive"))
    )
    (net (code "51") (name "Net-(IC3-DIG4)") (class "Default")
      (node (ref "IC3") (pin "3") (pinfunction "DIG4_3") (pintype "output"))
      (node (ref "LED21") (pin "3") (pinfunction "COM_3") (pintype "passive"))
      (node (ref "LED21") (pin "8") (pinfunction "COM_8") (pintype "passive"))
    )
    (net (code "52") (name "Net-(IC3-DIG5)") (class "Default")
      (node (ref "IC3") (pin "10") (pinfunction "DIG5_10") (pintype "output"))
      (node (ref "LED22") (pin "3") (pinfunction "COM_3") (pintype "passive"))
      (node (ref "LED22") (pin "8") (pinfunction "COM_8") (pintype "passive"))
    )
    (net (code "53") (name "Net-(IC3-DIG6)") (class "Default")
      (node (ref "IC3") (pin "5") (pinfunction "DIG6_5") (pintype "output"))
      (node (ref "LED23") (pin "3") (pinfunction "COM_3") (pintype "passive"))
      (node (ref "LED23") (pin "8") (pinfunction "COM_8") (pintype "passive"))
    )
    (net (code "54") (name "Net-(IC3-DIG7)") (class "Default")
      (node (ref "IC3") (pin "8") (pinfunction "DIG7_8") (pintype "output"))
      (node (ref "LED24") (pin "3") (pinfunction "COM_3") (pintype "passive"))
      (node (ref "LED24") (pin "8") (pinfunction "COM_8") (pintype "passive"))
    )
    (net (code "55") (name "Net-(IC3-DOUT)") (class "Default")
      (node (ref "IC3") (pin "24") (pinfunction "DOUT_24") (pintype "output"))
      (node (ref "IC4") (pin "1") (pinfunction "DIN_1") (pintype "input"))
    )
    (net (code "56") (name "Net-(IC3-ISET)") (class "Default")
      (node (ref "IC3") (pin "18") (pinfunction "ISET_18") (pintype "input"))
      (node (ref "R4") (pin "2") (pinfunction "2_2") (pintype "passive"))
    )
    (net (code "57") (name "Net-(IC3-LOAD)") (class "Default")
      (node (ref "IC3") (pin "12") (pinfunction "LOAD_12") (pintype "input"))
      (node (ref "R19") (pin "1") (pinfunction "1_1") (pintype "passive"))
    )
    (net (code "58") (name "Net-(IC3-SEGA)") (class "Default")
      (node (ref "IC3") (pin "14") (pinfunction "SEGA_14") (pintype "output"))
      (node (ref "LED17") (pin "7") (pinfunction "A_7") (pintype "passive"))
      (node (ref "LED18") (pin "7") (pinfunction "A_7") (pintype "passive"))
      (node (ref "LED19") (pin "7") (pinfunction "A_7") (pintype "passive"))
      (node (ref "LED20") (pin "7") (pinfunction "A_7") (pintype "passive"))
      (node (ref "LED21") (pin "7") (pinfunction "A_7") (pintype "passive"))
      (node (ref "LED22") (pin "7") (pinfunction "A_7") (pintype "passive"))
      (node (ref "LED23") (pin "7") (pinfunction "A_7") (pintype "passive"))
      (node (ref "LED24") (pin "7") (pinfunction "A_7") (pintype "passive"))
    )
    (net (code "59") (name "Net-(IC3-SEGB)") (class "Default")
      (node (ref "IC3") (pin "16") (pinfunction "SEGB_16") (pintype "output"))
      (node (ref "LED17") (pin "6") (pinfunction "B_6") (pintype "passive"))
      (node (ref "LED18") (pin "6") (pinfunction "B_6") (pintype "passive"))
      (node (ref "LED19") (pin "6") (pinfunction "B_6") (pintype "passive"))
      (node (ref "LED20") (pin "6") (pinfunction "B_6") (pintype "passive"))
      (node (ref "LED21") (pin "6") (pinfunction "B_6") (pintype "passive"))
      (node (ref "LED22") (pin "6") (pinfunction "B_6") (pintype "passive"))
      (node (ref "LED23") (pin "6") (pinfunction "B_6") (pintype "passive"))
      (node (ref "LED24") (pin "6") (pinfunction "B_6") (pintype "passive"))
    )
    (net (code "60") (name "Net-(IC3-SEGC)") (class "Default")
      (node (ref "IC3") (pin "20") (pinfunction "SEGC_20") (pintype "output"))
      (node (ref "LED17") (pin "4") (pinfunction "C_4") (pintype "passive"))
      (node (ref "LED18") (pin "4") (pinfunction "C_4") (pintype "passive"))
      (node (ref "LED19") (pin "4") (pinfunction "C_4") (pintype "passive"))
      (node (ref "LED20") (pin "4") (pinfunction "C_4") (pintype "passive"))
      (node (ref "LED21") (pin "4") (pinfunction "C_4") (pintype "passive"))
      (node (ref "LED22") (pin "4") (pinfunction "C_4") (pintype "passive"))
      (node (ref "LED23") (pin "4") (pinfunction "C_4") (pintype "passive"))
      (node (ref "LED24") (pin "4") (pinfunction "C_4") (pintype "passive"))
    )
    (net (code "61") (name "Net-(IC3-SEGD)") (class "Default")
      (node (ref "IC3") (pin "23") (pinfunction "SEGD_23") (pintype "output"))
      (node (ref "LED17") (pin "2") (pinfunction "D_2") (pintype "passive"))
      (node (ref "LED18") (pin "2") (pinfunction "D_2") (pintype "passive"))
      (node (ref "LED19") (pin "2") (pinfunction "D_2") (pintype "passive"))
      (node (ref "LED20") (pin "2") (pinfunction "D_2") (pintype "passive"))
      (node (ref "LED21") (pin "2") (pinfunction "D_2") (pintype "passive"))
      (node (ref "LED22") (pin "2") (pinfunction "D_2") (pintype "passive"))
      (node (ref "LED23") (pin "2") (pinfunction "D_2") (pintype "passive"))
      (node (ref "LED24") (pin "2") (pinfunction "D_2") (pintype "passive"))
    )
    (net (code "62") (name "Net-(IC3-SEGDP)") (class "Default")
      (node (ref "IC3") (pin "22") (pinfunction "SEGDP_22") (pintype "output"))
      (node (ref "LED17") (pin "5") (pinfunction "DP_5") (pintype "passive"))
      (node (ref "LED18") (pin "5") (pinfunction "DP_5") (pintype "passive"))
      (node (ref "LED19") (pin "5") (pinfunction "DP_5") (pintype "passive"))
      (node (ref "LED20") (pin "5") (pinfunction "DP_5") (pintype "passive"))
      (node (ref "LED21") (pin "5") (pinfunction "DP_5") (pintype "passive"))
      (node (ref "LED22") (pin "5") (pinfunction "DP_5") (pintype "passive"))
      (node (ref "LED23") (pin "5") (pinfunction "DP_5") (pintype "passive"))
      (node (ref "LED24") (pin "5") (pinfunction "DP_5") (pintype "passive"))
    )
    (net (code "63") (name "Net-(IC3-SEGE)") (class "Default")
      (node (ref "IC3") (pin "21") (pinfunction "SEGE_21") (pintype "output"))
      (node (ref "LED17") (pin "1") (pinfunction "E_1") (pintype "passive"))
      (node (ref "LED18") (pin "1") (pinfunction "E_1") (pintype "passive"))
      (node (ref "LED19") (pin "1") (pinfunction "E_1") (pintype "passive"))
      (node (ref "LED20") (pin "1") (pinfunction "E_1") (pintype "passive"))
      (node (ref "LED21") (pin "1") (pinfunction "E_1") (pintype "passive"))
      (node (ref "LED22") (pin "1") (pinfunction "E_1") (pintype "passive"))
      (node (ref "LED23") (pin "1") (pinfunction "E_1") (pintype "passive"))
      (node (ref "LED24") (pin "1") (pinfunction "E_1") (pintype "passive"))
    )
    (net (code "64") (name "Net-(IC3-SEGF)") (class "Default")
      (node (ref "IC3") (pin "15") (pinfunction "SEGF_15") (pintype "output"))
      (node (ref "LED17") (pin "9") (pinfunction "F_9") (pintype "passive"))
      (node (ref "LED18") (pin "9") (pinfunction "F_9") (pintype "passive"))
      (node (ref "LED19") (pin "9") (pinfunction "F_9") (pintype "passive"))
      (node (ref "LED20") (pin "9") (pinfunction "F_9") (pintype "passive"))
      (node (ref "LED21") (pin "9") (pinfunction "F_9") (pintype "passive"))
      (node (ref "LED22") (pin "9") (pinfunction "F_9") (pintype "passive"))
      (node (ref "LED23") (pin "9") (pinfunction "F_9") (pintype "passive"))
      (node (ref "LED24") (pin "9") (pinfunction "F_9") (pintype "passive"))
    )
    (net (code "65") (name "Net-(IC3-SEGG)") (class "Default")
      (node (ref "IC3") (pin "17") (pinfunction "SEGG_17") (pintype "output"))
      (node (ref "LED17") (pin "10") (pinfunction "G_10") (pintype "passive"))
      (node (ref "LED18") (pin "10") (pinfunction "G_10") (pintype "passive"))
      (node (ref "LED19") (pin "10") (pinfunction "G_10") (pintype "passive"))
      (node (ref "LED20") (pin "10") (pinfunction "G_10") (pintype "passive"))
      (node (ref "LED21") (pin "10") (pinfunction "G_10") (pintype "passive"))
      (node (ref "LED22") (pin "10") (pinfunction "G_10") (pintype "passive"))
      (node (ref "LED23") (pin "10") (pinfunction "G_10") (pintype "passive"))
      (node (ref "LED24") (pin "10") (pinfunction "G_10") (pintype "passive"))
    )
    (net (code "66") (name "Net-(IC4-CLK)") (class "Default")
      (node (ref "IC4") (pin "13") (pinfunction "CLK_13") (pintype "input"))
      (node (ref "R20") (pin "1") (pinfunction "1_1") (pintype "passive"))
    )
    (net (code "67") (name "Net-(IC4-DIG0)") (class "Default")
      (node (ref "IC4") (pin "2") (pinfunction "DIG0_2") (pintype "output"))
      (node (ref "LED25") (pin "3") (pinfunction "COM_3") (pintype "passive"))
      (node (ref "LED25") (pin "8") (pinfunction "COM_8") (pintype "passive"))
    )
    (net (code "68") (name "Net-(IC4-DIG1)") (class "Default")
      (node (ref "IC4") (pin "11") (pinfunction "DIG1_11") (pintype "output"))
      (node (ref "LED26") (pin "3") (pinfunction "COM_3") (pintype "passive"))
      (node (ref "LED26") (pin "8") (pinfunction "COM_8") (pintype "passive"))
    )
    (net (code "69") (name "Net-(IC4-DIG2)") (class "Default")
      (node (ref "IC4") (pin "6") (pinfunction "DIG2_6") (pintype "output"))
      (node (ref "LED27") (pin "3") (pinfunction "COM_3") (pintype "passive"))
      (node (ref "LED27") (pin "8") (pinfunction "COM_8") (pintype "passive"))
    )
    (net (code "70") (name "Net-(IC4-DIG3)") (class "Default")
      (node (ref "IC4") (pin "7") (pinfunction "DIG3_7") (pintype "output"))
      (node (ref "LED28") (pin "3") (pinfunction "COM_3") (pintype "passive"))
      (node (ref "LED28") (pin "8") (pinfunction "COM_8") (pintype "passive"))
    )
    (net (code "71") (name "Net-(IC4-DIG4)") (class "Default")
      (node (ref "IC4") (pin "3") (pinfunction "DIG4_3") (pintype "output"))
      (node (ref "LED29") (pin "3") (pinfunction "COM_3") (pintype "passive"))
      (node (ref "LED29") (pin "8") (pinfunction "COM_8") (pintype "passive"))
    )
    (net (code "72") (name "Net-(IC4-DIG5)") (class "Default")
      (node (ref "IC4") (pin "10") (pinfunction "DIG5_10") (pintype "output"))
      (node (ref "LED30") (pin "3") (pinfunction "COM_3") (pintype "passive"))
      (node (ref "LED30") (pin "8") (pinfunction "COM_8") (pintype "passive"))
    )
    (net (code "73") (name "Net-(IC4-DIG6)") (class "Default")
      (node (ref "IC4") (pin "5") (pinfunction "DIG6_5") (pintype "output"))
      (node (ref "LED31") (pin "3") (pinfunction "COM_3") (pintype "passive"))
      (node (ref "LED31") (pin "8") (pinfunction "COM_8") (pintype "passive"))
    )
    (net (code "74") (name "Net-(IC4-DIG7)") (class "Default")
      (node (ref "IC4") (pin "8") (pinfunction "DIG7_8") (pintype "output"))
      (node (ref "LED32") (pin "3") (pinfunction "COM_3") (pintype "passive"))
      (node (ref "LED32") (pin "8") (pinfunction "COM_8") (pintype "passive"))
    )
    (net (code "75") (name "Net-(IC4-DOUT)") (class "Default")
      (node (ref "IC4") (pin "24") (pinfunction "DOUT_24") (pintype "output"))
      (node (ref "IC5") (pin "1") (pinfunction "DIN_1") (pintype "input"))
    )
    (net (code "76") (name "Net-(IC4-ISET)") (class "Default")
      (node (ref "IC4") (pin "18") (pinfunction "ISET_18") (pintype "input"))
      (node (ref "R5") (pin "2") (pinfunction "2_2") (pintype "passive"))
    )
    (net (code "77") (name "Net-(IC4-LOAD)") (class "Default")
      (node (ref "IC4") (pin "12") (pinfunction "LOAD_12") (pintype "input"))
      (node (ref "R21") (pin "1") (pinfunction "1_1") (pintype "passive"))
    )
    (net (code "78") (name "Net-(IC4-SEGA)") (class "Default")
      (node (ref "IC4") (pin "14") (pinfunction "SEGA_14") (pintype "output"))
      (node (ref "LED25") (pin "7") (pinfunction "A_7") (pintype "passive"))
      (node (ref "LED26") (pin "7") (pinfunction "A_7") (pintype "passive"))
      (node (ref "LED27") (pin "7") (pinfunction "A_7") (pintype "passive"))
      (node (ref "LED28") (pin "7") (pinfunction "A_7") (pintype "passive"))
      (node (ref "LED29") (pin "7") (pinfunction "A_7") (pintype "passive"))
      (node (ref "LED30") (pin "7") (pinfunction "A_7") (pintype "passive"))
      (node (ref "LED31") (pin "7") (pinfunction "A_7") (pintype "passive"))
      (node (ref "LED32") (pin "7") (pinfunction "A_7") (pintype "passive"))
    )
    (net (code "79") (name "Net-(IC4-SEGB)") (class "Default")
      (node (ref "IC4") (pin "16") (pinfunction "SEGB_16") (pintype "output"))
      (node (ref "LED25") (pin "6") (pinfunction "B_6") (pintype "passive"))
      (node (ref "LED26") (pin "6") (pinfunction "B_6") (pintype "passive"))
      (node (ref "LED27") (pin "6") (pinfunction "B_6") (pintype "passive"))
      (node (ref "LED28") (pin "6") (pinfunction "B_6") (pintype "passive"))
      (node (ref "LED29") (pin "6") (pinfunction "B_6") (pintype "passive"))
      (node (ref "LED30") (pin "6") (pinfunction "B_6") (pintype "passive"))
      (node (ref "LED31") (pin "6") (pinfunction "B_6") (pintype "passive"))
      (node (ref "LED32") (pin "6") (pinfunction "B_6") (pintype "passive"))
    )
    (net (code "80") (name "Net-(IC4-SEGC)") (class "Default")
      (node (ref "IC4") (pin "20") (pinfunction "SEGC_20") (pintype "output"))
      (node (ref "LED25") (pin "4") (pinfunction "C_4") (pintype "passive"))
      (node (ref "LED26") (pin "4") (pinfunction "C_4") (pintype "passive"))
      (node (ref "LED27") (pin "4") (pinfunction "C_4") (pintype "passive"))
      (node (ref "LED28") (pin "4") (pinfunction "C_4") (pintype "passive"))
      (node (ref "LED29") (pin "4") (pinfunction "C_4") (pintype "passive"))
      (node (ref "LED30") (pin "4") (pinfunction "C_4") (pintype "passive"))
      (node (ref "LED31") (pin "4") (pinfunction "C_4") (pintype "passive"))
      (node (ref "LED32") (pin "4") (pinfunction "C_4") (pintype "passive"))
    )
    (net (code "81") (name "Net-(IC4-SEGD)") (class "Default")
      (node (ref "IC4") (pin "23") (pinfunction "SEGD_23") (pintype "output"))
      (node (ref "LED25") (pin "2") (pinfunction "D_2") (pintype "passive"))
      (node (ref "LED26") (pin "2") (pinfunction "D_2") (pintype "passive"))
      (node (ref "LED27") (pin "2") (pinfunction "D_2") (pintype "passive"))
      (node (ref "LED28") (pin "2") (pinfunction "D_2") (pintype "passive"))
      (node (ref "LED29") (pin "2") (pinfunction "D_2") (pintype "passive"))
      (node (ref "LED30") (pin "2") (pinfunction "D_2") (pintype "passive"))
      (node (ref "LED31") (pin "2") (pinfunction "D_2") (pintype "passive"))
      (node (ref "LED32") (pin "2") (pinfunction "D_2") (pintype "passive"))
    )
    (net (code "82") (name "Net-(IC4-SEGDP)") (class "Default")
      (node (ref "IC4") (pin "22") (pinfunction "SEGDP_22") (pintype "output"))
      (node (ref "LED25") (pin "5") (pinfunction "DP_5") (pintype "passive"))
      (node (ref "LED26") (pin "5") (pinfunction "DP_5") (pintype "passive"))
      (node (ref "LED27") (pin "5") (pinfunction "DP_5") (pintype "passive"))
      (node (ref "LED28") (pin "5") (pinfunction "DP_5") (pintype "passive"))
      (node (ref "LED29") (pin "5") (pinfunction "DP_5") (pintype "passive"))
      (node (ref "LED30") (pin "5") (pinfunction "DP_5") (pintype "passive"))
      (node (ref "LED31") (pin "5") (pinfunction "DP_5") (pintype "passive"))
      (node (ref "LED32") (pin "5") (pinfunction "DP_5") (pintype "passive"))
    )
    (net (code "83") (name "Net-(IC4-SEGE)") (class "Default")
      (node (ref "IC4") (pin "21") (pinfunction "SEGE_21") (pintype "output"))
      (node (ref "LED25") (pin "1") (pinfunction "E_1") (pintype "passive"))
      (node (ref "LED26") (pin "1") (pinfunction "E_1") (pintype "passive"))
      (node (ref "LED27") (pin "1") (pinfunction "E_1") (pintype "passive"))
      (node (ref "LED28") (pin "1") (pinfunction "E_1") (pintype "passive"))
      (node (ref "LED29") (pin "1") (pinfunction "E_1") (pintype "passive"))
      (node (ref "LED30") (pin "1") (pinfunction "E_1") (pintype "passive"))
      (node (ref "LED31") (pin "1") (pinfunction "E_1") (pintype "passive"))
      (node (ref "LED32") (pin "1") (pinfunction "E_1") (pintype "passive"))
    )
    (net (code "84") (name "Net-(IC4-SEGF)") (class "Default")
      (node (ref "IC4") (pin "15") (pinfunction "SEGF_15") (pintype "output"))
      (node (ref "LED25") (pin "9") (pinfunction "F_9") (pintype "passive"))
      (node (ref "LED26") (pin "9") (pinfunction "F_9") (pintype "passive"))
      (node (ref "LED27") (pin "9") (pinfunction "F_9") (pintype "passive"))
      (node (ref "LED28") (pin "9") (pinfunction "F_9") (pintype "passive"))
      (node (ref "LED29") (pin "9") (pinfunction "F_9") (pintype "passive"))
      (node (ref "LED30") (pin "9") (pinfunction "F_9") (pintype "passive"))
      (node (ref "LED31") (pin "9") (pinfunction "F_9") (pintype "passive"))
      (node (ref "LED32") (pin "9") (pinfunction "F_9") (pintype "passive"))
    )
    (net (code "85") (name "Net-(IC4-SEGG)") (class "Default")
      (node (ref "IC4") (pin "17") (pinfunction "SEGG_17") (pintype "output"))
      (node (ref "LED25") (pin "10") (pinfunction "G_10") (pintype "passive"))
      (node (ref "LED26") (pin "10") (pinfunction "G_10") (pintype "passive"))
      (node (ref "LED27") (pin "10") (pinfunction "G_10") (pintype "passive"))
      (node (ref "LED28") (pin "10") (pinfunction "G_10") (pintype "passive"))
      (node (ref "LED29") (pin "10") (pinfunction "G_10") (pintype "passive"))
      (node (ref "LED30") (pin "10") (pinfunction "G_10") (pintype "passive"))
      (node (ref "LED31") (pin "10") (pinfunction "G_10") (pintype "passive"))
      (node (ref "LED32") (pin "10") (pinfunction "G_10") (pintype "passive"))
    )
    (net (code "86") (name "Net-(IC5-CLK)") (class "Default")
      (node (ref "IC5") (pin "13") (pinfunction "CLK_13") (pintype "input"))
      (node (ref "R22") (pin "1") (pinfunction "1_1") (pintype "passive"))
    )
    (net (code "87") (name "Net-(IC5-DIG0)") (class "Default")
      (node (ref "IC5") (pin "2") (pinfunction "DIG0_2") (pintype "output"))
      (node (ref "LED33") (pin "3") (pinfunction "COM_3") (pintype "passive"))
      (node (ref "LED33") (pin "8") (pinfunction "COM_8") (pintype "passive"))
    )
    (net (code "88") (name "Net-(IC5-DIG1)") (class "Default")
      (node (ref "IC5") (pin "11") (pinfunction "DIG1_11") (pintype "output"))
      (node (ref "LED34") (pin "3") (pinfunction "COM_3") (pintype "passive"))
      (node (ref "LED34") (pin "8") (pinfunction "COM_8") (pintype "passive"))
    )
    (net (code "89") (name "Net-(IC5-DIG2)") (class "Default")
      (node (ref "IC5") (pin "6") (pinfunction "DIG2_6") (pintype "output"))
      (node (ref "LED35") (pin "3") (pinfunction "COM_3") (pintype "passive"))
      (node (ref "LED35") (pin "8") (pinfunction "COM_8") (pintype "passive"))
    )
    (net (code "90") (name "Net-(IC5-DIG3)") (class "Default")
      (node (ref "IC5") (pin "7") (pinfunction "DIG3_7") (pintype "output"))
      (node (ref "LED36") (pin "3") (pinfunction "COM_3") (pintype "passive"))
      (node (ref "LED36") (pin "8") (pinfunction "COM_8") (pintype "passive"))
    )
    (net (code "91") (name "Net-(IC5-DIG4)") (class "Default")
      (node (ref "IC5") (pin "3") (pinfunction "DIG4_3") (pintype "output"))
      (node (ref "LED37") (pin "3") (pinfunction "COM_3") (pintype "passive"))
      (node (ref "LED37") (pin "8") (pinfunction "COM_8") (pintype "passive"))
    )
    (net (code "92") (name "Net-(IC5-DIG5)") (class "Default")
      (node (ref "IC5") (pin "10") (pinfunction "DIG5_10") (pintype "output"))
      (node (ref "LED38") (pin "3") (pinfunction "COM_3") (pintype "passive"))
      (node (ref "LED38") (pin "8") (pinfunction "COM_8") (pintype "passive"))
    )
    (net (code "93") (name "Net-(IC5-DIG6)") (class "Default")
      (node (ref "IC5") (pin "5") (pinfunction "DIG6_5") (pintype "output"))
      (node (ref "LED39") (pin "3") (pinfunction "COM_3") (pintype "passive"))
      (node (ref "LED39") (pin "8") (pinfunction "COM_8") (pintype "passive"))
    )
    (net (code "94") (name "Net-(IC5-DIG7)") (class "Default")
      (node (ref "IC5") (pin "8") (pinfunction "DIG7_8") (pintype "output"))
      (node (ref "LED40") (pin "3") (pinfunction "COM_3") (pintype "passive"))
      (node (ref "LED40") (pin "8") (pinfunction "COM_8") (pintype "passive"))
    )
    (net (code "95") (name "Net-(IC5-DOUT)") (class "Default")
      (node (ref "IC5") (pin "24") (pinfunction "DOUT_24") (pintype "output"))
      (node (ref "IC6") (pin "1") (pinfunction "DIN_1") (pintype "input"))
    )
    (net (code "96") (name "Net-(IC5-ISET)") (class "Default")
      (node (ref "IC5") (pin "18") (pinfunction "ISET_18") (pintype "input"))
      (node (ref "R6") (pin "2") (pinfunction "2_2") (pintype "passive"))
    )
    (net (code "97") (name "Net-(IC5-LOAD)") (class "Default")
      (node (ref "IC5") (pin "12") (pinfunction "LOAD_12") (pintype "input"))
      (node (ref "R23") (pin "1") (pinfunction "1_1") (pintype "passive"))
    )
    (net (code "98") (name "Net-(IC5-SEGA)") (class "Default")
      (node (ref "IC5") (pin "14") (pinfunction "SEGA_14") (pintype "output"))
      (node (ref "LED33") (pin "7") (pinfunction "A_7") (pintype "passive"))
      (node (ref "LED34") (pin "7") (pinfunction "A_7") (pintype "passive"))
      (node (ref "LED35") (pin "7") (pinfunction "A_7") (pintype "passive"))
      (node (ref "LED36") (pin "7") (pinfunction "A_7") (pintype "passive"))
      (node (ref "LED37") (pin "7") (pinfunction "A_7") (pintype "passive"))
      (node (ref "LED38") (pin "7") (pinfunction "A_7") (pintype "passive"))
      (node (ref "LED39") (pin "7") (pinfunction "A_7") (pintype "passive"))
      (node (ref "LED40") (pin "7") (pinfunction "A_7") (pintype "passive"))
    )
    (net (code "99") (name "Net-(IC5-SEGB)") (class "Default")
      (node (ref "IC5") (pin "16") (pinfunction "SEGB_16") (pintype "output"))
      (node (ref "LED33") (pin "6") (pinfunction "B_6") (pintype "passive"))
      (node (ref "LED34") (pin "6") (pinfunction "B_6") (pintype "passive"))
      (node (ref "LED35") (pin "6") (pinfunction "B_6") (pintype "passive"))
      (node (ref "LED36") (pin "6") (pinfunction "B_6") (pintype "passive"))
      (node (ref "LED37") (pin "6") (pinfunction "B_6") (pintype "passive"))
      (node (ref "LED38") (pin "6") (pinfunction "B_6") (pintype "passive"))
      (node (ref "LED39") (pin "6") (pinfunction "B_6") (pintype "passive"))
      (node (ref "LED40") (pin "6") (pinfunction "B_6") (pintype "passive"))
    )
    (net (code "100") (name "Net-(IC5-SEGC)") (class "Default")
      (node (ref "IC5") (pin "20") (pinfunction "SEGC_20") (pintype "output"))
      (node (ref "LED33") (pin "4") (pinfunction "C_4") (pintype "passive"))
      (node (ref "LED34") (pin "4") (pinfunction "C_4") (pintype "passive"))
      (node (ref "LED35") (pin "4") (pinfunction "C_4") (pintype "passive"))
      (node (ref "LED36") (pin "4") (pinfunction "C_4") (pintype "passive"))
      (node (ref "LED37") (pin "4") (pinfunction "C_4") (pintype "passive"))
      (node (ref "LED38") (pin "4") (pinfunction "C_4") (pintype "passive"))
      (node (ref "LED39") (pin "4") (pinfunction "C_4") (pintype "passive"))
      (node (ref "LED40") (pin "4") (pinfunction "C_4") (pintype "passive"))
    )
    (net (code "101") (name "Net-(IC5-SEGD)") (class "Default")
      (node (ref "IC5") (pin "23") (pinfunction "SEGD_23") (pintype "output"))
      (node (ref "LED33") (pin "2") (pinfunction "D_2") (pintype "passive"))
      (node (ref "LED34") (pin "2") (pinfunction "D_2") (pintype "passive"))
      (node (ref "LED35") (pin "2") (pinfunction "D_2") (pintype "passive"))
      (node (ref "LED36") (pin "2") (pinfunction "D_2") (pintype "passive"))
      (node (ref "LED37") (pin "2") (pinfunction "D_2") (pintype "passive"))
      (node (ref "LED38") (pin "2") (pinfunction "D_2") (pintype "passive"))
      (node (ref "LED39") (pin "2") (pinfunction "D_2") (pintype "passive"))
      (node (ref "LED40") (pin "2") (pinfunction "D_2") (pintype "passive"))
    )
    (net (code "102") (name "Net-(IC5-SEGDP)") (class "Default")
      (node (ref "IC5") (pin "22") (pinfunction "SEGDP_22") (pintype "output"))
      (node (ref "LED33") (pin "5") (pinfunction "DP_5") (pintype "passive"))
      (node (ref "LED34") (pin "5") (pinfunction "DP_5") (pintype "passive"))
      (node (ref "LED35") (pin "5") (pinfunction "DP_5") (pintype "passive"))
      (node (ref "LED36") (pin "5") (pinfunction "DP_5") (pintype "passive"))
      (node (ref "LED37") (pin "5") (pinfunction "DP_5") (pintype "passive"))
      (node (ref "LED38") (pin "5") (pinfunction "DP_5") (pintype "passive"))
      (node (ref "LED39") (pin "5") (pinfunction "DP_5") (pintype "passive"))
      (node (ref "LED40") (pin "5") (pinfunction "DP_5") (pintype "passive"))
    )
    (net (code "103") (name "Net-(IC5-SEGE)") (class "Default")
      (node (ref "IC5") (pin "21") (pinfunction "SEGE_21") (pintype "output"))
      (node (ref "LED33") (pin "1") (pinfunction "E_1") (pintype "passive"))
      (node (ref "LED34") (pin "1") (pinfunction "E_1") (pintype "passive"))
      (node (ref "LED35") (pin "1") (pinfunction "E_1") (pintype "passive"))
      (node (ref "LED36") (pin "1") (pinfunction "E_1") (pintype "passive"))
      (node (ref "LED37") (pin "1") (pinfunction "E_1") (pintype "passive"))
      (node (ref "LED38") (pin "1") (pinfunction "E_1") (pintype "passive"))
      (node (ref "LED39") (pin "1") (pinfunction "E_1") (pintype "passive"))
      (node (ref "LED40") (pin "1") (pinfunction "E_1") (pintype "passive"))
    )
    (net (code "104") (name "Net-(IC5-SEGF)") (class "Default")
      (node (ref "IC5") (pin "15") (pinfunction "SEGF_15") (pintype "output"))
      (node (ref "LED33") (pin "9") (pinfunction "F_9") (pintype "passive"))
      (node (ref "LED34") (pin "9") (pinfunction "F_9") (pintype "passive"))
      (node (ref "LED35") (pin "9") (pinfunction "F_9") (pintype "passive"))
      (node (ref "LED36") (pin "9") (pinfunction "F_9") (pintype "passive"))
      (node (ref "LED37") (pin "9") (pinfunction "F_9") (pintype "passive"))
      (node (ref "LED38") (pin "9") (pinfunction "F_9") (pintype "passive"))
      (node (ref "LED39") (pin "9") (pinfunction "F_9") (pintype "passive"))
      (node (ref "LED40") (pin "9") (pinfunction "F_9") (pintype "passive"))
    )
    (net (code "105") (name "Net-(IC5-SEGG)") (class "Default")
      (node (ref "IC5") (pin "17") (pinfunction "SEGG_17") (pintype "output"))
      (node (ref "LED33") (pin "10") (pinfunction "G_10") (pintype "passive"))
      (node (ref "LED34") (pin "10") (pinfunction "G_10") (pintype "passive"))
      (node (ref "LED35") (pin "10") (pinfunction "G_10") (pintype "passive"))
      (node (ref "LED36") (pin "10") (pinfunction "G_10") (pintype "passive"))
      (node (ref "LED37") (pin "10") (pinfunction "G_10") (pintype "passive"))
      (node (ref "LED38") (pin "10") (pinfunction "G_10") (pintype "passive"))
      (node (ref "LED39") (pin "10") (pinfunction "G_10") (pintype "passive"))
      (node (ref "LED40") (pin "10") (pinfunction "G_10") (pintype "passive"))
    )
    (net (code "106") (name "Net-(IC6-CLK)") (class "Default")
      (node (ref "IC6") (pin "13") (pinfunction "CLK_13") (pintype "input"))
      (node (ref "R24") (pin "1") (pinfunction "1_1") (pintype "passive"))
    )
    (net (code "107") (name "Net-(IC6-DIG0)") (class "Default")
      (node (ref "IC6") (pin "2") (pinfunction "DIG0_2") (pintype "output"))
      (node (ref "LED41") (pin "3") (pinfunction "COM_3") (pintype "passive"))
      (node (ref "LED41") (pin "8") (pinfunction "COM_8") (pintype "passive"))
    )
    (net (code "108") (name "Net-(IC6-DIG1)") (class "Default")
      (node (ref "IC6") (pin "11") (pinfunction "DIG1_11") (pintype "output"))
      (node (ref "LED42") (pin "3") (pinfunction "COM_3") (pintype "passive"))
      (node (ref "LED42") (pin "8") (pinfunction "COM_8") (pintype "passive"))
    )
    (net (code "109") (name "Net-(IC6-DIG2)") (class "Default")
      (node (ref "IC6") (pin "6") (pinfunction "DIG2_6") (pintype "output"))
      (node (ref "LED43") (pin "3") (pinfunction "COM_3") (pintype "passive"))
      (node (ref "LED43") (pin "8") (pinfunction "COM_8") (pintype "passive"))
    )
    (net (code "110") (name "Net-(IC6-DIG3)") (class "Default")
      (node (ref "IC6") (pin "7") (pinfunction "DIG3_7") (pintype "output"))
      (node (ref "LED44") (pin "3") (pinfunction "COM_3") (pintype "passive"))
      (node (ref "LED44") (pin "8") (pinfunction "COM_8") (pintype "passive"))
    )
    (net (code "111") (name "Net-(IC6-DIG4)") (class "Default")
      (node (ref "IC6") (pin "3") (pinfunction "DIG4_3") (pintype "output"))
      (node (ref "LED45") (pin "3") (pinfunction "COM_3") (pintype "passive"))
      (node (ref "LED45") (pin "8") (pinfunction "COM_8") (pintype "passive"))
    )
    (net (code "112") (name "Net-(IC6-DIG5)") (class "Default")
      (node (ref "IC6") (pin "10") (pinfunction "DIG5_10") (pintype "output"))
      (node (ref "LED46") (pin "3") (pinfunction "COM_3") (pintype "passive"))
      (node (ref "LED46") (pin "8") (pinfunction "COM_8") (pintype "passive"))
    )
    (net (code "113") (name "Net-(IC6-DIG6)") (class "Default")
      (node (ref "IC6") (pin "5") (pinfunction "DIG6_5") (pintype "output"))
      (node (ref "LED47") (pin "3") (pinfunction "COM_3") (pintype "passive"))
      (node (ref "LED47") (pin "8") (pinfunction "COM_8") (pintype "passive"))
    )
    (net (code "114") (name "Net-(IC6-DIG7)") (class "Default")
      (node (ref "IC6") (pin "8") (pinfunction "DIG7_8") (pintype "output"))
      (node (ref "LED48") (pin "3") (pinfunction "COM_3") (pintype "passive"))
      (node (ref "LED48") (pin "8") (pinfunction "COM_8") (pintype "passive"))
    )
    (net (code "115") (name "Net-(IC6-DOUT)") (class "Default")
      (node (ref "IC6") (pin "24") (pinfunction "DOUT_24") (pintype "output"))
      (node (ref "IC7") (pin "1") (pinfunction "DIN_1") (pintype "input"))
    )
    (net (code "116") (name "Net-(IC6-ISET)") (class "Default")
      (node (ref "IC6") (pin "18") (pinfunction "ISET_18") (pintype "input"))
      (node (ref "R7") (pin "2") (pinfunction "2_2") (pintype "passive"))
    )
    (net (code "117") (name "Net-(IC6-LOAD)") (class "Default")
      (node (ref "IC6") (pin "12") (pinfunction "LOAD_12") (pintype "input"))
      (node (ref "R25") (pin "1") (pinfunction "1_1") (pintype "passive"))
    )
    (net (code "118") (name "Net-(IC6-SEGA)") (class "Default")
      (node (ref "IC6") (pin "14") (pinfunction "SEGA_14") (pintype "output"))
      (node (ref "LED41") (pin "7") (pinfunction "A_7") (pintype "passive"))
      (node (ref "LED42") (pin "7") (pinfunction "A_7") (pintype "passive"))
      (node (ref "LED43") (pin "7") (pinfunction "A_7") (pintype "passive"))
      (node (ref "LED44") (pin "7") (pinfunction "A_7") (pintype "passive"))
      (node (ref "LED45") (pin "7") (pinfunction "A_7") (pintype "passive"))
      (node (ref "LED46") (pin "7") (pinfunction "A_7") (pintype "passive"))
      (node (ref "LED47") (pin "7") (pinfunction "A_7") (pintype "passive"))
      (node (ref "LED48") (pin "7") (pinfunction "A_7") (pintype "passive"))
    )
    (net (code "119") (name "Net-(IC6-SEGB)") (class "Default")
      (node (ref "IC6") (pin "16") (pinfunction "SEGB_16") (pintype "output"))
      (node (ref "LED41") (pin "6") (pinfunction "B_6") (pintype "passive"))
      (node (ref "LED42") (pin "6") (pinfunction "B_6") (pintype "passive"))
      (node (ref "LED43") (pin "6") (pinfunction "B_6") (pintype "passive"))
      (node (ref "LED44") (pin "6") (pinfunction "B_6") (pintype "passive"))
      (node (ref "LED45") (pin "6") (pinfunction "B_6") (pintype "passive"))
      (node (ref "LED46") (pin "6") (pinfunction "B_6") (pintype "passive"))
      (node (ref "LED47") (pin "6") (pinfunction "B_6") (pintype "passive"))
      (node (ref "LED48") (pin "6") (pinfunction "B_6") (pintype "passive"))
    )
    (net (code "120") (name "Net-(IC6-SEGC)") (class "Default")
      (node (ref "IC6") (pin "20") (pinfunction "SEGC_20") (pintype "output"))
      (node (ref "LED41") (pin "4") (pinfunction "C_4") (pintype "passive"))
      (node (ref "LED42") (pin "4") (pinfunction "C_4") (pintype "passive"))
      (node (ref "LED43") (pin "4") (pinfunction "C_4") (pintype "passive"))
      (node (ref "LED44") (pin "4") (pinfunction "C_4") (pintype "passive"))
      (node (ref "LED45") (pin "4") (pinfunction "C_4") (pintype "passive"))
      (node (ref "LED46") (pin "4") (pinfunction "C_4") (pintype "passive"))
      (node (ref "LED47") (pin "4") (pinfunction "C_4") (pintype "passive"))
      (node (ref "LED48") (pin "4") (pinfunction "C_4") (pintype "passive"))
    )
    (net (code "121") (name "Net-(IC6-SEGD)") (class "Default")
      (node (ref "IC6") (pin "23") (pinfunction "SEGD_23") (pintype "output"))
      (node (ref "LED41") (pin "2") (pinfunction "D_2") (pintype "passive"))
      (node (ref "LED42") (pin "2") (pinfunction "D_2") (pintype "passive"))
      (node (ref "LED43") (pin "2") (pinfunction "D_2") (pintype "passive"))
      (node (ref "LED44") (pin "2") (pinfunction "D_2") (pintype "passive"))
      (node (ref "LED45") (pin "2") (pinfunction "D_2") (pintype "passive"))
      (node (ref "LED46") (pin "2") (pinfunction "D_2") (pintype "passive"))
      (node (ref "LED47") (pin "2") (pinfunction "D_2") (pintype "passive"))
      (node (ref "LED48") (pin "2") (pinfunction "D_2") (pintype "passive"))
    )
    (net (code "122") (name "Net-(IC6-SEGDP)") (class "Default")
      (node (ref "IC6") (pin "22") (pinfunction "SEGDP_22") (pintype "output"))
      (node (ref "LED41") (pin "5") (pinfunction "DP_5") (pintype "passive"))
      (node (ref "LED42") (pin "5") (pinfunction "DP_5") (pintype "passive"))
      (node (ref "LED43") (pin "5") (pinfunction "DP_5") (pintype "passive"))
      (node (ref "LED44") (pin "5") (pinfunction "DP_5") (pintype "passive"))
      (node (ref "LED45") (pin "5") (pinfunction "DP_5") (pintype "passive"))
      (node (ref "LED46") (pin "5") (pinfunction "DP_5") (pintype "passive"))
      (node (ref "LED47") (pin "5") (pinfunction "DP_5") (pintype "passive"))
      (node (ref "LED48") (pin "5") (pinfunction "DP_5") (pintype "passive"))
    )
    (net (code "123") (name "Net-(IC6-SEGE)") (class "Default")
      (node (ref "IC6") (pin "21") (pinfunction "SEGE_21") (pintype "output"))
      (node (ref "LED41") (pin "1") (pinfunction "E_1") (pintype "passive"))
      (node (ref "LED42") (pin "1") (pinfunction "E_1") (pintype "passive"))
      (node (ref "LED43") (pin "1") (pinfunction "E_1") (pintype "passive"))
      (node (ref "LED44") (pin "1") (pinfunction "E_1") (pintype "passive"))
      (node (ref "LED45") (pin "1") (pinfunction "E_1") (pintype "passive"))
      (node (ref "LED46") (pin "1") (pinfunction "E_1") (pintype "passive"))
      (node (ref "LED47") (pin "1") (pinfunction "E_1") (pintype "passive"))
      (node (ref "LED48") (pin "1") (pinfunction "E_1") (pintype "passive"))
    )
    (net (code "124") (name "Net-(IC6-SEGF)") (class "Default")
      (node (ref "IC6") (pin "15") (pinfunction "SEGF_15") (pintype "output"))
      (node (ref "LED41") (pin "9") (pinfunction "F_9") (pintype "passive"))
      (node (ref "LED42") (pin "9") (pinfunction "F_9") (pintype "passive"))
      (node (ref "LED43") (pin "9") (pinfunction "F_9") (pintype "passive"))
      (node (ref "LED44") (pin "9") (pinfunction "F_9") (pintype "passive"))
      (node (ref "LED45") (pin "9") (pinfunction "F_9") (pintype "passive"))
      (node (ref "LED46") (pin "9") (pinfunction "F_9") (pintype "passive"))
      (node (ref "LED47") (pin "9") (pinfunction "F_9") (pintype "passive"))
      (node (ref "LED48") (pin "9") (pinfunction "F_9") (pintype "passive"))
    )
    (net (code "125") (name "Net-(IC6-SEGG)") (class "Default")
      (node (ref "IC6") (pin "17") (pinfunction "SEGG_17") (pintype "output"))
      (node (ref "LED41") (pin "10") (pinfunction "G_10") (pintype "passive"))
      (node (ref "LED42") (pin "10") (pinfunction "G_10") (pintype "passive"))
      (node (ref "LED43") (pin "10") (pinfunction "G_10") (pintype "passive"))
      (node (ref "LED44") (pin "10") (pinfunction "G_10") (pintype "passive"))
      (node (ref "LED45") (pin "10") (pinfunction "G_10") (pintype "passive"))
      (node (ref "LED46") (pin "10") (pinfunction "G_10") (pintype "passive"))
      (node (ref "LED47") (pin "10") (pinfunction "G_10") (pintype "passive"))
      (node (ref "LED48") (pin "10") (pinfunction "G_10") (pintype "passive"))
    )
    (net (code "126") (name "Net-(IC7-CLK)") (class "Default")
      (node (ref "IC7") (pin "13") (pinfunction "CLK_13") (pintype "input"))
      (node (ref "R26") (pin "1") (pinfunction "1_1") (pintype "passive"))
    )
    (net (code "127") (name "Net-(IC7-DIG0)") (class "Default")
      (node (ref "IC7") (pin "2") (pinfunction "DIG0_2") (pintype "output"))
      (node (ref "LED49") (pin "3") (pinfunction "COM_3") (pintype "passive"))
      (node (ref "LED49") (pin "8") (pinfunction "COM_8") (pintype "passive"))
    )
    (net (code "128") (name "Net-(IC7-DIG1)") (class "Default")
      (node (ref "IC7") (pin "11") (pinfunction "DIG1_11") (pintype "output"))
      (node (ref "LED50") (pin "3") (pinfunction "COM_3") (pintype "passive"))
      (node (ref "LED50") (pin "8") (pinfunction "COM_8") (pintype "passive"))
    )
    (net (code "129") (name "Net-(IC7-DIG2)") (class "Default")
      (node (ref "IC7") (pin "6") (pinfunction "DIG2_6") (pintype "output"))
      (node (ref "LED51") (pin "3") (pinfunction "COM_3") (pintype "passive"))
      (node (ref "LED51") (pin "8") (pinfunction "COM_8") (pintype "passive"))
    )
    (net (code "130") (name "Net-(IC7-DIG3)") (class "Default")
      (node (ref "IC7") (pin "7") (pinfunction "DIG3_7") (pintype "output"))
      (node (ref "LED52") (pin "3") (pinfunction "COM_3") (pintype "passive"))
      (node (ref "LED52") (pin "8") (pinfunction "COM_8") (pintype "passive"))
    )
    (net (code "131") (name "Net-(IC7-DIG4)") (class "Default")
      (node (ref "IC7") (pin "3") (pinfunction "DIG4_3") (pintype "output"))
      (node (ref "LED53") (pin "3") (pinfunction "COM_3") (pintype "passive"))
      (node (ref "LED53") (pin "8") (pinfunction "COM_8") (pintype "passive"))
    )
    (net (code "132") (name "Net-(IC7-DIG5)") (class "Default")
      (node (ref "IC7") (pin "10") (pinfunction "DIG5_10") (pintype "output"))
      (node (ref "LED54") (pin "3") (pinfunction "COM_3") (pintype "passive"))
      (node (ref "LED54") (pin "8") (pinfunction "COM_8") (pintype "passive"))
    )
    (net (code "133") (name "Net-(IC7-DIG6)") (class "Default")
      (node (ref "IC7") (pin "5") (pinfunction "DIG6_5") (pintype "output"))
      (node (ref "LED55") (pin "3") (pinfunction "COM_3") (pintype "passive"))
      (node (ref "LED55") (pin "8") (pinfunction "COM_8") (pintype "passive"))
    )
    (net (code "134") (name "Net-(IC7-DIG7)") (class "Default")
      (node (ref "IC7") (pin "8") (pinfunction "DIG7_8") (pintype "output"))
      (node (ref "LED56") (pin "3") (pinfunction "COM_3") (pintype "passive"))
      (node (ref "LED56") (pin "8") (pinfunction "COM_8") (pintype "passive"))
    )
    (net (code "135") (name "Net-(IC7-DOUT)") (class "Default")
      (node (ref "IC7") (pin "24") (pinfunction "DOUT_24") (pintype "output"))
      (node (ref "IC8") (pin "1") (pinfunction "DIN_1") (pintype "input"))
    )
    (net (code "136") (name "Net-(IC7-ISET)") (class "Default")
      (node (ref "IC7") (pin "18") (pinfunction "ISET_18") (pintype "input"))
      (node (ref "R8") (pin "2") (pinfunction "2_2") (pintype "passive"))
    )
    (net (code "137") (name "Net-(IC7-LOAD)") (class "Default")
      (node (ref "IC7") (pin "12") (pinfunction "LOAD_12") (pintype "input"))
      (node (ref "R27") (pin "1") (pinfunction "1_1") (pintype "passive"))
    )
    (net (code "138") (name "Net-(IC7-SEGA)") (class "Default")
      (node (ref "IC7") (pin "14") (pinfunction "SEGA_14") (pintype "output"))
      (node (ref "LED49") (pin "7") (pinfunction "A_7") (pintype "passive"))
      (node (ref "LED50") (pin "7") (pinfunction "A_7") (pintype "passive"))
      (node (ref "LED51") (pin "7") (pinfunction "A_7") (pintype "passive"))
      (node (ref "LED52") (pin "7") (pinfunction "A_7") (pintype "passive"))
      (node (ref "LED53") (pin "7") (pinfunction "A_7") (pintype "passive"))
      (node (ref "LED54") (pin "7") (pinfunction "A_7") (pintype "passive"))
      (node (ref "LED55") (pin "7") (pinfunction "A_7") (pintype "passive"))
      (node (ref "LED56") (pin "7") (pinfunction "A_7") (pintype "passive"))
    )
    (net (code "139") (name "Net-(IC7-SEGB)") (class "Default")
      (node (ref "IC7") (pin "16") (pinfunction "SEGB_16") (pintype "output"))
      (node (ref "LED49") (pin "6") (pinfunction "B_6") (pintype "passive"))
      (node (ref "LED50") (pin "6") (pinfunction "B_6") (pintype "passive"))
      (node (ref "LED51") (pin "6") (pinfunction "B_6") (pintype "passive"))
      (node (ref "LED52") (pin "6") (pinfunction "B_6") (pintype "passive"))
      (node (ref "LED53") (pin "6") (pinfunction "B_6") (pintype "passive"))
      (node (ref "LED54") (pin "6") (pinfunction "B_6") (pintype "passive"))
      (node (ref "LED55") (pin "6") (pinfunction "B_6") (pintype "passive"))
      (node (ref "LED56") (pin "6") (pinfunction "B_6") (pintype "passive"))
    )
    (net (code "140") (name "Net-(IC7-SEGC)") (class "Default")
      (node (ref "IC7") (pin "20") (pinfunction "SEGC_20") (pintype "output"))
      (node (ref "LED49") (pin "4") (pinfunction "C_4") (pintype "passive"))
      (node (ref "LED50") (pin "4") (pinfunction "C_4") (pintype "passive"))
      (node (ref "LED51") (pin "4") (pinfunction "C_4") (pintype "passive"))
      (node (ref "LED52") (pin "4") (pinfunction "C_4") (pintype "passive"))
      (node (ref "LED53") (pin "4") (pinfunction "C_4") (pintype "passive"))
      (node (ref "LED54") (pin "4") (pinfunction "C_4") (pintype "passive"))
      (node (ref "LED55") (pin "4") (pinfunction "C_4") (pintype "passive"))
      (node (ref "LED56") (pin "4") (pinfunction "C_4") (pintype "passive"))
    )
    (net (code "141") (name "Net-(IC7-SEGD)") (class "Default")
      (node (ref "IC7") (pin "23") (pinfunction "SEGD_23") (pintype "output"))
      (node (ref "LED49") (pin "2") (pinfunction "D_2") (pintype "passive"))
      (node (ref "LED50") (pin "2") (pinfunction "D_2") (pintype "passive"))
      (node (ref "LED51") (pin "2") (pinfunction "D_2") (pintype "passive"))
      (node (ref "LED52") (pin "2") (pinfunction "D_2") (pintype "passive"))
      (node (ref "LED53") (pin "2") (pinfunction "D_2") (pintype "passive"))
      (node (ref "LED54") (pin "2") (pinfunction "D_2") (pintype "passive"))
      (node (ref "LED55") (pin "2") (pinfunction "D_2") (pintype "passive"))
      (node (ref "LED56") (pin "2") (pinfunction "D_2") (pintype "passive"))
    )
    (net (code "142") (name "Net-(IC7-SEGDP)") (class "Default")
      (node (ref "IC7") (pin "22") (pinfunction "SEGDP_22") (pintype "output"))
      (node (ref "LED49") (pin "5") (pinfunction "DP_5") (pintype "passive"))
      (node (ref "LED50") (pin "5") (pinfunction "DP_5") (pintype "passive"))
      (node (ref "LED51") (pin "5") (pinfunction "DP_5") (pintype "passive"))
      (node (ref "LED52") (pin "5") (pinfunction "DP_5") (pintype "passive"))
      (node (ref "LED53") (pin "5") (pinfunction "DP_5") (pintype "passive"))
      (node (ref "LED54") (pin "5") (pinfunction "DP_5") (pintype "passive"))
      (node (ref "LED55") (pin "5") (pinfunction "DP_5") (pintype "passive"))
      (node (ref "LED56") (pin "5") (pinfunction "DP_5") (pintype "passive"))
    )
    (net (code "143") (name "Net-(IC7-SEGE)") (class "Default")
      (node (ref "IC7") (pin "21") (pinfunction "SEGE_21") (pintype "output"))
      (node (ref "LED49") (pin "1") (pinfunction "E_1") (pintype "passive"))
      (node (ref "LED50") (pin "1") (pinfunction "E_1") (pintype "passive"))
      (node (ref "LED51") (pin "1") (pinfunction "E_1") (pintype "passive"))
      (node (ref "LED52") (pin "1") (pinfunction "E_1") (pintype "passive"))
      (node (ref "LED53") (pin "1") (pinfunction "E_1") (pintype "passive"))
      (node (ref "LED54") (pin "1") (pinfunction "E_1") (pintype "passive"))
      (node (ref "LED55") (pin "1") (pinfunction "E_1") (pintype "passive"))
      (node (ref "LED56") (pin "1") (pinfunction "E_1") (pintype "passive"))
    )
    (net (code "144") (name "Net-(IC7-SEGF)") (class "Default")
      (node (ref "IC7") (pin "15") (pinfunction "SEGF_15") (pintype "output"))
      (node (ref "LED49") (pin "9") (pinfunction "F_9") (pintype "passive"))
      (node (ref "LED50") (pin "9") (pinfunction "F_9") (pintype "passive"))
      (node (ref "LED51") (pin "9") (pinfunction "F_9") (pintype "passive"))
      (node (ref "LED52") (pin "9") (pinfunction "F_9") (pintype "passive"))
      (node (ref "LED53") (pin "9") (pinfunction "F_9") (pintype "passive"))
      (node (ref "LED54") (pin "9") (pinfunction "F_9") (pintype "passive"))
      (node (ref "LED55") (pin "9") (pinfunction "F_9") (pintype "passive"))
      (node (ref "LED56") (pin "9") (pinfunction "F_9") (pintype "passive"))
    )
    (net (code "145") (name "Net-(IC7-SEGG)") (class "Default")
      (node (ref "IC7") (pin "17") (pinfunction "SEGG_17") (pintype "output"))
      (node (ref "LED49") (pin "10") (pinfunction "G_10") (pintype "passive"))
      (node (ref "LED50") (pin "10") (pinfunction "G_10") (pintype "passive"))
      (node (ref "LED51") (pin "10") (pinfunction "G_10") (pintype "passive"))
      (node (ref "LED52") (pin "10") (pinfunction "G_10") (pintype "passive"))
      (node (ref "LED53") (pin "10") (pinfunction "G_10") (pintype "passive"))
      (node (ref "LED54") (pin "10") (pinfunction "G_10") (pintype "passive"))
      (node (ref "LED55") (pin "10") (pinfunction "G_10") (pintype "passive"))
      (node (ref "LED56") (pin "10") (pinfunction "G_10") (pintype "passive"))
    )
    (net (code "146") (name "Net-(IC8-CLK)") (class "Default")
      (node (ref "IC8") (pin "13") (pinfunction "CLK_13") (pintype "input"))
      (node (ref "R28") (pin "1") (pinfunction "1_1") (pintype "passive"))
    )
    (net (code "147") (name "Net-(IC8-DIG0)") (class "Default")
      (node (ref "IC8") (pin "2") (pinfunction "DIG0_2") (pintype "output"))
      (node (ref "LED57") (pin "3") (pinfunction "COM_3") (pintype "passive"))
      (node (ref "LED57") (pin "8") (pinfunction "COM_8") (pintype "passive"))
    )
    (net (code "148") (name "Net-(IC8-DIG1)") (class "Default")
      (node (ref "IC8") (pin "11") (pinfunction "DIG1_11") (pintype "output"))
      (node (ref "LED58") (pin "3") (pinfunction "COM_3") (pintype "passive"))
      (node (ref "LED58") (pin "8") (pinfunction "COM_8") (pintype "passive"))
    )
    (net (code "149") (name "Net-(IC8-DIG2)") (class "Default")
      (node (ref "IC8") (pin "6") (pinfunction "DIG2_6") (pintype "output"))
      (node (ref "LED59") (pin "3") (pinfunction "COM_3") (pintype "passive"))
      (node (ref "LED59") (pin "8") (pinfunction "COM_8") (pintype "passive"))
    )
    (net (code "150") (name "Net-(IC8-DIG3)") (class "Default")
      (node (ref "IC8") (pin "7") (pinfunction "DIG3_7") (pintype "output"))
      (node (ref "LED60") (pin "3") (pinfunction "COM_3") (pintype "passive"))
      (node (ref "LED60") (pin "8") (pinfunction "COM_8") (pintype "passive"))
    )
    (net (code "151") (name "Net-(IC8-DIG4)") (class "Default")
      (node (ref "IC8") (pin "3") (pinfunction "DIG4_3") (pintype "output"))
      (node (ref "LED61") (pin "3") (pinfunction "COM_3") (pintype "passive"))
      (node (ref "LED61") (pin "8") (pinfunction "COM_8") (pintype "passive"))
    )
    (net (code "152") (name "Net-(IC8-DIG5)") (class "Default")
      (node (ref "IC8") (pin "10") (pinfunction "DIG5_10") (pintype "output"))
      (node (ref "LED62") (pin "3") (pinfunction "COM_3") (pintype "passive"))
      (node (ref "LED62") (pin "8") (pinfunction "COM_8") (pintype "passive"))
    )
    (net (code "153") (name "Net-(IC8-DIG6)") (class "Default")
      (node (ref "IC8") (pin "5") (pinfunction "DIG6_5") (pintype "output"))
      (node (ref "LED63") (pin "3") (pinfunction "COM_3") (pintype "passive"))
      (node (ref "LED63") (pin "8") (pinfunction "COM_8") (pintype "passive"))
    )
    (net (code "154") (name "Net-(IC8-DIG7)") (class "Default")
      (node (ref "IC8") (pin "8") (pinfunction "DIG7_8") (pintype "output"))
      (node (ref "LED64") (pin "3") (pinfunction "COM_3") (pintype "passive"))
      (node (ref "LED64") (pin "8") (pinfunction "COM_8") (pintype "passive"))
    )
    (net (code "155") (name "Net-(IC8-DOUT)") (class "Default")
      (node (ref "IC8") (pin "24") (pinfunction "DOUT_24") (pintype "output"))
      (node (ref "IC9") (pin "1") (pinfunction "DIN_1") (pintype "input"))
    )
    (net (code "156") (name "Net-(IC8-ISET)") (class "Default")
      (node (ref "IC8") (pin "18") (pinfunction "ISET_18") (pintype "input"))
      (node (ref "R9") (pin "2") (pinfunction "2_2") (pintype "passive"))
    )
    (net (code "157") (name "Net-(IC8-LOAD)") (class "Default")
      (node (ref "IC8") (pin "12") (pinfunction "LOAD_12") (pintype "input"))
      (node (ref "R29") (pin "1") (pinfunction "1_1") (pintype "passive"))
    )
    (net (code "158") (name "Net-(IC8-SEGA)") (class "Default")
      (node (ref "IC8") (pin "14") (pinfunction "SEGA_14") (pintype "output"))
      (node (ref "LED57") (pin "7") (pinfunction "A_7") (pintype "passive"))
      (node (ref "LED58") (pin "7") (pinfunction "A_7") (pintype "passive"))
      (node (ref "LED59") (pin "7") (pinfunction "A_7") (pintype "passive"))
      (node (ref "LED60") (pin "7") (pinfunction "A_7") (pintype "passive"))
      (node (ref "LED61") (pin "7") (pinfunction "A_7") (pintype "passive"))
      (node (ref "LED62") (pin "7") (pinfunction "A_7") (pintype "passive"))
      (node (ref "LED63") (pin "7") (pinfunction "A_7") (pintype "passive"))
      (node (ref "LED64") (pin "7") (pinfunction "A_7") (pintype "passive"))
    )
    (net (code "159") (name "Net-(IC8-SEGB)") (class "Default")
      (node (ref "IC8") (pin "16") (pinfunction "SEGB_16") (pintype "output"))
      (node (ref "LED57") (pin "6") (pinfunction "B_6") (pintype "passive"))
      (node (ref "LED58") (pin "6") (pinfunction "B_6") (pintype "passive"))
      (node (ref "LED59") (pin "6") (pinfunction "B_6") (pintype "passive"))
      (node (ref "LED60") (pin "6") (pinfunction "B_6") (pintype "passive"))
      (node (ref "LED61") (pin "6") (pinfunction "B_6") (pintype "passive"))
      (node (ref "LED62") (pin "6") (pinfunction "B_6") (pintype "passive"))
      (node (ref "LED63") (pin "6") (pinfunction "B_6") (pintype "passive"))
      (node (ref "LED64") (pin "6") (pinfunction "B_6") (pintype "passive"))
    )
    (net (code "160") (name "Net-(IC8-SEGC)") (class "Default")
      (node (ref "IC8") (pin "20") (pinfunction "SEGC_20") (pintype "output"))
      (node (ref "LED57") (pin "4") (pinfunction "C_4") (pintype "passive"))
      (node (ref "LED58") (pin "4") (pinfunction "C_4") (pintype "passive"))
      (node (ref "LED59") (pin "4") (pinfunction "C_4") (pintype "passive"))
      (node (ref "LED60") (pin "4") (pinfunction "C_4") (pintype "passive"))
      (node (ref "LED61") (pin "4") (pinfunction "C_4") (pintype "passive"))
      (node (ref "LED62") (pin "4") (pinfunction "C_4") (pintype "passive"))
      (node (ref "LED63") (pin "4") (pinfunction "C_4") (pintype "passive"))
      (node (ref "LED64") (pin "4") (pinfunction "C_4") (pintype "passive"))
    )
    (net (code "161") (name "Net-(IC8-SEGD)") (class "Default")
      (node (ref "IC8") (pin "23") (pinfunction "SEGD_23") (pintype "output"))
      (node (ref "LED57") (pin "2") (pinfunction "D_2") (pintype "passive"))
      (node (ref "LED58") (pin "2") (pinfunction "D_2") (pintype "passive"))
      (node (ref "LED59") (pin "2") (pinfunction "D_2") (pintype "passive"))
      (node (ref "LED60") (pin "2") (pinfunction "D_2") (pintype "passive"))
      (node (ref "LED61") (pin "2") (pinfunction "D_2") (pintype "passive"))
      (node (ref "LED62") (pin "2") (pinfunction "D_2") (pintype "passive"))
      (node (ref "LED63") (pin "2") (pinfunction "D_2") (pintype "passive"))
      (node (ref "LED64") (pin "2") (pinfunction "D_2") (pintype "passive"))
    )
    (net (code "162") (name "Net-(IC8-SEGDP)") (class "Default")
      (node (ref "IC8") (pin "22") (pinfunction "SEGDP_22") (pintype "output"))
      (node (ref "LED57") (pin "5") (pinfunction "DP_5") (pintype "passive"))
      (node (ref "LED58") (pin "5") (pinfunction "DP_5") (pintype "passive"))
      (node (ref "LED59") (pin "5") (pinfunction "DP_5") (pintype "passive"))
      (node (ref "LED60") (pin "5") (pinfunction "DP_5") (pintype "passive"))
      (node (ref "LED61") (pin "5") (pinfunction "DP_5") (pintype "passive"))
      (node (ref "LED62") (pin "5") (pinfunction "DP_5") (pintype "passive"))
      (node (ref "LED63") (pin "5") (pinfunction "DP_5") (pintype "passive"))
      (node (ref "LED64") (pin "5") (pinfunction "DP_5") (pintype "passive"))
    )
    (net (code "163") (name "Net-(IC8-SEGE)") (class "Default")
      (node (ref "IC8") (pin "21") (pinfunction "SEGE_21") (pintype "output"))
      (node (ref "LED57") (pin "1") (pinfunction "E_1") (pintype "passive"))
      (node (ref "LED58") (pin "1") (pinfunction "E_1") (pintype "passive"))
      (node (ref "LED59") (pin "1") (pinfunction "E_1") (pintype "passive"))
      (node (ref "LED60") (pin "1") (pinfunction "E_1") (pintype "passive"))
      (node (ref "LED61") (pin "1") (pinfunction "E_1") (pintype "passive"))
      (node (ref "LED62") (pin "1") (pinfunction "E_1") (pintype "passive"))
      (node (ref "LED63") (pin "1") (pinfunction "E_1") (pintype "passive"))
      (node (ref "LED64") (pin "1") (pinfunction "E_1") (pintype "passive"))
    )
    (net (code "164") (name "Net-(IC8-SEGF)") (class "Default")
      (node (ref "IC8") (pin "15") (pinfunction "SEGF_15") (pintype "output"))
      (node (ref "LED57") (pin "9") (pinfunction "F_9") (pintype "passive"))
      (node (ref "LED58") (pin "9") (pinfunction "F_9") (pintype "passive"))
      (node (ref "LED59") (pin "9") (pinfunction "F_9") (pintype "passive"))
      (node (ref "LED60") (pin "9") (pinfunction "F_9") (pintype "passive"))
      (node (ref "LED61") (pin "9") (pinfunction "F_9") (pintype "passive"))
      (node (ref "LED62") (pin "9") (pinfunction "F_9") (pintype "passive"))
      (node (ref "LED63") (pin "9") (pinfunction "F_9") (pintype "passive"))
      (node (ref "LED64") (pin "9") (pinfunction "F_9") (pintype "passive"))
    )
    (net (code "165") (name "Net-(IC8-SEGG)") (class "Default")
      (node (ref "IC8") (pin "17") (pinfunction "SEGG_17") (pintype "output"))
      (node (ref "LED57") (pin "10") (pinfunction "G_10") (pintype "passive"))
      (node (ref "LED58") (pin "10") (pinfunction "G_10") (pintype "passive"))
      (node (ref "LED59") (pin "10") (pinfunction "G_10") (pintype "passive"))
      (node (ref "LED60") (pin "10") (pinfunction "G_10") (pintype "passive"))
      (node (ref "LED61") (pin "10") (pinfunction "G_10") (pintype "passive"))
      (node (ref "LED62") (pin "10") (pinfunction "G_10") (pintype "passive"))
      (node (ref "LED63") (pin "10") (pinfunction "G_10") (pintype "passive"))
      (node (ref "LED64") (pin "10") (pinfunction "G_10") (pintype "passive"))
    )
    (net (code "166") (name "Net-(IC9-CLK)") (class "Default")
      (node (ref "IC9") (pin "13") (pinfunction "CLK_13") (pintype "input"))
      (node (ref "R30") (pin "1") (pinfunction "1_1") (pintype "passive"))
    )
    (net (code "167") (name "Net-(IC9-DIG0)") (class "Default")
      (node (ref "IC9") (pin "2") (pinfunction "DIG0_2") (pintype "output"))
      (node (ref "LED65") (pin "3") (pinfunction "COM_3") (pintype "passive"))
      (node (ref "LED65") (pin "8") (pinfunction "COM_8") (pintype "passive"))
    )
    (net (code "168") (name "Net-(IC9-DIG1)") (class "Default")
      (node (ref "IC9") (pin "11") (pinfunction "DIG1_11") (pintype "output"))
      (node (ref "LED66") (pin "3") (pinfunction "COM_3") (pintype "passive"))
      (node (ref "LED66") (pin "8") (pinfunction "COM_8") (pintype "passive"))
    )
    (net (code "169") (name "Net-(IC9-DIG2)") (class "Default")
      (node (ref "IC9") (pin "6") (pinfunction "DIG2_6") (pintype "output"))
      (node (ref "LED67") (pin "3") (pinfunction "COM_3") (pintype "passive"))
      (node (ref "LED67") (pin "8") (pinfunction "COM_8") (pintype "passive"))
    )
    (net (code "170") (name "Net-(IC9-DIG3)") (class "Default")
      (node (ref "IC9") (pin "7") (pinfunction "DIG3_7") (pintype "output"))
      (node (ref "LED68") (pin "3") (pinfunction "COM_3") (pintype "passive"))
      (node (ref "LED68") (pin "8") (pinfunction "COM_8") (pintype "passive"))
    )
    (net (code "171") (name "Net-(IC9-DIG4)") (class "Default")
      (node (ref "IC9") (pin "3") (pinfunction "DIG4_3") (pintype "output"))
      (node (ref "LED69") (pin "3") (pinfunction "COM_3") (pintype "passive"))
      (node (ref "LED69") (pin "8") (pinfunction "COM_8") (pintype "passive"))
    )
    (net (code "172") (name "Net-(IC9-DIG5)") (class "Default")
      (node (ref "IC9") (pin "10") (pinfunction "DIG5_10") (pintype "output"))
      (node (ref "LED70") (pin "3") (pinfunction "COM_3") (pintype "passive"))
      (node (ref "LED70") (pin "8") (pinfunction "COM_8") (pintype "passive"))
    )
    (net (code "173") (name "Net-(IC9-DIG6)") (class "Default")
      (node (ref "IC9") (pin "5") (pinfunction "DIG6_5") (pintype "output"))
      (node (ref "LED71") (pin "3") (pinfunction "COM_3") (pintype "passive"))
      (node (ref "LED71") (pin "8") (pinfunction "COM_8") (pintype "passive"))
    )
    (net (code "174") (name "Net-(IC9-DIG7)") (class "Default")
      (node (ref "IC9") (pin "8") (pinfunction "DIG7_8") (pintype "output"))
      (node (ref "LED72") (pin "3") (pinfunction "COM_3") (pintype "passive"))
      (node (ref "LED72") (pin "8") (pinfunction "COM_8") (pintype "passive"))
    )
    (net (code "175") (name "Net-(IC9-ISET)") (class "Default")
      (node (ref "IC9") (pin "18") (pinfunction "ISET_18") (pintype "input"))
      (node (ref "R10") (pin "2") (pinfunction "2_2") (pintype "passive"))
    )
    (net (code "176") (name "Net-(IC9-LOAD)") (class "Default")
      (node (ref "IC9") (pin "12") (pinfunction "LOAD_12") (pintype "input"))
      (node (ref "R31") (pin "1") (pinfunction "1_1") (pintype "passive"))
    )
    (net (code "177") (name "Net-(IC9-SEGA)") (class "Default")
      (node (ref "IC9") (pin "14") (pinfunction "SEGA_14") (pintype "output"))
      (node (ref "LED65") (pin "7") (pinfunction "A_7") (pintype "passive"))
      (node (ref "LED66") (pin "7") (pinfunction "A_7") (pintype "passive"))
      (node (ref "LED67") (pin "7") (pinfunction "A_7") (pintype "passive"))
      (node (ref "LED68") (pin "7") (pinfunction "A_7") (pintype "passive"))
      (node (ref "LED69") (pin "7") (pinfunction "A_7") (pintype "passive"))
      (node (ref "LED70") (pin "7") (pinfunction "A_7") (pintype "passive"))
      (node (ref "LED71") (pin "7") (pinfunction "A_7") (pintype "passive"))
      (node (ref "LED72") (pin "7") (pinfunction "A_7") (pintype "passive"))
    )
    (net (code "178") (name "Net-(IC9-SEGB)") (class "Default")
      (node (ref "IC9") (pin "16") (pinfunction "SEGB_16") (pintype "output"))
      (node (ref "LED65") (pin "6") (pinfunction "B_6") (pintype "passive"))
      (node (ref "LED66") (pin "6") (pinfunction "B_6") (pintype "passive"))
      (node (ref "LED67") (pin "6") (pinfunction "B_6") (pintype "passive"))
      (node (ref "LED68") (pin "6") (pinfunction "B_6") (pintype "passive"))
      (node (ref "LED69") (pin "6") (pinfunction "B_6") (pintype "passive"))
      (node (ref "LED70") (pin "6") (pinfunction "B_6") (pintype "passive"))
      (node (ref "LED71") (pin "6") (pinfunction "B_6") (pintype "passive"))
      (node (ref "LED72") (pin "6") (pinfunction "B_6") (pintype "passive"))
    )
    (net (code "179") (name "Net-(IC9-SEGC)") (class "Default")
      (node (ref "IC9") (pin "20") (pinfunction "SEGC_20") (pintype "output"))
      (node (ref "LED65") (pin "4") (pinfunction "C_4") (pintype "passive"))
      (node (ref "LED66") (pin "4") (pinfunction "C_4") (pintype "passive"))
      (node (ref "LED67") (pin "4") (pinfunction "C_4") (pintype "passive"))
      (node (ref "LED68") (pin "4") (pinfunction "C_4") (pintype "passive"))
      (node (ref "LED69") (pin "4") (pinfunction "C_4") (pintype "passive"))
      (node (ref "LED70") (pin "4") (pinfunction "C_4") (pintype "passive"))
      (node (ref "LED71") (pin "4") (pinfunction "C_4") (pintype "passive"))
      (node (ref "LED72") (pin "4") (pinfunction "C_4") (pintype "passive"))
    )
    (net (code "180") (name "Net-(IC9-SEGD)") (class "Default")
      (node (ref "IC9") (pin "23") (pinfunction "SEGD_23") (pintype "output"))
      (node (ref "LED65") (pin "2") (pinfunction "D_2") (pintype "passive"))
      (node (ref "LED66") (pin "2") (pinfunction "D_2") (pintype "passive"))
      (node (ref "LED67") (pin "2") (pinfunction "D_2") (pintype "passive"))
      (node (ref "LED68") (pin "2") (pinfunction "D_2") (pintype "passive"))
      (node (ref "LED69") (pin "2") (pinfunction "D_2") (pintype "passive"))
      (node (ref "LED70") (pin "2") (pinfunction "D_2") (pintype "passive"))
      (node (ref "LED71") (pin "2") (pinfunction "D_2") (pintype "passive"))
      (node (ref "LED72") (pin "2") (pinfunction "D_2") (pintype "passive"))
    )
    (net (code "181") (name "Net-(IC9-SEGDP)") (class "Default")
      (node (ref "IC9") (pin "22") (pinfunction "SEGDP_22") (pintype "output"))
      (node (ref "LED65") (pin "5") (pinfunction "DP_5") (pintype "passive"))
      (node (ref "LED66") (pin "5") (pinfunction "DP_5") (pintype "passive"))
      (node (ref "LED67") (pin "5") (pinfunction "DP_5") (pintype "passive"))
      (node (ref "LED68") (pin "5") (pinfunction "DP_5") (pintype "passive"))
      (node (ref "LED69") (pin "5") (pinfunction "DP_5") (pintype "passive"))
      (node (ref "LED70") (pin "5") (pinfunction "DP_5") (pintype "passive"))
      (node (ref "LED71") (pin "5") (pinfunction "DP_5") (pintype "passive"))
      (node (ref "LED72") (pin "5") (pinfunction "DP_5") (pintype "passive"))
    )
    (net (code "182") (name "Net-(IC9-SEGE)") (class "Default")
      (node (ref "IC9") (pin "21") (pinfunction "SEGE_21") (pintype "output"))
      (node (ref "LED65") (pin "1") (pinfunction "E_1") (pintype "passive"))
      (node (ref "LED66") (pin "1") (pinfunction "E_1") (pintype "passive"))
      (node (ref "LED67") (pin "1") (pinfunction "E_1") (pintype "passive"))
      (node (ref "LED68") (pin "1") (pinfunction "E_1") (pintype "passive"))
      (node (ref "LED69") (pin "1") (pinfunction "E_1") (pintype "passive"))
      (node (ref "LED70") (pin "1") (pinfunction "E_1") (pintype "passive"))
      (node (ref "LED71") (pin "1") (pinfunction "E_1") (pintype "passive"))
      (node (ref "LED72") (pin "1") (pinfunction "E_1") (pintype "passive"))
    )
    (net (code "183") (name "Net-(IC9-SEGF)") (class "Default")
      (node (ref "IC9") (pin "15") (pinfunction "SEGF_15") (pintype "output"))
      (node (ref "LED65") (pin "9") (pinfunction "F_9") (pintype "passive"))
      (node (ref "LED66") (pin "9") (pinfunction "F_9") (pintype "passive"))
      (node (ref "LED67") (pin "9") (pinfunction "F_9") (pintype "passive"))
      (node (ref "LED68") (pin "9") (pinfunction "F_9") (pintype "passive"))
      (node (ref "LED69") (pin "9") (pinfunction "F_9") (pintype "passive"))
      (node (ref "LED70") (pin "9") (pinfunction "F_9") (pintype "passive"))
      (node (ref "LED71") (pin "9") (pinfunction "F_9") (pintype "passive"))
      (node (ref "LED72") (pin "9") (pinfunction "F_9") (pintype "passive"))
    )
    (net (code "184") (name "Net-(IC9-SEGG)") (class "Default")
      (node (ref "IC9") (pin "17") (pinfunction "SEGG_17") (pintype "output"))
      (node (ref "LED65") (pin "10") (pinfunction "G_10") (pintype "passive"))
      (node (ref "LED66") (pin "10") (pinfunction "G_10") (pintype "passive"))
      (node (ref "LED67") (pin "10") (pinfunction "G_10") (pintype "passive"))
      (node (ref "LED68") (pin "10") (pinfunction "G_10") (pintype "passive"))
      (node (ref "LED69") (pin "10") (pinfunction "G_10") (pintype "passive"))
      (node (ref "LED70") (pin "10") (pinfunction "G_10") (pintype "passive"))
      (node (ref "LED71") (pin "10") (pinfunction "G_10") (pintype "passive"))
      (node (ref "LED72") (pin "10") (pinfunction "G_10") (pintype "passive"))
    )
    (net (code "185") (name "Net-(IC10-CLK)") (class "Default")
      (node (ref "IC10") (pin "13") (pinfunction "CLK_13") (pintype "input"))
      (node (ref "R32") (pin "1") (pinfunction "1_1") (pintype "passive"))
    )
    (net (code "186") (name "Net-(IC10-DIG0)") (class "Default")
      (node (ref "IC10") (pin "2") (pinfunction "DIG0_2") (pintype "output"))
      (node (ref "LED73") (pin "3") (pinfunction "COM_3") (pintype "passive"))
      (node (ref "LED73") (pin "8") (pinfunction "COM_8") (pintype "passive"))
    )
    (net (code "187") (name "Net-(IC10-DIG1)") (class "Default")
      (node (ref "IC10") (pin "11") (pinfunction "DIG1_11") (pintype "output"))
      (node (ref "LED74") (pin "3") (pinfunction "COM_3") (pintype "passive"))
      (node (ref "LED74") (pin "8") (pinfunction "COM_8") (pintype "passive"))
    )
    (net (code "188") (name "Net-(IC10-DIG2)") (class "Default")
      (node (ref "IC10") (pin "6") (pinfunction "DIG2_6") (pintype "output"))
      (node (ref "LED75") (pin "3") (pinfunction "COM_3") (pintype "passive"))
      (node (ref "LED75") (pin "8") (pinfunction "COM_8") (pintype "passive"))
    )
    (net (code "189") (name "Net-(IC10-DIG3)") (class "Default")
      (node (ref "IC10") (pin "7") (pinfunction "DIG3_7") (pintype "output"))
      (node (ref "LED76") (pin "3") (pinfunction "COM_3") (pintype "passive"))
      (node (ref "LED76") (pin "8") (pinfunction "COM_8") (pintype "passive"))
    )
    (net (code "190") (name "Net-(IC10-DIG4)") (class "Default")
      (node (ref "IC10") (pin "3") (pinfunction "DIG4_3") (pintype "output"))
      (node (ref "LED77") (pin "3") (pinfunction "COM_3") (pintype "passive"))
      (node (ref "LED77") (pin "8") (pinfunction "COM_8") (pintype "passive"))
    )
    (net (code "191") (name "Net-(IC10-DIG5)") (class "Default")
      (node (ref "IC10") (pin "10") (pinfunction "DIG5_10") (pintype "output"))
      (node (ref "LED78") (pin "3") (pinfunction "COM_3") (pintype "passive"))
      (node (ref "LED78") (pin "8") (pinfunction "COM_8") (pintype "passive"))
    )
    (net (code "192") (name "Net-(IC10-DIG6)") (class "Default")
      (node (ref "IC10") (pin "5") (pinfunction "DIG6_5") (pintype "output"))
      (node (ref "LED79") (pin "3") (pinfunction "COM_3") (pintype "passive"))
      (node (ref "LED79") (pin "8") (pinfunction "COM_8") (pintype "passive"))
    )
    (net (code "193") (name "Net-(IC10-DIG7)") (class "Default")
      (node (ref "IC10") (pin "8") (pinfunction "DIG7_8") (pintype "output"))
      (node (ref "LED80") (pin "3") (pinfunction "COM_3") (pintype "passive"))
      (node (ref "LED80") (pin "8") (pinfunction "COM_8") (pintype "passive"))
    )
    (net (code "194") (name "Net-(IC10-DIN)") (class "Default")
      (node (ref "IC10") (pin "1") (pinfunction "DIN_1") (pintype "input"))
      (node (ref "IC9") (pin "24") (pinfunction "DOUT_24") (pintype "output"))
    )
    (net (code "195") (name "Net-(IC10-DOUT)") (class "Default")
      (node (ref "IC10") (pin "24") (pinfunction "DOUT_24") (pintype "output"))
      (node (ref "IC11") (pin "1") (pinfunction "DIN_1") (pintype "input"))
    )
    (net (code "196") (name "Net-(IC10-ISET)") (class "Default")
      (node (ref "IC10") (pin "18") (pinfunction "ISET_18") (pintype "input"))
      (node (ref "R11") (pin "2") (pinfunction "2_2") (pintype "passive"))
    )
    (net (code "197") (name "Net-(IC10-LOAD)") (class "Default")
      (node (ref "IC10") (pin "12") (pinfunction "LOAD_12") (pintype "input"))
      (node (ref "R33") (pin "1") (pinfunction "1_1") (pintype "passive"))
    )
    (net (code "198") (name "Net-(IC10-SEGA)") (class "Default")
      (node (ref "IC10") (pin "14") (pinfunction "SEGA_14") (pintype "output"))
      (node (ref "LED73") (pin "7") (pinfunction "A_7") (pintype "passive"))
      (node (ref "LED74") (pin "7") (pinfunction "A_7") (pintype "passive"))
      (node (ref "LED75") (pin "7") (pinfunction "A_7") (pintype "passive"))
      (node (ref "LED76") (pin "7") (pinfunction "A_7") (pintype "passive"))
      (node (ref "LED77") (pin "7") (pinfunction "A_7") (pintype "passive"))
      (node (ref "LED78") (pin "7") (pinfunction "A_7") (pintype "passive"))
      (node (ref "LED79") (pin "7") (pinfunction "A_7") (pintype "passive"))
      (node (ref "LED80") (pin "7") (pinfunction "A_7") (pintype "passive"))
    )
    (net (code "199") (name "Net-(IC10-SEGB)") (class "Default")
      (node (ref "IC10") (pin "16") (pinfunction "SEGB_16") (pintype "output"))
      (node (ref "LED73") (pin "6") (pinfunction "B_6") (pintype "passive"))
      (node (ref "LED74") (pin "6") (pinfunction "B_6") (pintype "passive"))
      (node (ref "LED75") (pin "6") (pinfunction "B_6") (pintype "passive"))
      (node (ref "LED76") (pin "6") (pinfunction "B_6") (pintype "passive"))
      (node (ref "LED77") (pin "6") (pinfunction "B_6") (pintype "passive"))
      (node (ref "LED78") (pin "6") (pinfunction "B_6") (pintype "passive"))
      (node (ref "LED79") (pin "6") (pinfunction "B_6") (pintype "passive"))
      (node (ref "LED80") (pin "6") (pinfunction "B_6") (pintype "passive"))
    )
    (net (code "200") (name "Net-(IC10-SEGC)") (class "Default")
      (node (ref "IC10") (pin "20") (pinfunction "SEGC_20") (pintype "output"))
      (node (ref "LED73") (pin "4") (pinfunction "C_4") (pintype "passive"))
      (node (ref "LED74") (pin "4") (pinfunction "C_4") (pintype "passive"))
      (node (ref "LED75") (pin "4") (pinfunction "C_4") (pintype "passive"))
      (node (ref "LED76") (pin "4") (pinfunction "C_4") (pintype "passive"))
      (node (ref "LED77") (pin "4") (pinfunction "C_4") (pintype "passive"))
      (node (ref "LED78") (pin "4") (pinfunction "C_4") (pintype "passive"))
      (node (ref "LED79") (pin "4") (pinfunction "C_4") (pintype "passive"))
      (node (ref "LED80") (pin "4") (pinfunction "C_4") (pintype "passive"))
    )
    (net (code "201") (name "Net-(IC10-SEGD)") (class "Default")
      (node (ref "IC10") (pin "23") (pinfunction "SEGD_23") (pintype "output"))
      (node (ref "LED73") (pin "2") (pinfunction "D_2") (pintype "passive"))
      (node (ref "LED74") (pin "2") (pinfunction "D_2") (pintype "passive"))
      (node (ref "LED75") (pin "2") (pinfunction "D_2") (pintype "passive"))
      (node (ref "LED76") (pin "2") (pinfunction "D_2") (pintype "passive"))
      (node (ref "LED77") (pin "2") (pinfunction "D_2") (pintype "passive"))
      (node (ref "LED78") (pin "2") (pinfunction "D_2") (pintype "passive"))
      (node (ref "LED79") (pin "2") (pinfunction "D_2") (pintype "passive"))
      (node (ref "LED80") (pin "2") (pinfunction "D_2") (pintype "passive"))
    )
    (net (code "202") (name "Net-(IC10-SEGDP)") (class "Default")
      (node (ref "IC10") (pin "22") (pinfunction "SEGDP_22") (pintype "output"))
      (node (ref "LED73") (pin "5") (pinfunction "DP_5") (pintype "passive"))
      (node (ref "LED74") (pin "5") (pinfunction "DP_5") (pintype "passive"))
      (node (ref "LED75") (pin "5") (pinfunction "DP_5") (pintype "passive"))
      (node (ref "LED76") (pin "5") (pinfunction "DP_5") (pintype "passive"))
      (node (ref "LED77") (pin "5") (pinfunction "DP_5") (pintype "passive"))
      (node (ref "LED78") (pin "5") (pinfunction "DP_5") (pintype "passive"))
      (node (ref "LED79") (pin "5") (pinfunction "DP_5") (pintype "passive"))
      (node (ref "LED80") (pin "5") (pinfunction "DP_5") (pintype "passive"))
    )
    (net (code "203") (name "Net-(IC10-SEGE)") (class "Default")
      (node (ref "IC10") (pin "21") (pinfunction "SEGE_21") (pintype "output"))
      (node (ref "LED73") (pin "1") (pinfunction "E_1") (pintype "passive"))
      (node (ref "LED74") (pin "1") (pinfunction "E_1") (pintype "passive"))
      (node (ref "LED75") (pin "1") (pinfunction "E_1") (pintype "passive"))
      (node (ref "LED76") (pin "1") (pinfunction "E_1") (pintype "passive"))
      (node (ref "LED77") (pin "1") (pinfunction "E_1") (pintype "passive"))
      (node (ref "LED78") (pin "1") (pinfunction "E_1") (pintype "passive"))
      (node (ref "LED79") (pin "1") (pinfunction "E_1") (pintype "passive"))
      (node (ref "LED80") (pin "1") (pinfunction "E_1") (pintype "passive"))
    )
    (net (code "204") (name "Net-(IC10-SEGF)") (class "Default")
      (node (ref "IC10") (pin "15") (pinfunction "SEGF_15") (pintype "output"))
      (node (ref "LED73") (pin "9") (pinfunction "F_9") (pintype "passive"))
      (node (ref "LED74") (pin "9") (pinfunction "F_9") (pintype "passive"))
      (node (ref "LED75") (pin "9") (pinfunction "F_9") (pintype "passive"))
      (node (ref "LED76") (pin "9") (pinfunction "F_9") (pintype "passive"))
      (node (ref "LED77") (pin "9") (pinfunction "F_9") (pintype "passive"))
      (node (ref "LED78") (pin "9") (pinfunction "F_9") (pintype "passive"))
      (node (ref "LED79") (pin "9") (pinfunction "F_9") (pintype "passive"))
      (node (ref "LED80") (pin "9") (pinfunction "F_9") (pintype "passive"))
    )
    (net (code "205") (name "Net-(IC10-SEGG)") (class "Default")
      (node (ref "IC10") (pin "17") (pinfunction "SEGG_17") (pintype "output"))
      (node (ref "LED73") (pin "10") (pinfunction "G_10") (pintype "passive"))
      (node (ref "LED74") (pin "10") (pinfunction "G_10") (pintype "passive"))
      (node (ref "LED75") (pin "10") (pinfunction "G_10") (pintype "passive"))
      (node (ref "LED76") (pin "10") (pinfunction "G_10") (pintype "passive"))
      (node (ref "LED77") (pin "10") (pinfunction "G_10") (pintype "passive"))
      (node (ref "LED78") (pin "10") (pinfunction "G_10") (pintype "passive"))
      (node (ref "LED79") (pin "10") (pinfunction "G_10") (pintype "passive"))
      (node (ref "LED80") (pin "10") (pinfunction "G_10") (pintype "passive"))
    )
    (net (code "206") (name "Net-(IC11-CLK)") (class "Default")
      (node (ref "IC11") (pin "13") (pinfunction "CLK_13") (pintype "input"))
      (node (ref "R34") (pin "1") (pinfunction "1_1") (pintype "passive"))
    )
    (net (code "207") (name "Net-(IC11-DIG0)") (class "Default")
      (node (ref "IC11") (pin "2") (pinfunction "DIG0_2") (pintype "output"))
      (node (ref "LED81") (pin "3") (pinfunction "COM_3") (pintype "passive"))
      (node (ref "LED81") (pin "8") (pinfunction "COM_8") (pintype "passive"))
    )
    (net (code "208") (name "Net-(IC11-DIG1)") (class "Default")
      (node (ref "IC11") (pin "11") (pinfunction "DIG1_11") (pintype "output"))
      (node (ref "LED82") (pin "3") (pinfunction "COM_3") (pintype "passive"))
      (node (ref "LED82") (pin "8") (pinfunction "COM_8") (pintype "passive"))
    )
    (net (code "209") (name "Net-(IC11-DIG2)") (class "Default")
      (node (ref "IC11") (pin "6") (pinfunction "DIG2_6") (pintype "output"))
      (node (ref "LED83") (pin "3") (pinfunction "COM_3") (pintype "passive"))
      (node (ref "LED83") (pin "8") (pinfunction "COM_8") (pintype "passive"))
    )
    (net (code "210") (name "Net-(IC11-DIG3)") (class "Default")
      (node (ref "IC11") (pin "7") (pinfunction "DIG3_7") (pintype "output"))
      (node (ref "LED84") (pin "3") (pinfunction "COM_3") (pintype "passive"))
      (node (ref "LED84") (pin "8") (pinfunction "COM_8") (pintype "passive"))
    )
    (net (code "211") (name "Net-(IC11-DIG4)") (class "Default")
      (node (ref "IC11") (pin "3") (pinfunction "DIG4_3") (pintype "output"))
      (node (ref "LED85") (pin "3") (pinfunction "COM_3") (pintype "passive"))
      (node (ref "LED85") (pin "8") (pinfunction "COM_8") (pintype "passive"))
    )
    (net (code "212") (name "Net-(IC11-DIG5)") (class "Default")
      (node (ref "IC11") (pin "10") (pinfunction "DIG5_10") (pintype "output"))
      (node (ref "LED86") (pin "3") (pinfunction "COM_3") (pintype "passive"))
      (node (ref "LED86") (pin "8") (pinfunction "COM_8") (pintype "passive"))
    )
    (net (code "213") (name "Net-(IC11-DIG6)") (class "Default")
      (node (ref "IC11") (pin "5") (pinfunction "DIG6_5") (pintype "output"))
      (node (ref "LED87") (pin "3") (pinfunction "COM_3") (pintype "passive"))
      (node (ref "LED87") (pin "8") (pinfunction "COM_8") (pintype "passive"))
    )
    (net (code "214") (name "Net-(IC11-DIG7)") (class "Default")
      (node (ref "IC11") (pin "8") (pinfunction "DIG7_8") (pintype "output"))
      (node (ref "LED88") (pin "3") (pinfunction "COM_3") (pintype "passive"))
      (node (ref "LED88") (pin "8") (pinfunction "COM_8") (pintype "passive"))
    )
    (net (code "215") (name "Net-(IC11-DOUT)") (class "Default")
      (node (ref "IC11") (pin "24") (pinfunction "DOUT_24") (pintype "output"))
      (node (ref "IC12") (pin "1") (pinfunction "DIN_1") (pintype "input"))
    )
    (net (code "216") (name "Net-(IC11-ISET)") (class "Default")
      (node (ref "IC11") (pin "18") (pinfunction "ISET_18") (pintype "input"))
      (node (ref "R12") (pin "2") (pinfunction "2_2") (pintype "passive"))
    )
    (net (code "217") (name "Net-(IC11-LOAD)") (class "Default")
      (node (ref "IC11") (pin "12") (pinfunction "LOAD_12") (pintype "input"))
      (node (ref "R35") (pin "1") (pinfunction "1_1") (pintype "passive"))
    )
    (net (code "218") (name "Net-(IC11-SEGA)") (class "Default")
      (node (ref "IC11") (pin "14") (pinfunction "SEGA_14") (pintype "output"))
      (node (ref "LED81") (pin "7") (pinfunction "A_7") (pintype "passive"))
      (node (ref "LED82") (pin "7") (pinfunction "A_7") (pintype "passive"))
      (node (ref "LED83") (pin "7") (pinfunction "A_7") (pintype "passive"))
      (node (ref "LED84") (pin "7") (pinfunction "A_7") (pintype "passive"))
      (node (ref "LED85") (pin "7") (pinfunction "A_7") (pintype "passive"))
      (node (ref "LED86") (pin "7") (pinfunction "A_7") (pintype "passive"))
      (node (ref "LED87") (pin "7") (pinfunction "A_7") (pintype "passive"))
      (node (ref "LED88") (pin "7") (pinfunction "A_7") (pintype "passive"))
    )
    (net (code "219") (name "Net-(IC11-SEGB)") (class "Default")
      (node (ref "IC11") (pin "16") (pinfunction "SEGB_16") (pintype "output"))
      (node (ref "LED81") (pin "6") (pinfunction "B_6") (pintype "passive"))
      (node (ref "LED82") (pin "6") (pinfunction "B_6") (pintype "passive"))
      (node (ref "LED83") (pin "6") (pinfunction "B_6") (pintype "passive"))
      (node (ref "LED84") (pin "6") (pinfunction "B_6") (pintype "passive"))
      (node (ref "LED85") (pin "6") (pinfunction "B_6") (pintype "passive"))
      (node (ref "LED86") (pin "6") (pinfunction "B_6") (pintype "passive"))
      (node (ref "LED87") (pin "6") (pinfunction "B_6") (pintype "passive"))
      (node (ref "LED88") (pin "6") (pinfunction "B_6") (pintype "passive"))
    )
    (net (code "220") (name "Net-(IC11-SEGC)") (class "Default")
      (node (ref "IC11") (pin "20") (pinfunction "SEGC_20") (pintype "output"))
      (node (ref "LED81") (pin "4") (pinfunction "C_4") (pintype "passive"))
      (node (ref "LED82") (pin "4") (pinfunction "C_4") (pintype "passive"))
      (node (ref "LED83") (pin "4") (pinfunction "C_4") (pintype "passive"))
      (node (ref "LED84") (pin "4") (pinfunction "C_4") (pintype "passive"))
      (node (ref "LED85") (pin "4") (pinfunction "C_4") (pintype "passive"))
      (node (ref "LED86") (pin "4") (pinfunction "C_4") (pintype "passive"))
      (node (ref "LED87") (pin "4") (pinfunction "C_4") (pintype "passive"))
      (node (ref "LED88") (pin "4") (pinfunction "C_4") (pintype "passive"))
    )
    (net (code "221") (name "Net-(IC11-SEGD)") (class "Default")
      (node (ref "IC11") (pin "23") (pinfunction "SEGD_23") (pintype "output"))
      (node (ref "LED81") (pin "2") (pinfunction "D_2") (pintype "passive"))
      (node (ref "LED82") (pin "2") (pinfunction "D_2") (pintype "passive"))
      (node (ref "LED83") (pin "2") (pinfunction "D_2") (pintype "passive"))
      (node (ref "LED84") (pin "2") (pinfunction "D_2") (pintype "passive"))
      (node (ref "LED85") (pin "2") (pinfunction "D_2") (pintype "passive"))
      (node (ref "LED86") (pin "2") (pinfunction "D_2") (pintype "passive"))
      (node (ref "LED87") (pin "2") (pinfunction "D_2") (pintype "passive"))
      (node (ref "LED88") (pin "2") (pinfunction "D_2") (pintype "passive"))
    )
    (net (code "222") (name "Net-(IC11-SEGDP)") (class "Default")
      (node (ref "IC11") (pin "22") (pinfunction "SEGDP_22") (pintype "output"))
      (node (ref "LED81") (pin "5") (pinfunction "DP_5") (pintype "passive"))
      (node (ref "LED82") (pin "5") (pinfunction "DP_5") (pintype "passive"))
      (node (ref "LED83") (pin "5") (pinfunction "DP_5") (pintype "passive"))
      (node (ref "LED84") (pin "5") (pinfunction "DP_5") (pintype "passive"))
      (node (ref "LED85") (pin "5") (pinfunction "DP_5") (pintype "passive"))
      (node (ref "LED86") (pin "5") (pinfunction "DP_5") (pintype "passive"))
      (node (ref "LED87") (pin "5") (pinfunction "DP_5") (pintype "passive"))
      (node (ref "LED88") (pin "5") (pinfunction "DP_5") (pintype "passive"))
    )
    (net (code "223") (name "Net-(IC11-SEGE)") (class "Default")
      (node (ref "IC11") (pin "21") (pinfunction "SEGE_21") (pintype "output"))
      (node (ref "LED81") (pin "1") (pinfunction "E_1") (pintype "passive"))
      (node (ref "LED82") (pin "1") (pinfunction "E_1") (pintype "passive"))
      (node (ref "LED83") (pin "1") (pinfunction "E_1") (pintype "passive"))
      (node (ref "LED84") (pin "1") (pinfunction "E_1") (pintype "passive"))
      (node (ref "LED85") (pin "1") (pinfunction "E_1") (pintype "passive"))
      (node (ref "LED86") (pin "1") (pinfunction "E_1") (pintype "passive"))
      (node (ref "LED87") (pin "1") (pinfunction "E_1") (pintype "passive"))
      (node (ref "LED88") (pin "1") (pinfunction "E_1") (pintype "passive"))
    )
    (net (code "224") (name "Net-(IC11-SEGF)") (class "Default")
      (node (ref "IC11") (pin "15") (pinfunction "SEGF_15") (pintype "output"))
      (node (ref "LED81") (pin "9") (pinfunction "F_9") (pintype "passive"))
      (node (ref "LED82") (pin "9") (pinfunction "F_9") (pintype "passive"))
      (node (ref "LED83") (pin "9") (pinfunction "F_9") (pintype "passive"))
      (node (ref "LED84") (pin "9") (pinfunction "F_9") (pintype "passive"))
      (node (ref "LED85") (pin "9") (pinfunction "F_9") (pintype "passive"))
      (node (ref "LED86") (pin "9") (pinfunction "F_9") (pintype "passive"))
      (node (ref "LED87") (pin "9") (pinfunction "F_9") (pintype "passive"))
      (node (ref "LED88") (pin "9") (pinfunction "F_9") (pintype "passive"))
    )
    (net (code "225") (name "Net-(IC11-SEGG)") (class "Default")
      (node (ref "IC11") (pin "17") (pinfunction "SEGG_17") (pintype "output"))
      (node (ref "LED81") (pin "10") (pinfunction "G_10") (pintype "passive"))
      (node (ref "LED82") (pin "10") (pinfunction "G_10") (pintype "passive"))
      (node (ref "LED83") (pin "10") (pinfunction "G_10") (pintype "passive"))
      (node (ref "LED84") (pin "10") (pinfunction "G_10") (pintype "passive"))
      (node (ref "LED85") (pin "10") (pinfunction "G_10") (pintype "passive"))
      (node (ref "LED86") (pin "10") (pinfunction "G_10") (pintype "passive"))
      (node (ref "LED87") (pin "10") (pinfunction "G_10") (pintype "passive"))
      (node (ref "LED88") (pin "10") (pinfunction "G_10") (pintype "passive"))
    )
    (net (code "226") (name "Net-(IC12-CLK)") (class "Default")
      (node (ref "IC12") (pin "13") (pinfunction "CLK_13") (pintype "input"))
      (node (ref "R36") (pin "1") (pinfunction "1_1") (pintype "passive"))
    )
    (net (code "227") (name "Net-(IC12-DIG0)") (class "Default")
      (node (ref "IC12") (pin "2") (pinfunction "DIG0_2") (pintype "output"))
      (node (ref "LED89") (pin "3") (pinfunction "COM_3") (pintype "passive"))
      (node (ref "LED89") (pin "8") (pinfunction "COM_8") (pintype "passive"))
    )
    (net (code "228") (name "Net-(IC12-DIG1)") (class "Default")
      (node (ref "IC12") (pin "11") (pinfunction "DIG1_11") (pintype "output"))
      (node (ref "LED90") (pin "3") (pinfunction "COM_3") (pintype "passive"))
      (node (ref "LED90") (pin "8") (pinfunction "COM_8") (pintype "passive"))
    )
    (net (code "229") (name "Net-(IC12-DIG2)") (class "Default")
      (node (ref "IC12") (pin "6") (pinfunction "DIG2_6") (pintype "output"))
      (node (ref "LED91") (pin "3") (pinfunction "COM_3") (pintype "passive"))
      (node (ref "LED91") (pin "8") (pinfunction "COM_8") (pintype "passive"))
    )
    (net (code "230") (name "Net-(IC12-DIG3)") (class "Default")
      (node (ref "IC12") (pin "7") (pinfunction "DIG3_7") (pintype "output"))
      (node (ref "LED92") (pin "3") (pinfunction "COM_3") (pintype "passive"))
      (node (ref "LED92") (pin "8") (pinfunction "COM_8") (pintype "passive"))
    )
    (net (code "231") (name "Net-(IC12-DIG4)") (class "Default")
      (node (ref "IC12") (pin "3") (pinfunction "DIG4_3") (pintype "output"))
      (node (ref "LED93") (pin "3") (pinfunction "COM_3") (pintype "passive"))
      (node (ref "LED93") (pin "8") (pinfunction "COM_8") (pintype "passive"))
    )
    (net (code "232") (name "Net-(IC12-DIG5)") (class "Default")
      (node (ref "IC12") (pin "10") (pinfunction "DIG5_10") (pintype "output"))
      (node (ref "LED94") (pin "3") (pinfunction "COM_3") (pintype "passive"))
      (node (ref "LED94") (pin "8") (pinfunction "COM_8") (pintype "passive"))
    )
    (net (code "233") (name "Net-(IC12-DIG6)") (class "Default")
      (node (ref "IC12") (pin "5") (pinfunction "DIG6_5") (pintype "output"))
      (node (ref "LED95") (pin "3") (pinfunction "COM_3") (pintype "passive"))
      (node (ref "LED95") (pin "8") (pinfunction "COM_8") (pintype "passive"))
    )
    (net (code "234") (name "Net-(IC12-DIG7)") (class "Default")
      (node (ref "IC12") (pin "8") (pinfunction "DIG7_8") (pintype "output"))
      (node (ref "LED96") (pin "3") (pinfunction "COM_3") (pintype "passive"))
      (node (ref "LED96") (pin "8") (pinfunction "COM_8") (pintype "passive"))
    )
    (net (code "235") (name "Net-(IC12-DOUT)") (class "Default")
      (node (ref "IC12") (pin "24") (pinfunction "DOUT_24") (pintype "output"))
      (node (ref "SV2") (pin "4") (pinfunction "4_4") (pintype "passive"))
    )
    (net (code "236") (name "Net-(IC12-ISET)") (class "Default")
      (node (ref "IC12") (pin "18") (pinfunction "ISET_18") (pintype "input"))
      (node (ref "R13") (pin "2") (pinfunction "2_2") (pintype "passive"))
    )
    (net (code "237") (name "Net-(IC12-LOAD)") (class "Default")
      (node (ref "IC12") (pin "12") (pinfunction "LOAD_12") (pintype "input"))
      (node (ref "R37") (pin "1") (pinfunction "1_1") (pintype "passive"))
    )
    (net (code "238") (name "Net-(IC12-SEGA)") (class "Default")
      (node (ref "IC12") (pin "14") (pinfunction "SEGA_14") (pintype "output"))
      (node (ref "LED89") (pin "7") (pinfunction "A_7") (pintype "passive"))
      (node (ref "LED90") (pin "7") (pinfunction "A_7") (pintype "passive"))
      (node (ref "LED91") (pin "7") (pinfunction "A_7") (pintype "passive"))
      (node (ref "LED92") (pin "7") (pinfunction "A_7") (pintype "passive"))
      (node (ref "LED93") (pin "7") (pinfunction "A_7") (pintype "passive"))
      (node (ref "LED94") (pin "7") (pinfunction "A_7") (pintype "passive"))
      (node (ref "LED95") (pin "7") (pinfunction "A_7") (pintype "passive"))
      (node (ref "LED96") (pin "7") (pinfunction "A_7") (pintype "passive"))
    )
    (net (code "239") (name "Net-(IC12-SEGB)") (class "Default")
      (node (ref "IC12") (pin "16") (pinfunction "SEGB_16") (pintype "output"))
      (node (ref "LED89") (pin "6") (pinfunction "B_6") (pintype "passive"))
      (node (ref "LED90") (pin "6") (pinfunction "B_6") (pintype "passive"))
      (node (ref "LED91") (pin "6") (pinfunction "B_6") (pintype "passive"))
      (node (ref "LED92") (pin "6") (pinfunction "B_6") (pintype "passive"))
      (node (ref "LED93") (pin "6") (pinfunction "B_6") (pintype "passive"))
      (node (ref "LED94") (pin "6") (pinfunction "B_6") (pintype "passive"))
      (node (ref "LED95") (pin "6") (pinfunction "B_6") (pintype "passive"))
      (node (ref "LED96") (pin "6") (pinfunction "B_6") (pintype "passive"))
    )
    (net (code "240") (name "Net-(IC12-SEGC)") (class "Default")
      (node (ref "IC12") (pin "20") (pinfunction "SEGC_20") (pintype "output"))
      (node (ref "LED89") (pin "4") (pinfunction "C_4") (pintype "passive"))
      (node (ref "LED90") (pin "4") (pinfunction "C_4") (pintype "passive"))
      (node (ref "LED91") (pin "4") (pinfunction "C_4") (pintype "passive"))
      (node (ref "LED92") (pin "4") (pinfunction "C_4") (pintype "passive"))
      (node (ref "LED93") (pin "4") (pinfunction "C_4") (pintype "passive"))
      (node (ref "LED94") (pin "4") (pinfunction "C_4") (pintype "passive"))
      (node (ref "LED95") (pin "4") (pinfunction "C_4") (pintype "passive"))
      (node (ref "LED96") (pin "4") (pinfunction "C_4") (pintype "passive"))
    )
    (net (code "241") (name "Net-(IC12-SEGD)") (class "Default")
      (node (ref "IC12") (pin "23") (pinfunction "SEGD_23") (pintype "output"))
      (node (ref "LED89") (pin "2") (pinfunction "D_2") (pintype "passive"))
      (node (ref "LED90") (pin "2") (pinfunction "D_2") (pintype "passive"))
      (node (ref "LED91") (pin "2") (pinfunction "D_2") (pintype "passive"))
      (node (ref "LED92") (pin "2") (pinfunction "D_2") (pintype "passive"))
      (node (ref "LED93") (pin "2") (pinfunction "D_2") (pintype "passive"))
      (node (ref "LED94") (pin "2") (pinfunction "D_2") (pintype "passive"))
      (node (ref "LED95") (pin "2") (pinfunction "D_2") (pintype "passive"))
      (node (ref "LED96") (pin "2") (pinfunction "D_2") (pintype "passive"))
    )
    (net (code "242") (name "Net-(IC12-SEGDP)") (class "Default")
      (node (ref "IC12") (pin "22") (pinfunction "SEGDP_22") (pintype "output"))
      (node (ref "LED89") (pin "5") (pinfunction "DP_5") (pintype "passive"))
      (node (ref "LED90") (pin "5") (pinfunction "DP_5") (pintype "passive"))
      (node (ref "LED91") (pin "5") (pinfunction "DP_5") (pintype "passive"))
      (node (ref "LED92") (pin "5") (pinfunction "DP_5") (pintype "passive"))
      (node (ref "LED93") (pin "5") (pinfunction "DP_5") (pintype "passive"))
      (node (ref "LED94") (pin "5") (pinfunction "DP_5") (pintype "passive"))
      (node (ref "LED95") (pin "5") (pinfunction "DP_5") (pintype "passive"))
      (node (ref "LED96") (pin "5") (pinfunction "DP_5") (pintype "passive"))
    )
    (net (code "243") (name "Net-(IC12-SEGE)") (class "Default")
      (node (ref "IC12") (pin "21") (pinfunction "SEGE_21") (pintype "output"))
      (node (ref "LED89") (pin "1") (pinfunction "E_1") (pintype "passive"))
      (node (ref "LED90") (pin "1") (pinfunction "E_1") (pintype "passive"))
      (node (ref "LED91") (pin "1") (pinfunction "E_1") (pintype "passive"))
      (node (ref "LED92") (pin "1") (pinfunction "E_1") (pintype "passive"))
      (node (ref "LED93") (pin "1") (pinfunction "E_1") (pintype "passive"))
      (node (ref "LED94") (pin "1") (pinfunction "E_1") (pintype "passive"))
      (node (ref "LED95") (pin "1") (pinfunction "E_1") (pintype "passive"))
      (node (ref "LED96") (pin "1") (pinfunction "E_1") (pintype "passive"))
    )
    (net (code "244") (name "Net-(IC12-SEGF)") (class "Default")
      (node (ref "IC12") (pin "15") (pinfunction "SEGF_15") (pintype "output"))
      (node (ref "LED89") (pin "9") (pinfunction "F_9") (pintype "passive"))
      (node (ref "LED90") (pin "9") (pinfunction "F_9") (pintype "passive"))
      (node (ref "LED91") (pin "9") (pinfunction "F_9") (pintype "passive"))
      (node (ref "LED92") (pin "9") (pinfunction "F_9") (pintype "passive"))
      (node (ref "LED93") (pin "9") (pinfunction "F_9") (pintype "passive"))
      (node (ref "LED94") (pin "9") (pinfunction "F_9") (pintype "passive"))
      (node (ref "LED95") (pin "9") (pinfunction "F_9") (pintype "passive"))
      (node (ref "LED96") (pin "9") (pinfunction "F_9") (pintype "passive"))
    )
    (net (code "245") (name "Net-(IC12-SEGG)") (class "Default")
      (node (ref "IC12") (pin "17") (pinfunction "SEGG_17") (pintype "output"))
      (node (ref "LED89") (pin "10") (pinfunction "G_10") (pintype "passive"))
      (node (ref "LED90") (pin "10") (pinfunction "G_10") (pintype "passive"))
      (node (ref "LED91") (pin "10") (pinfunction "G_10") (pintype "passive"))
      (node (ref "LED92") (pin "10") (pinfunction "G_10") (pintype "passive"))
      (node (ref "LED93") (pin "10") (pinfunction "G_10") (pintype "passive"))
      (node (ref "LED94") (pin "10") (pinfunction "G_10") (pintype "passive"))
      (node (ref "LED95") (pin "10") (pinfunction "G_10") (pintype "passive"))
      (node (ref "LED96") (pin "10") (pinfunction "G_10") (pintype "passive"))
    )
  )
)
